# QuDAC_V4.net
KiCad netlist of a schematic drawn in EAGLE
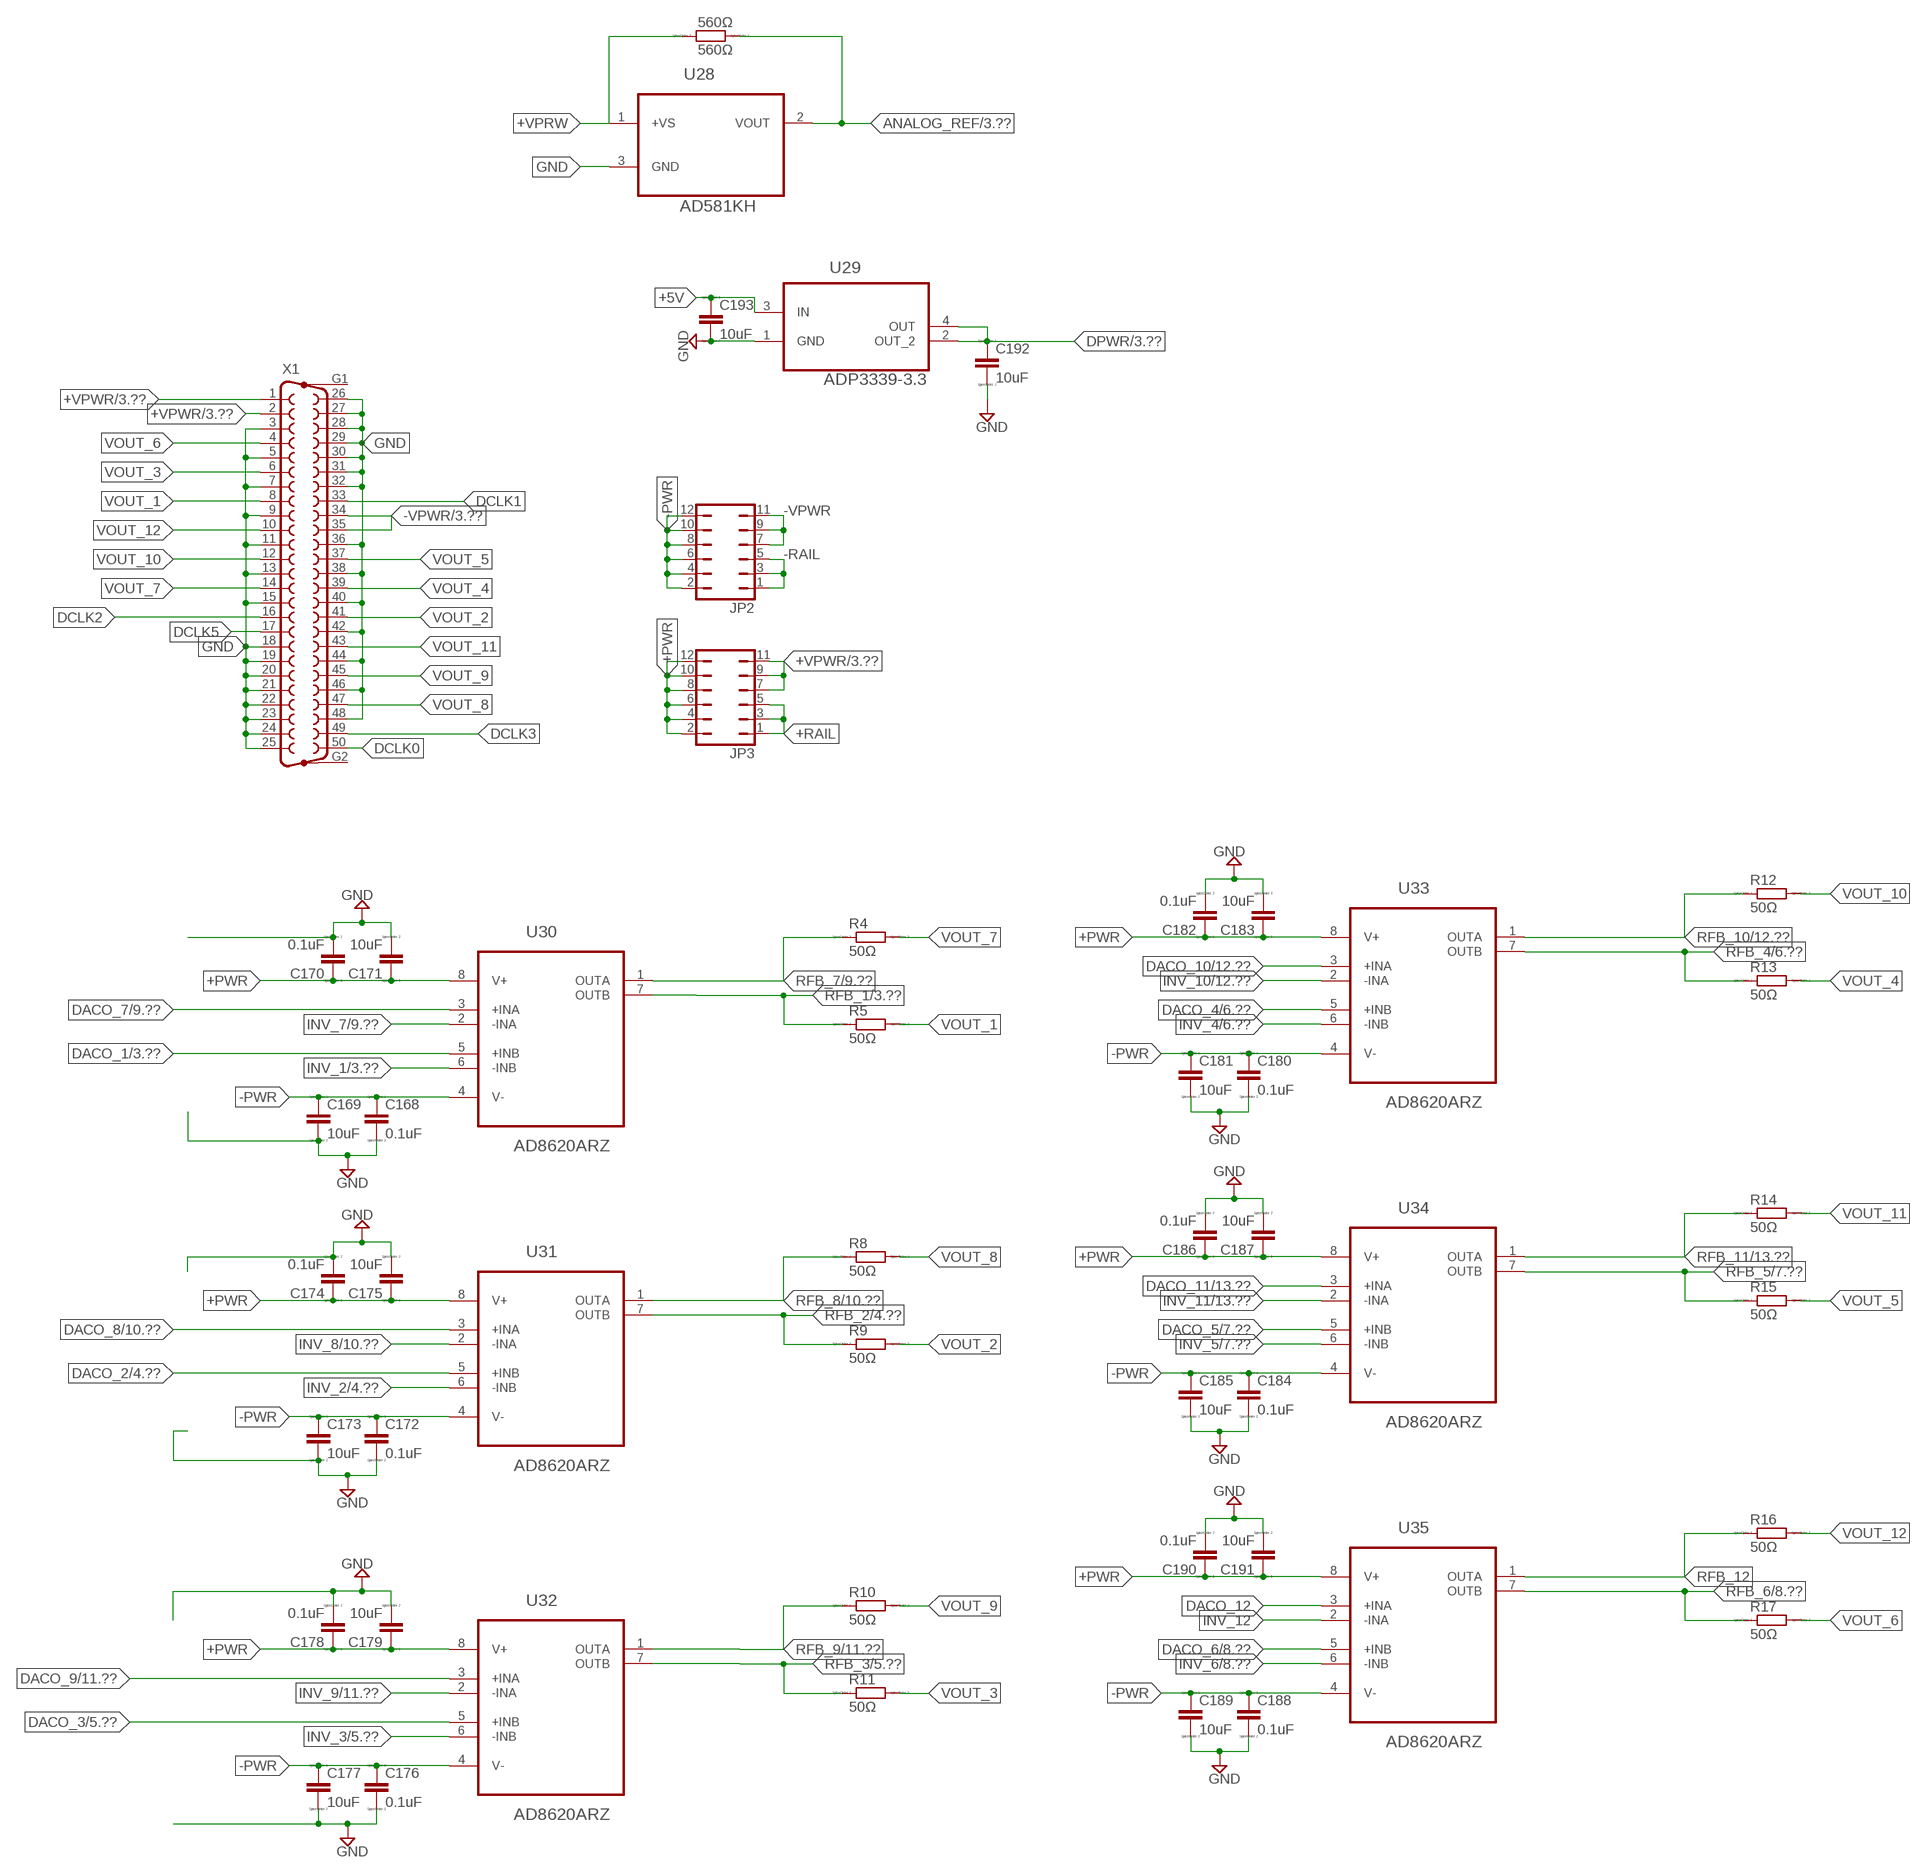
[diagram p0: schematic, sheet 1]
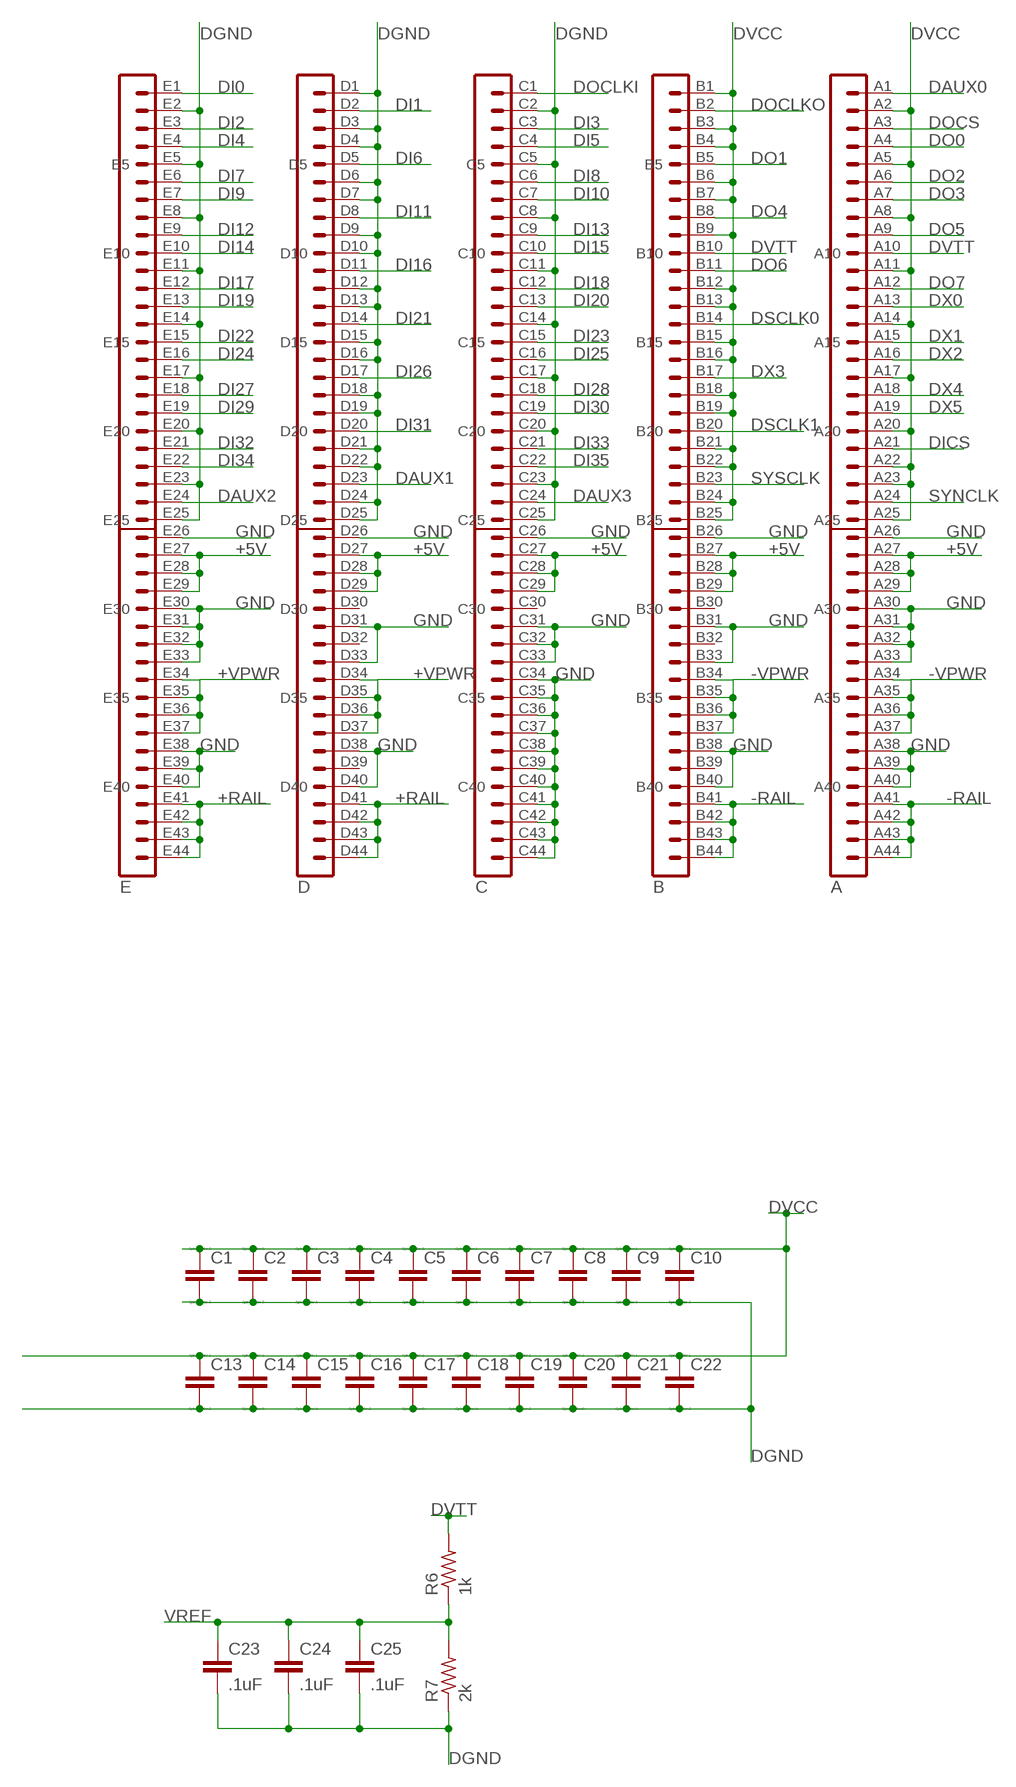
[diagram p1: schematic, sheet 2, part 1 of 2]
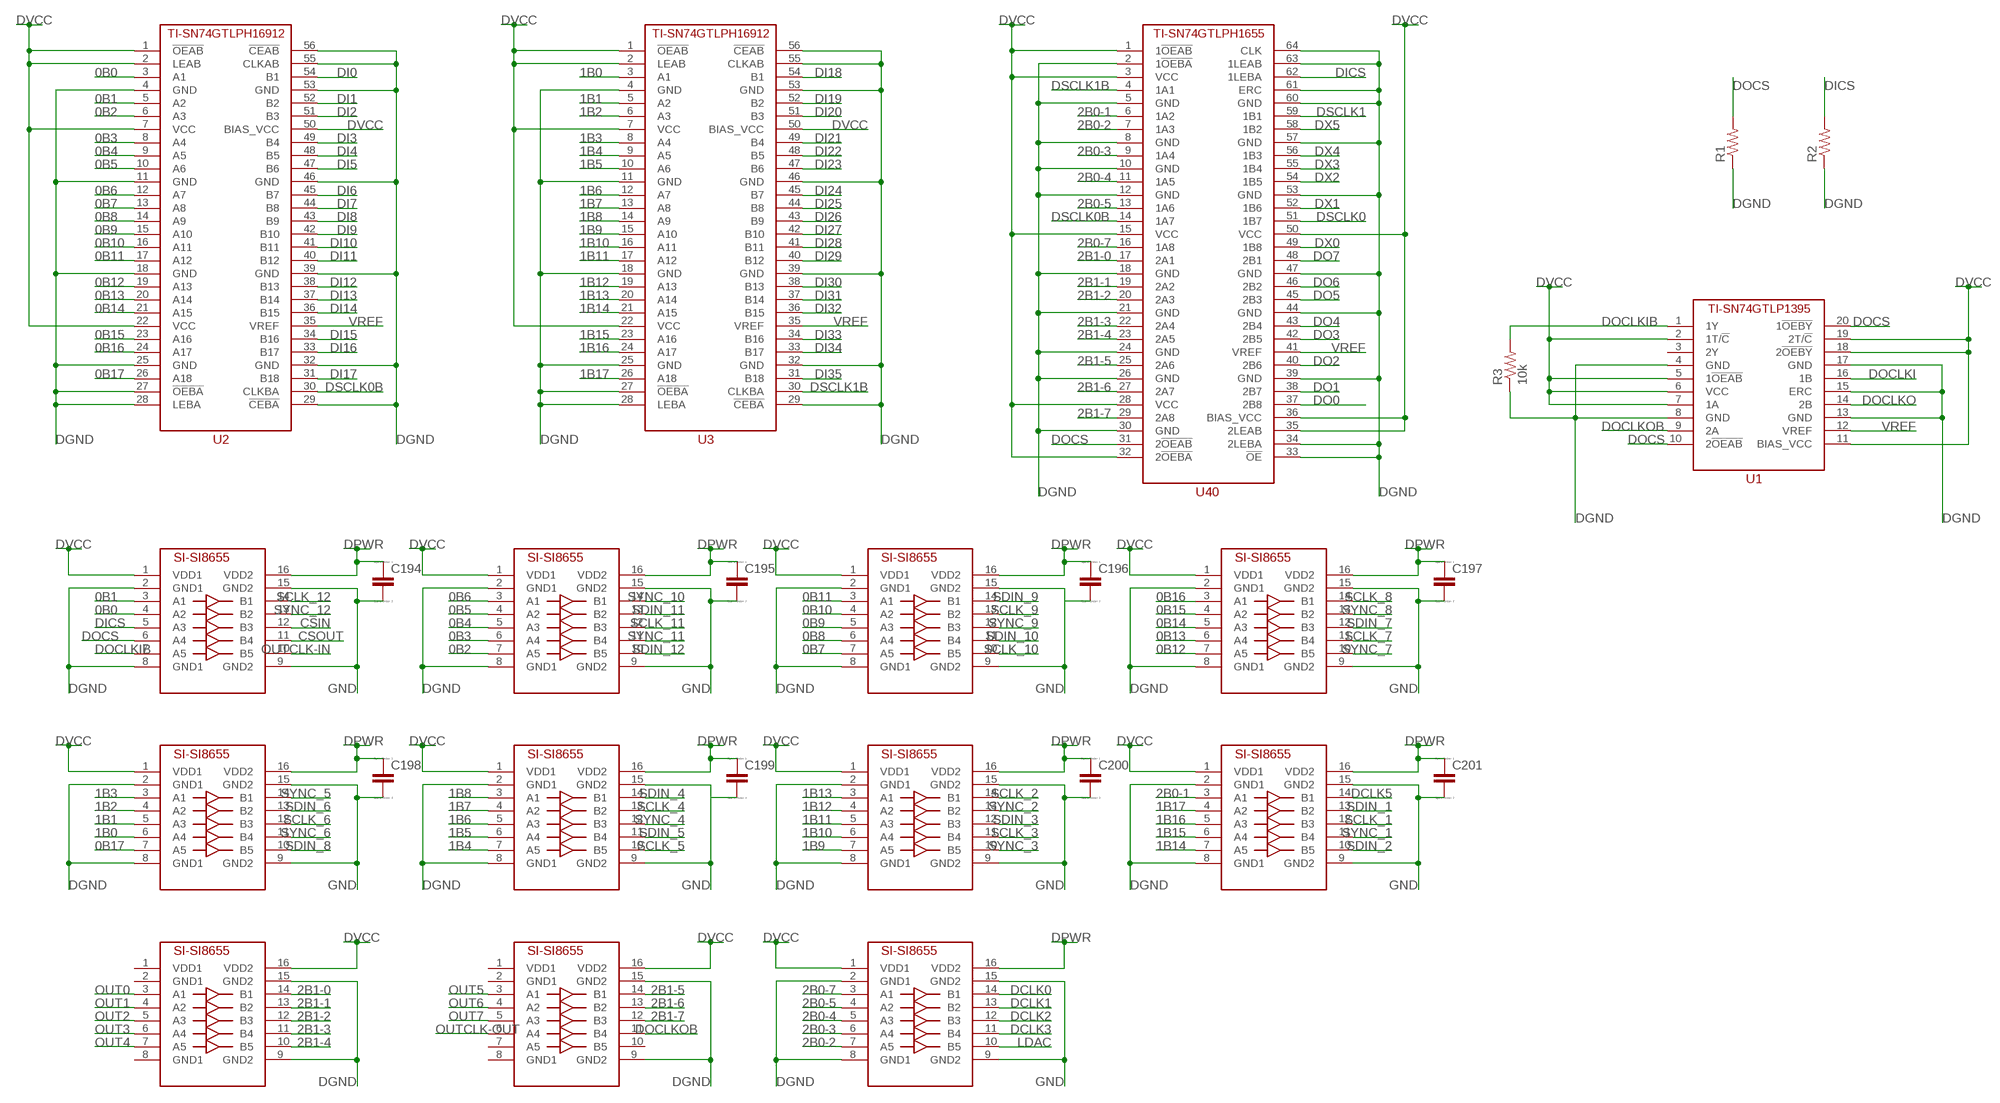
[diagram p2: schematic, sheet 2, part 2 of 2]
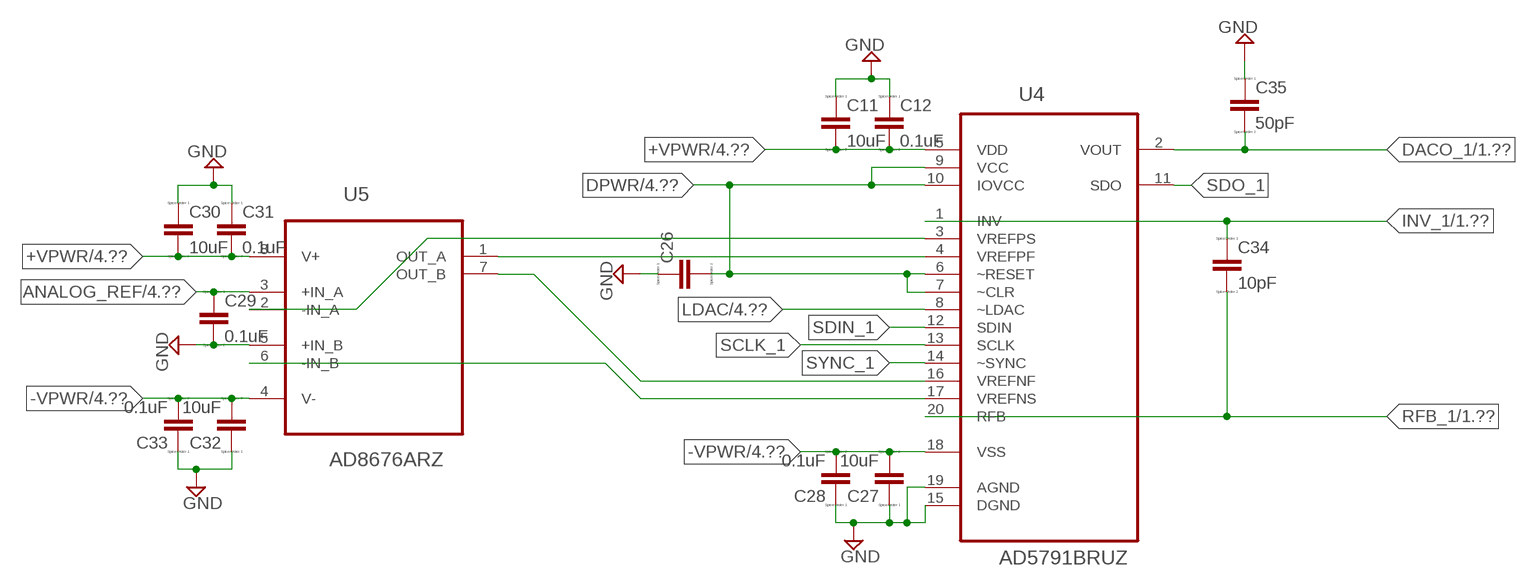
[diagram p3: schematic, sheet 3]
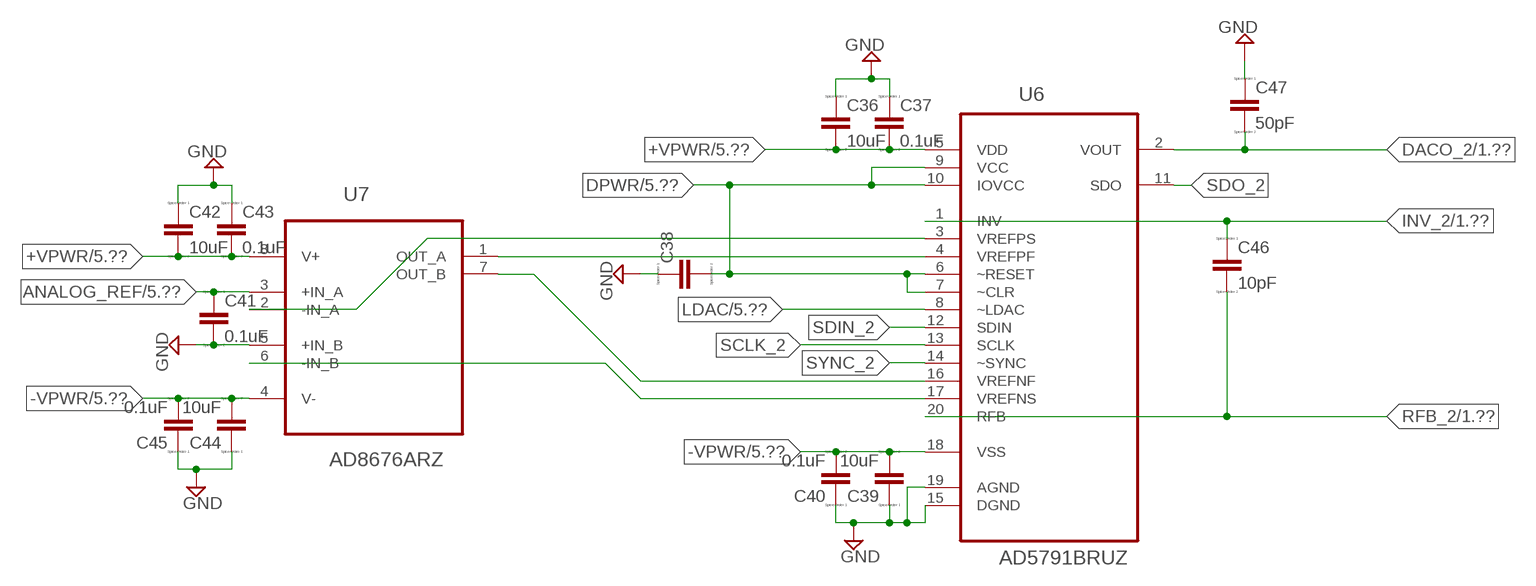
[diagram p4: schematic, sheet 4]
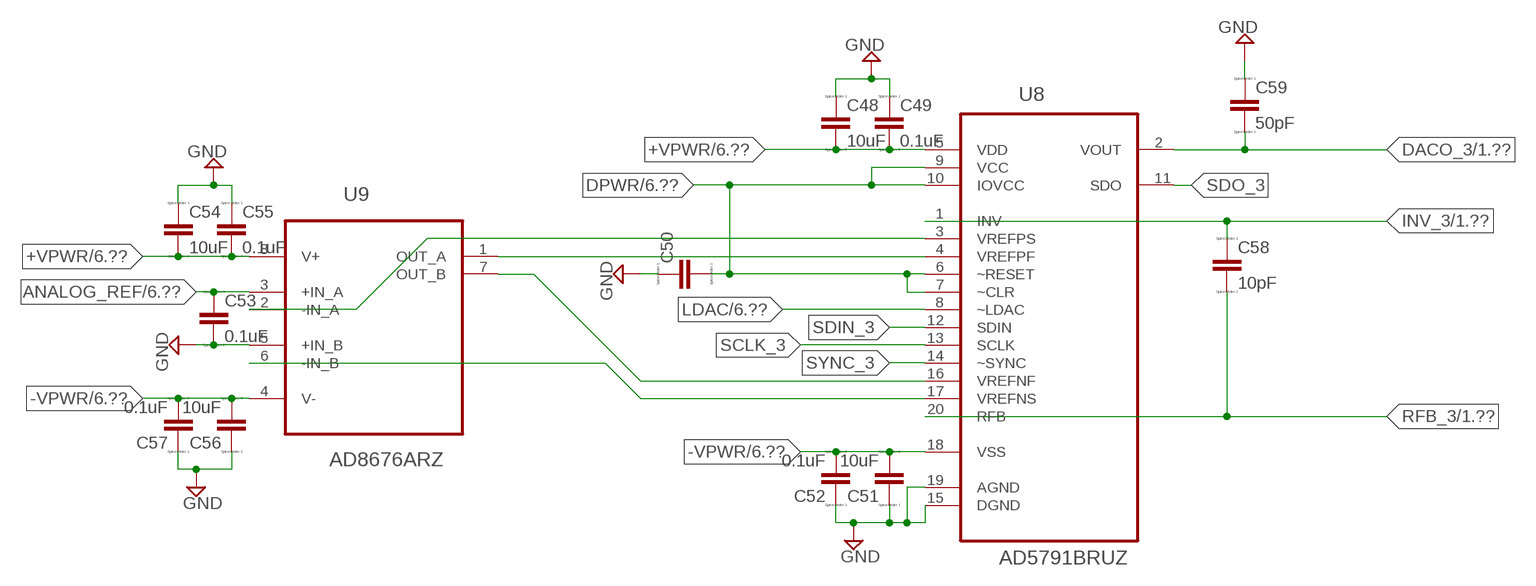
[diagram p5: schematic, sheet 5]
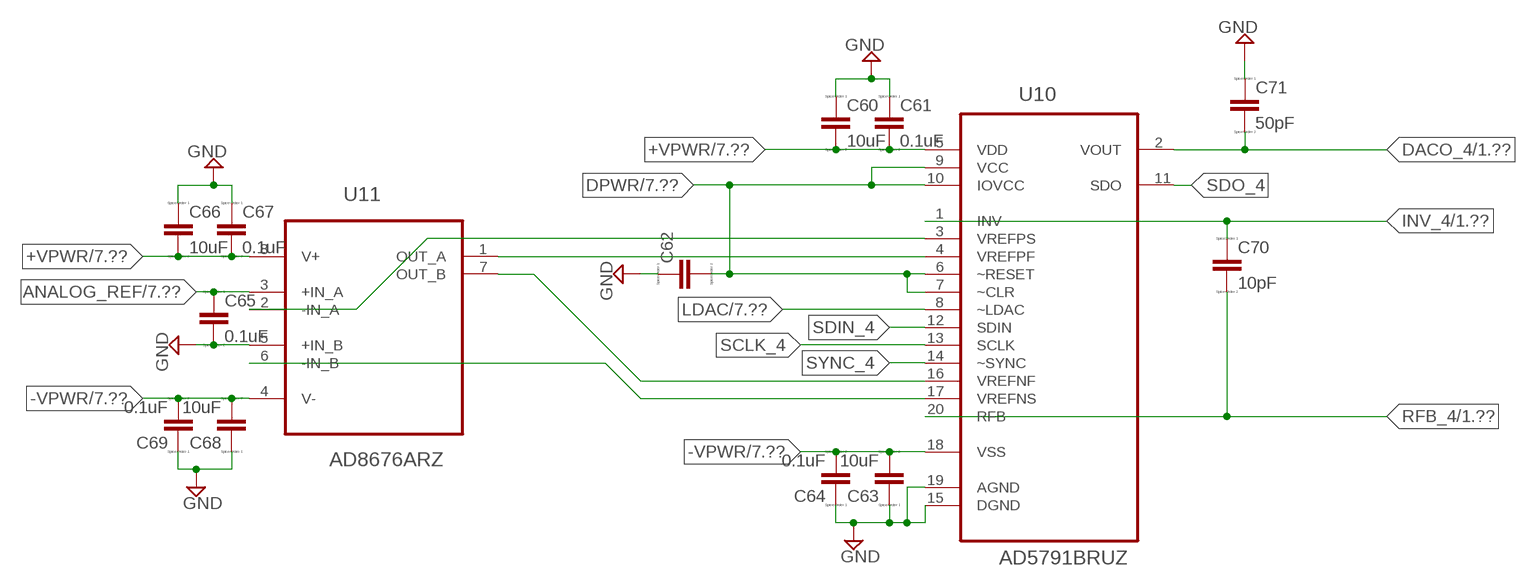
[diagram p6: schematic, sheet 6]
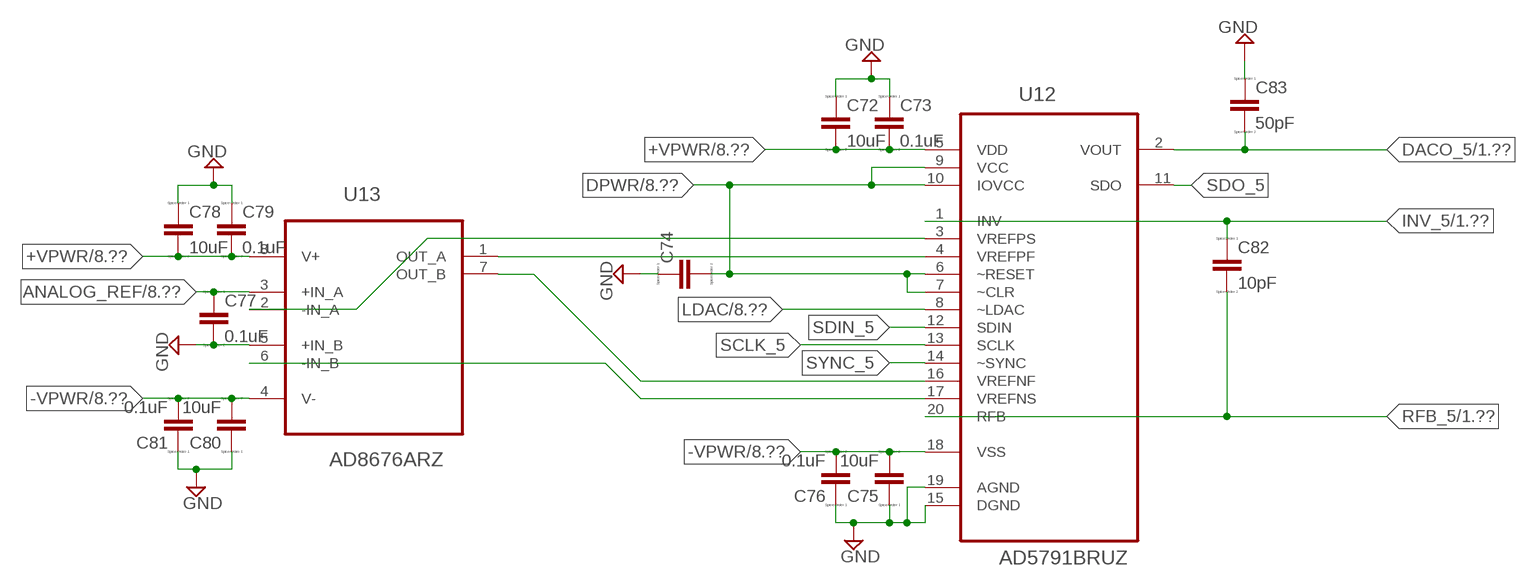
[diagram p7: schematic, sheet 7]
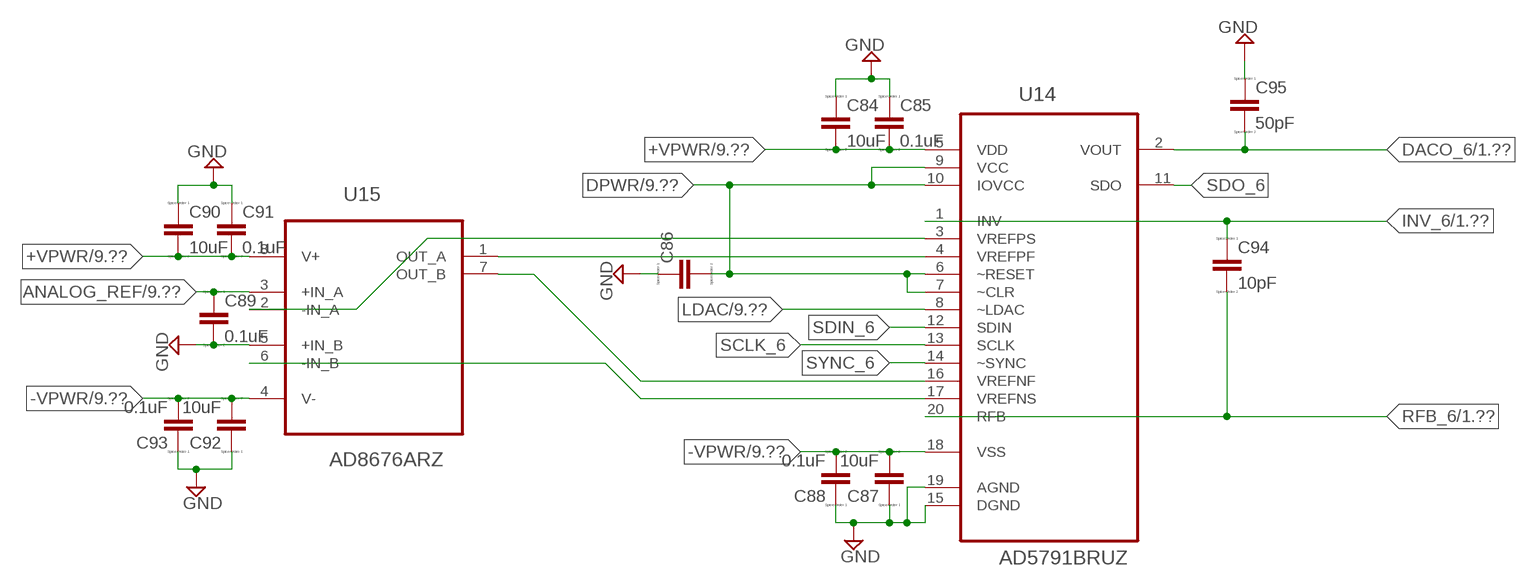
[diagram p8: schematic, sheet 8]
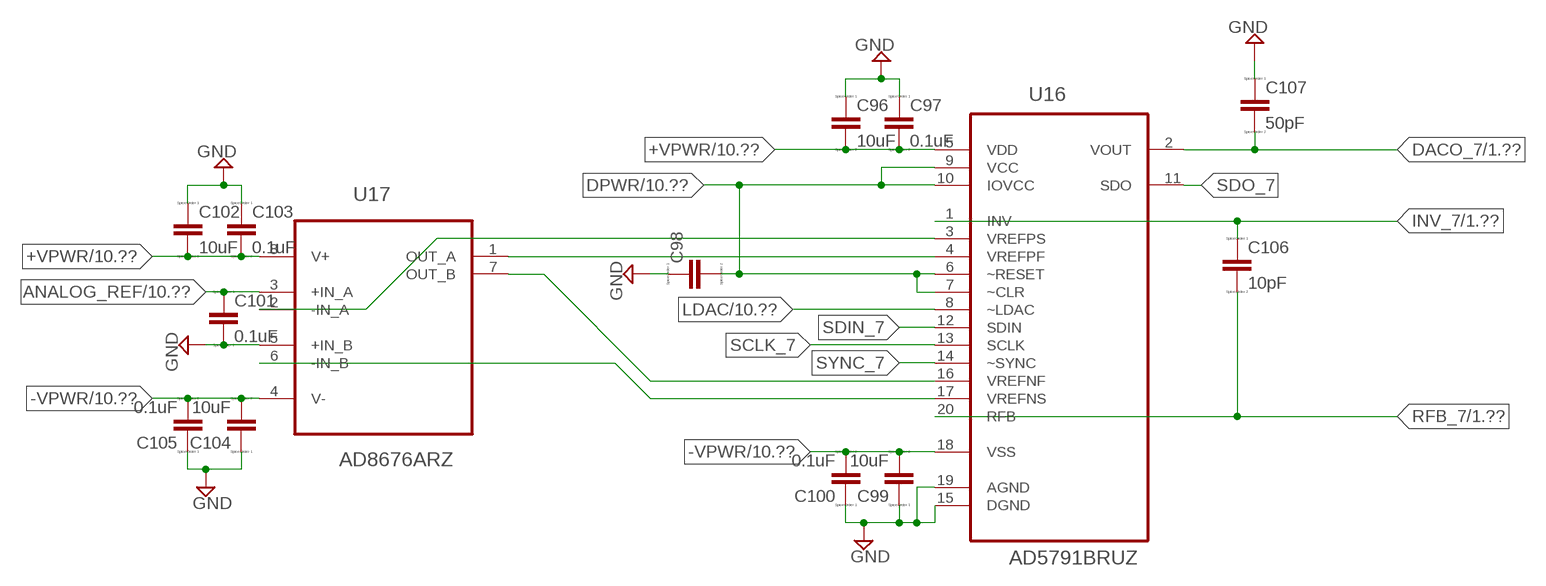
[diagram p9: schematic, sheet 9]
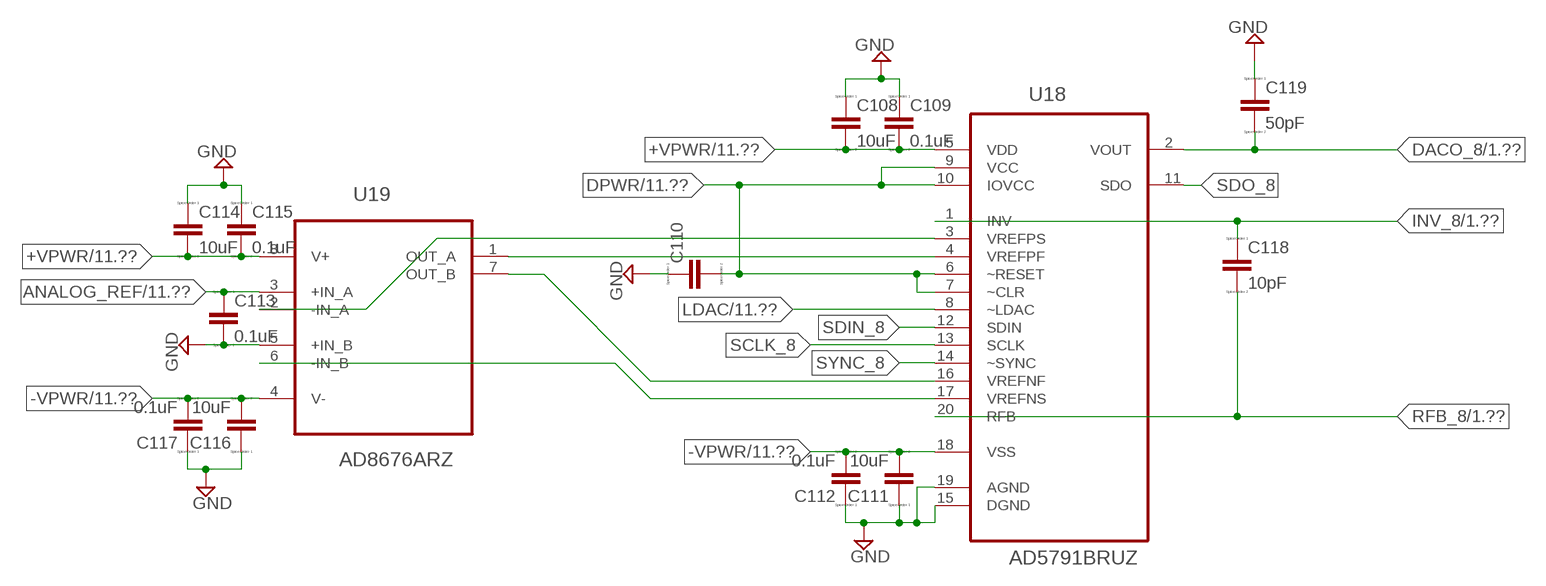
[diagram p10: schematic, sheet 10]
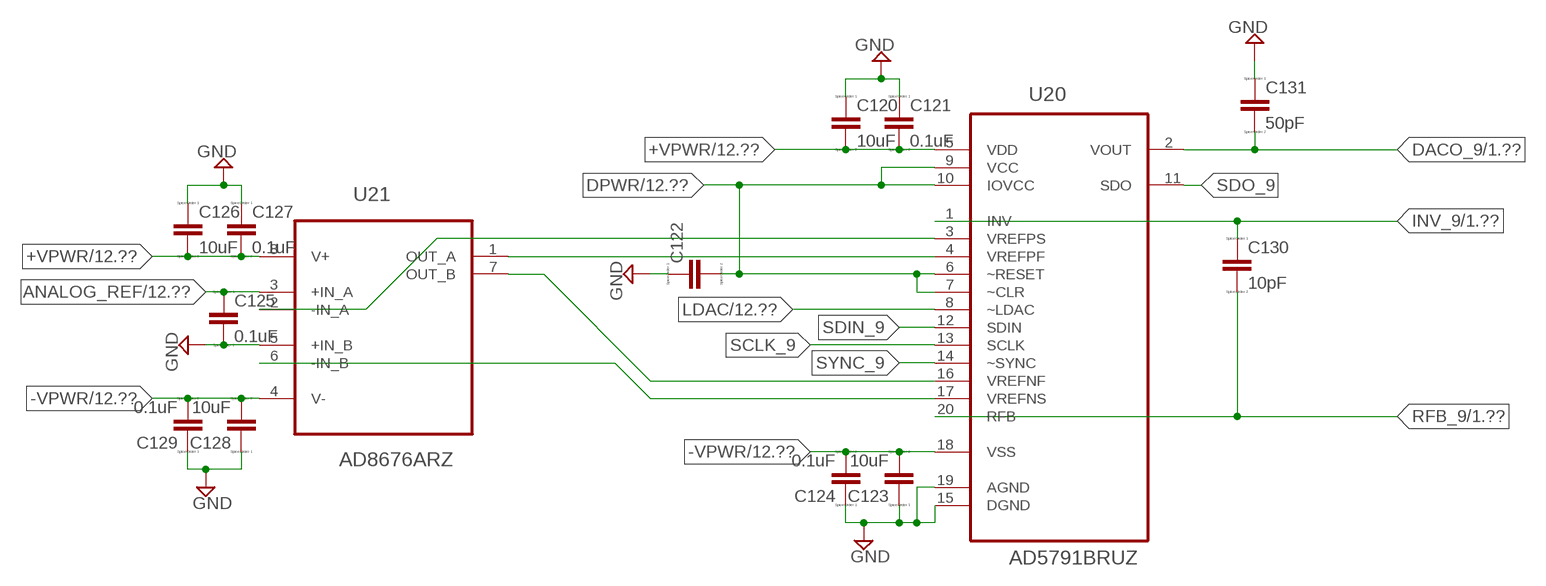
[diagram p11: schematic, sheet 11]
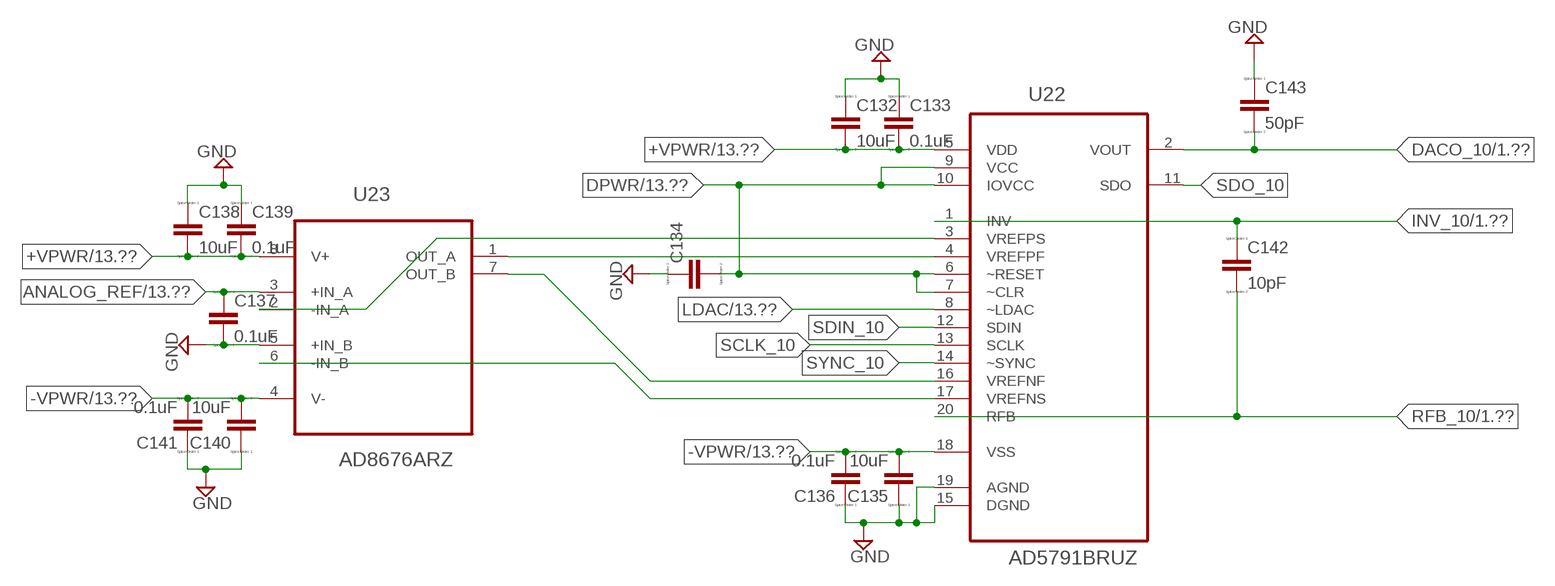
[diagram p12: schematic, sheet 12]
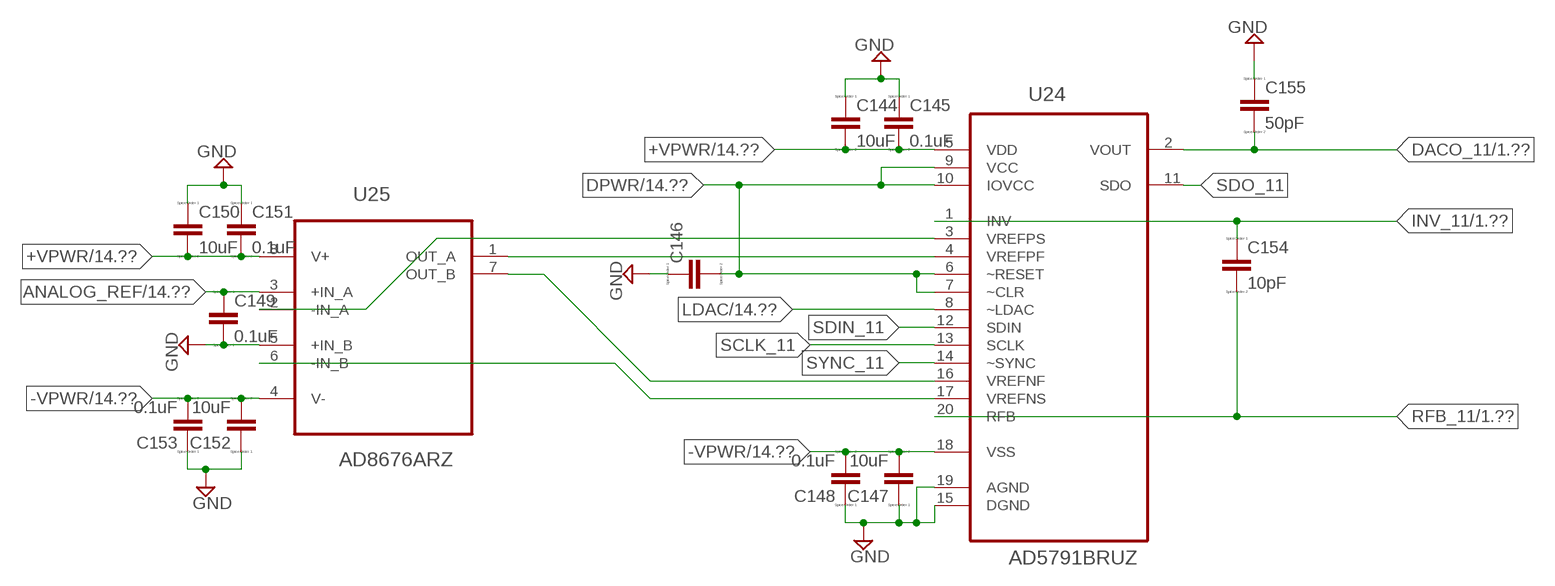
[diagram p13: schematic, sheet 13]
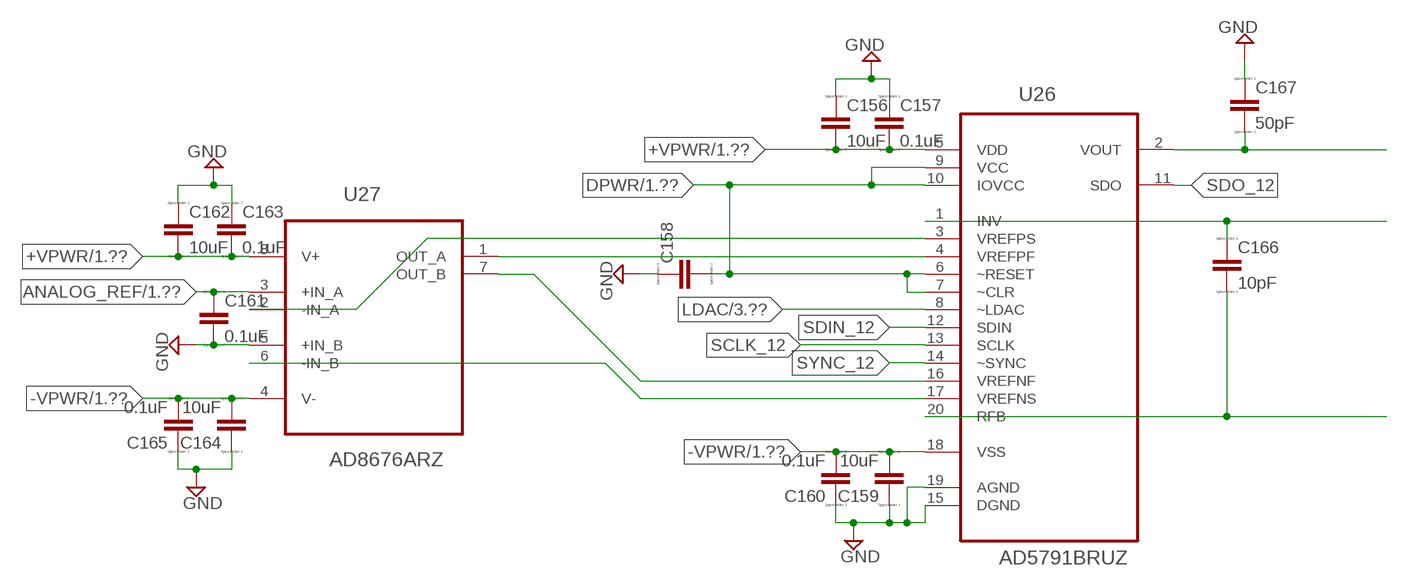
[diagram p14: schematic, sheet 14]

(export (version "E")
  (design (tool "Eeschema 10.0.6"))
  (components
    (comp (ref "C36")
      (value "10uF")
      (footprint "eagle-import:C0805")
      (libsource (lib "eagle-import") (part "C"))
    )
    (comp (ref "C37")
      (value "0.1uF")
      (footprint "eagle-import:C0603")
      (libsource (lib "eagle-import") (part "CC0603"))
    )
    (comp (ref "C38")
      (value "CC0603")
      (footprint "eagle-import:C0603")
      (libsource (lib "eagle-import") (part "CC0603"))
    )
    (comp (ref "C39")
      (value "10uF")
      (footprint "eagle-import:C0805")
      (libsource (lib "eagle-import") (part "C"))
    )
    (comp (ref "C40")
      (value "0.1uF")
      (footprint "eagle-import:C0603")
      (libsource (lib "eagle-import") (part "CC0603"))
    )
    (comp (ref "C41")
      (value "0.1uF")
      (footprint "eagle-import:C0603")
      (libsource (lib "eagle-import") (part "CC0603"))
    )
    (comp (ref "C42")
      (value "10uF")
      (footprint "eagle-import:C0805")
      (libsource (lib "eagle-import") (part "C"))
    )
    (comp (ref "C43")
      (value "0.1uF")
      (footprint "eagle-import:C0603")
      (libsource (lib "eagle-import") (part "CC0603"))
    )
    (comp (ref "C44")
      (value "10uF")
      (footprint "eagle-import:C0805")
      (libsource (lib "eagle-import") (part "C"))
    )
    (comp (ref "C45")
      (value "0.1uF")
      (footprint "eagle-import:C0603")
      (libsource (lib "eagle-import") (part "CC0603"))
    )
    (comp (ref "C46")
      (value "10pF")
      (footprint "eagle-import:C0603")
      (libsource (lib "eagle-import") (part "CC0603"))
    )
    (comp (ref "C47")
      (value "50pF")
      (footprint "eagle-import:C0603")
      (libsource (lib "eagle-import") (part "CC0603"))
    )
    (comp (ref "U6")
      (value "AD5791BRUZ")
      (footprint "eagle-import:SOP65P640X120-20N")
      (libsource (lib "eagle-import") (part "AD5791BRUZ"))
    )
    (comp (ref "U7")
      (value "AD8676ARZ")
      (footprint "eagle-import:SOIC127P600X175-8N")
      (libsource (lib "eagle-import") (part "AD8676ARZ"))
    )
    (comp (ref "C1")
      (value "CC0603")
      (footprint "eagle-import:C0603")
      (libsource (lib "eagle-import") (part "CC0603"))
    )
    (comp (ref "C2")
      (value "CC0603")
      (footprint "eagle-import:C0603")
      (libsource (lib "eagle-import") (part "CC0603"))
    )
    (comp (ref "C3")
      (value "CC0603")
      (footprint "eagle-import:C0603")
      (libsource (lib "eagle-import") (part "CC0603"))
    )
    (comp (ref "C4")
      (value "CC0603")
      (footprint "eagle-import:C0603")
      (libsource (lib "eagle-import") (part "CC0603"))
    )
    (comp (ref "C5")
      (value "CC0603")
      (footprint "eagle-import:C0603")
      (libsource (lib "eagle-import") (part "CC0603"))
    )
    (comp (ref "C6")
      (value "CC0603")
      (footprint "eagle-import:C0603")
      (libsource (lib "eagle-import") (part "CC0603"))
    )
    (comp (ref "C7")
      (value "CC0603")
      (footprint "eagle-import:C0603")
      (libsource (lib "eagle-import") (part "CC0603"))
    )
    (comp (ref "C8")
      (value "CC0603")
      (footprint "eagle-import:C0603")
      (libsource (lib "eagle-import") (part "CC0603"))
    )
    (comp (ref "C9")
      (value "CC0603")
      (footprint "eagle-import:C0603")
      (libsource (lib "eagle-import") (part "CC0603"))
    )
    (comp (ref "C10")
      (value "CC0603")
      (footprint "eagle-import:C0603")
      (libsource (lib "eagle-import") (part "CC0603"))
    )
    (comp (ref "C13")
      (value "CC0603")
      (footprint "eagle-import:C0603")
      (libsource (lib "eagle-import") (part "CC0603"))
    )
    (comp (ref "C14")
      (value "CC0603")
      (footprint "eagle-import:C0603")
      (libsource (lib "eagle-import") (part "CC0603"))
    )
    (comp (ref "C15")
      (value "CC0603")
      (footprint "eagle-import:C0603")
      (libsource (lib "eagle-import") (part "CC0603"))
    )
    (comp (ref "C16")
      (value "CC0603")
      (footprint "eagle-import:C0603")
      (libsource (lib "eagle-import") (part "CC0603"))
    )
    (comp (ref "C17")
      (value "CC0603")
      (footprint "eagle-import:C0603")
      (libsource (lib "eagle-import") (part "CC0603"))
    )
    (comp (ref "C18")
      (value "CC0603")
      (footprint "eagle-import:C0603")
      (libsource (lib "eagle-import") (part "CC0603"))
    )
    (comp (ref "C19")
      (value "CC0603")
      (footprint "eagle-import:C0603")
      (libsource (lib "eagle-import") (part "CC0603"))
    )
    (comp (ref "C20")
      (value "CC0603")
      (footprint "eagle-import:C0603")
      (libsource (lib "eagle-import") (part "CC0603"))
    )
    (comp (ref "C21")
      (value "CC0603")
      (footprint "eagle-import:C0603")
      (libsource (lib "eagle-import") (part "CC0603"))
    )
    (comp (ref "C22")
      (value "CC0603")
      (footprint "eagle-import:C0603")
      (libsource (lib "eagle-import") (part "CC0603"))
    )
    (comp (ref "C23")
      (value ".1uF")
      (footprint "eagle-import:C0603")
      (libsource (lib "eagle-import") (part "C-EUC0603"))
    )
    (comp (ref "C24")
      (value ".1uF")
      (footprint "eagle-import:C0603")
      (libsource (lib "eagle-import") (part "C-EUC0603"))
    )
    (comp (ref "C25")
      (value ".1uF")
      (footprint "eagle-import:C0603")
      (libsource (lib "eagle-import") (part "C-EUC0603"))
    )
    (comp (ref "C194")
      (value "CC0603")
      (footprint "eagle-import:C0603")
      (libsource (lib "eagle-import") (part "CC0603"))
    )
    (comp (ref "C195")
      (value "CC0603")
      (footprint "eagle-import:C0603")
      (libsource (lib "eagle-import") (part "CC0603"))
    )
    (comp (ref "C196")
      (value "CC0603")
      (footprint "eagle-import:C0603")
      (libsource (lib "eagle-import") (part "CC0603"))
    )
    (comp (ref "C197")
      (value "CC0603")
      (footprint "eagle-import:C0603")
      (libsource (lib "eagle-import") (part "CC0603"))
    )
    (comp (ref "C198")
      (value "CC0603")
      (footprint "eagle-import:C0603")
      (libsource (lib "eagle-import") (part "CC0603"))
    )
    (comp (ref "C199")
      (value "CC0603")
      (footprint "eagle-import:C0603")
      (libsource (lib "eagle-import") (part "CC0603"))
    )
    (comp (ref "C200")
      (value "CC0603")
      (footprint "eagle-import:C0603")
      (libsource (lib "eagle-import") (part "CC0603"))
    )
    (comp (ref "C201")
      (value "CC0603")
      (footprint "eagle-import:C0603")
      (libsource (lib "eagle-import") (part "CC0603"))
    )
    (comp (ref "ISO1")
      (value "SI-SI8655")
      (footprint "eagle-import:QSOP-16")
      (libsource (lib "eagle-import") (part "SI-SI8655"))
    )
    (comp (ref "ISO2")
      (value "SI-SI8655")
      (footprint "eagle-import:QSOP-16")
      (libsource (lib "eagle-import") (part "SI-SI8655"))
    )
    (comp (ref "ISO3")
      (value "SI-SI8655")
      (footprint "eagle-import:QSOP-16")
      (libsource (lib "eagle-import") (part "SI-SI8655"))
    )
    (comp (ref "ISO4")
      (value "SI-SI8655")
      (footprint "eagle-import:QSOP-16")
      (libsource (lib "eagle-import") (part "SI-SI8655"))
    )
    (comp (ref "ISO5")
      (value "SI-SI8655")
      (footprint "eagle-import:QSOP-16")
      (libsource (lib "eagle-import") (part "SI-SI8655"))
    )
    (comp (ref "ISO6")
      (value "SI-SI8655")
      (footprint "eagle-import:QSOP-16")
      (libsource (lib "eagle-import") (part "SI-SI8655"))
    )
    (comp (ref "ISO7")
      (value "SI-SI8655")
      (footprint "eagle-import:QSOP-16")
      (libsource (lib "eagle-import") (part "SI-SI8655"))
    )
    (comp (ref "ISO8")
      (value "SI-SI8655")
      (footprint "eagle-import:QSOP-16")
      (libsource (lib "eagle-import") (part "SI-SI8655"))
    )
    (comp (ref "ISO9")
      (value "SI-SI8655")
      (footprint "eagle-import:QSOP-16")
      (libsource (lib "eagle-import") (part "SI-SI8655"))
    )
    (comp (ref "ISO10")
      (value "SI-SI8655")
      (footprint "eagle-import:QSOP-16")
      (libsource (lib "eagle-import") (part "SI-SI8655"))
    )
    (comp (ref "ISO11")
      (value "SI-SI8655")
      (footprint "eagle-import:QSOP-16")
      (libsource (lib "eagle-import") (part "SI-SI8655"))
    )
    (comp (ref "J1")
      (value "EUROCARD-CPCI-220EUROCARD-B19+AB25-NOFRONTDIM")
      (footprint "eagle-import:EUROCARD-CPCI-B19+1B25-NOFRONTDIM")
      (libsource (lib "eagle-import") (part "EUROCARD-CPCI-220EUROCARD-B19+AB25-NOFRONTDIM"))
    )
    (comp (ref "R1")
      (value "R-US_R0603")
      (footprint "eagle-import:R0603")
      (libsource (lib "eagle-import") (part "R-US_R0603"))
    )
    (comp (ref "R2")
      (value "R-US_R0603")
      (footprint "eagle-import:R0603")
      (libsource (lib "eagle-import") (part "R-US_R0603"))
    )
    (comp (ref "R3")
      (value "10k")
      (footprint "eagle-import:R0603")
      (libsource (lib "eagle-import") (part "R-US_R0603"))
    )
    (comp (ref "R6")
      (value "1k")
      (footprint "eagle-import:R0805")
      (libsource (lib "eagle-import") (part "R-US_R0805"))
    )
    (comp (ref "R7")
      (value "2k")
      (footprint "eagle-import:R0805")
      (libsource (lib "eagle-import") (part "R-US_R0805"))
    )
    (comp (ref "U1")
      (value "TI-SN74GTLP1395")
      (footprint "eagle-import:TSSOP-20")
      (libsource (lib "eagle-import") (part "TI-SN74GTLP1395"))
    )
    (comp (ref "U2")
      (value "TI-SN74GTLPH16912")
      (footprint "eagle-import:TSSOP-56")
      (libsource (lib "eagle-import") (part "TI-SN74GTLPH16912"))
    )
    (comp (ref "U3")
      (value "TI-SN74GTLPH16912")
      (footprint "eagle-import:TSSOP-56")
      (libsource (lib "eagle-import") (part "TI-SN74GTLPH16912"))
    )
    (comp (ref "U40")
      (value "TI-SN74GTLPH1655")
      (footprint "eagle-import:TSSOP-64")
      (libsource (lib "eagle-import") (part "TI-SN74GTLPH1655"))
    )
    (comp (ref "C132")
      (value "10uF")
      (footprint "eagle-import:C0805")
      (libsource (lib "eagle-import") (part "C"))
    )
    (comp (ref "C133")
      (value "0.1uF")
      (footprint "eagle-import:C0603")
      (libsource (lib "eagle-import") (part "CC0603"))
    )
    (comp (ref "C134")
      (value "CC0603")
      (footprint "eagle-import:C0603")
      (libsource (lib "eagle-import") (part "CC0603"))
    )
    (comp (ref "C135")
      (value "10uF")
      (footprint "eagle-import:C0805")
      (libsource (lib "eagle-import") (part "C"))
    )
    (comp (ref "C136")
      (value "0.1uF")
      (footprint "eagle-import:C0603")
      (libsource (lib "eagle-import") (part "CC0603"))
    )
    (comp (ref "C137")
      (value "0.1uF")
      (footprint "eagle-import:C0603")
      (libsource (lib "eagle-import") (part "CC0603"))
    )
    (comp (ref "C138")
      (value "10uF")
      (footprint "eagle-import:C0805")
      (libsource (lib "eagle-import") (part "C"))
    )
    (comp (ref "C139")
      (value "0.1uF")
      (footprint "eagle-import:C0603")
      (libsource (lib "eagle-import") (part "CC0603"))
    )
    (comp (ref "C140")
      (value "10uF")
      (footprint "eagle-import:C0805")
      (libsource (lib "eagle-import") (part "C"))
    )
    (comp (ref "C141")
      (value "0.1uF")
      (footprint "eagle-import:C0603")
      (libsource (lib "eagle-import") (part "CC0603"))
    )
    (comp (ref "C142")
      (value "10pF")
      (footprint "eagle-import:C0603")
      (libsource (lib "eagle-import") (part "CC0603"))
    )
    (comp (ref "C143")
      (value "50pF")
      (footprint "eagle-import:C0603")
      (libsource (lib "eagle-import") (part "CC0603"))
    )
    (comp (ref "U22")
      (value "AD5791BRUZ")
      (footprint "eagle-import:SOP65P640X120-20N")
      (libsource (lib "eagle-import") (part "AD5791BRUZ"))
    )
    (comp (ref "U23")
      (value "AD8676ARZ")
      (footprint "eagle-import:SOIC127P600X175-8N")
      (libsource (lib "eagle-import") (part "AD8676ARZ"))
    )
    (comp (ref "C96")
      (value "10uF")
      (footprint "eagle-import:C0805")
      (libsource (lib "eagle-import") (part "C"))
    )
    (comp (ref "C97")
      (value "0.1uF")
      (footprint "eagle-import:C0603")
      (libsource (lib "eagle-import") (part "CC0603"))
    )
    (comp (ref "C98")
      (value "CC0603")
      (footprint "eagle-import:C0603")
      (libsource (lib "eagle-import") (part "CC0603"))
    )
    (comp (ref "C99")
      (value "10uF")
      (footprint "eagle-import:C0805")
      (libsource (lib "eagle-import") (part "C"))
    )
    (comp (ref "C100")
      (value "0.1uF")
      (footprint "eagle-import:C0603")
      (libsource (lib "eagle-import") (part "CC0603"))
    )
    (comp (ref "C101")
      (value "0.1uF")
      (footprint "eagle-import:C0603")
      (libsource (lib "eagle-import") (part "CC0603"))
    )
    (comp (ref "C102")
      (value "10uF")
      (footprint "eagle-import:C0805")
      (libsource (lib "eagle-import") (part "C"))
    )
    (comp (ref "C103")
      (value "0.1uF")
      (footprint "eagle-import:C0603")
      (libsource (lib "eagle-import") (part "CC0603"))
    )
    (comp (ref "C104")
      (value "10uF")
      (footprint "eagle-import:C0805")
      (libsource (lib "eagle-import") (part "C"))
    )
    (comp (ref "C105")
      (value "0.1uF")
      (footprint "eagle-import:C0603")
      (libsource (lib "eagle-import") (part "CC0603"))
    )
    (comp (ref "C106")
      (value "10pF")
      (footprint "eagle-import:C0603")
      (libsource (lib "eagle-import") (part "CC0603"))
    )
    (comp (ref "C107")
      (value "50pF")
      (footprint "eagle-import:C0603")
      (libsource (lib "eagle-import") (part "CC0603"))
    )
    (comp (ref "U16")
      (value "AD5791BRUZ")
      (footprint "eagle-import:SOP65P640X120-20N")
      (libsource (lib "eagle-import") (part "AD5791BRUZ"))
    )
    (comp (ref "U17")
      (value "AD8676ARZ")
      (footprint "eagle-import:SOIC127P600X175-8N")
      (libsource (lib "eagle-import") (part "AD8676ARZ"))
    )
    (comp (ref "C156")
      (value "10uF")
      (footprint "eagle-import:C0805")
      (libsource (lib "eagle-import") (part "C"))
    )
    (comp (ref "C157")
      (value "0.1uF")
      (footprint "eagle-import:C0603")
      (libsource (lib "eagle-import") (part "CC0603"))
    )
    (comp (ref "C158")
      (value "CC0603")
      (footprint "eagle-import:C0603")
      (libsource (lib "eagle-import") (part "CC0603"))
    )
    (comp (ref "C159")
      (value "10uF")
      (footprint "eagle-import:C0805")
      (libsource (lib "eagle-import") (part "C"))
    )
    (comp (ref "C160")
      (value "0.1uF")
      (footprint "eagle-import:C0603")
      (libsource (lib "eagle-import") (part "CC0603"))
    )
    (comp (ref "C161")
      (value "0.1uF")
      (footprint "eagle-import:C0603")
      (libsource (lib "eagle-import") (part "CC0603"))
    )
    (comp (ref "C162")
      (value "10uF")
      (footprint "eagle-import:C0805")
      (libsource (lib "eagle-import") (part "C"))
    )
    (comp (ref "C163")
      (value "0.1uF")
      (footprint "eagle-import:C0603")
      (libsource (lib "eagle-import") (part "CC0603"))
    )
    (comp (ref "C164")
      (value "10uF")
      (footprint "eagle-import:C0805")
      (libsource (lib "eagle-import") (part "C"))
    )
    (comp (ref "C165")
      (value "0.1uF")
      (footprint "eagle-import:C0603")
      (libsource (lib "eagle-import") (part "CC0603"))
    )
    (comp (ref "C166")
      (value "10pF")
      (footprint "eagle-import:C0603")
      (libsource (lib "eagle-import") (part "CC0603"))
    )
    (comp (ref "C167")
      (value "50pF")
      (footprint "eagle-import:C0603")
      (libsource (lib "eagle-import") (part "CC0603"))
    )
    (comp (ref "U26")
      (value "AD5791BRUZ")
      (footprint "eagle-import:SOP65P640X120-20N")
      (libsource (lib "eagle-import") (part "AD5791BRUZ"))
    )
    (comp (ref "U27")
      (value "AD8676ARZ")
      (footprint "eagle-import:SOIC127P600X175-8N")
      (libsource (lib "eagle-import") (part "AD8676ARZ"))
    )
    (comp (ref "C108")
      (value "10uF")
      (footprint "eagle-import:C0805")
      (libsource (lib "eagle-import") (part "C"))
    )
    (comp (ref "C109")
      (value "0.1uF")
      (footprint "eagle-import:C0603")
      (libsource (lib "eagle-import") (part "CC0603"))
    )
    (comp (ref "C110")
      (value "CC0603")
      (footprint "eagle-import:C0603")
      (libsource (lib "eagle-import") (part "CC0603"))
    )
    (comp (ref "C111")
      (value "10uF")
      (footprint "eagle-import:C0805")
      (libsource (lib "eagle-import") (part "C"))
    )
    (comp (ref "C112")
      (value "0.1uF")
      (footprint "eagle-import:C0603")
      (libsource (lib "eagle-import") (part "CC0603"))
    )
    (comp (ref "C113")
      (value "0.1uF")
      (footprint "eagle-import:C0603")
      (libsource (lib "eagle-import") (part "CC0603"))
    )
    (comp (ref "C114")
      (value "10uF")
      (footprint "eagle-import:C0805")
      (libsource (lib "eagle-import") (part "C"))
    )
    (comp (ref "C115")
      (value "0.1uF")
      (footprint "eagle-import:C0603")
      (libsource (lib "eagle-import") (part "CC0603"))
    )
    (comp (ref "C116")
      (value "10uF")
      (footprint "eagle-import:C0805")
      (libsource (lib "eagle-import") (part "C"))
    )
    (comp (ref "C117")
      (value "0.1uF")
      (footprint "eagle-import:C0603")
      (libsource (lib "eagle-import") (part "CC0603"))
    )
    (comp (ref "C118")
      (value "10pF")
      (footprint "eagle-import:C0603")
      (libsource (lib "eagle-import") (part "CC0603"))
    )
    (comp (ref "C119")
      (value "50pF")
      (footprint "eagle-import:C0603")
      (libsource (lib "eagle-import") (part "CC0603"))
    )
    (comp (ref "U18")
      (value "AD5791BRUZ")
      (footprint "eagle-import:SOP65P640X120-20N")
      (libsource (lib "eagle-import") (part "AD5791BRUZ"))
    )
    (comp (ref "U19")
      (value "AD8676ARZ")
      (footprint "eagle-import:SOIC127P600X175-8N")
      (libsource (lib "eagle-import") (part "AD8676ARZ"))
    )
    (comp (ref "C120")
      (value "10uF")
      (footprint "eagle-import:C0805")
      (libsource (lib "eagle-import") (part "C"))
    )
    (comp (ref "C121")
      (value "0.1uF")
      (footprint "eagle-import:C0603")
      (libsource (lib "eagle-import") (part "CC0603"))
    )
    (comp (ref "C122")
      (value "CC0603")
      (footprint "eagle-import:C0603")
      (libsource (lib "eagle-import") (part "CC0603"))
    )
    (comp (ref "C123")
      (value "10uF")
      (footprint "eagle-import:C0805")
      (libsource (lib "eagle-import") (part "C"))
    )
    (comp (ref "C124")
      (value "0.1uF")
      (footprint "eagle-import:C0603")
      (libsource (lib "eagle-import") (part "CC0603"))
    )
    (comp (ref "C125")
      (value "0.1uF")
      (footprint "eagle-import:C0603")
      (libsource (lib "eagle-import") (part "CC0603"))
    )
    (comp (ref "C126")
      (value "10uF")
      (footprint "eagle-import:C0805")
      (libsource (lib "eagle-import") (part "C"))
    )
    (comp (ref "C127")
      (value "0.1uF")
      (footprint "eagle-import:C0603")
      (libsource (lib "eagle-import") (part "CC0603"))
    )
    (comp (ref "C128")
      (value "10uF")
      (footprint "eagle-import:C0805")
      (libsource (lib "eagle-import") (part "C"))
    )
    (comp (ref "C129")
      (value "0.1uF")
      (footprint "eagle-import:C0603")
      (libsource (lib "eagle-import") (part "CC0603"))
    )
    (comp (ref "C130")
      (value "10pF")
      (footprint "eagle-import:C0603")
      (libsource (lib "eagle-import") (part "CC0603"))
    )
    (comp (ref "C131")
      (value "50pF")
      (footprint "eagle-import:C0603")
      (libsource (lib "eagle-import") (part "CC0603"))
    )
    (comp (ref "U20")
      (value "AD5791BRUZ")
      (footprint "eagle-import:SOP65P640X120-20N")
      (libsource (lib "eagle-import") (part "AD5791BRUZ"))
    )
    (comp (ref "U21")
      (value "AD8676ARZ")
      (footprint "eagle-import:SOIC127P600X175-8N")
      (libsource (lib "eagle-import") (part "AD8676ARZ"))
    )
    (comp (ref "C11")
      (value "10uF")
      (footprint "eagle-import:C0805")
      (libsource (lib "eagle-import") (part "C"))
    )
    (comp (ref "C12")
      (value "0.1uF")
      (footprint "eagle-import:C0603")
      (libsource (lib "eagle-import") (part "CC0603"))
    )
    (comp (ref "C26")
      (value "CC0603")
      (footprint "eagle-import:C0603")
      (libsource (lib "eagle-import") (part "CC0603"))
    )
    (comp (ref "C27")
      (value "10uF")
      (footprint "eagle-import:C0805")
      (libsource (lib "eagle-import") (part "C"))
    )
    (comp (ref "C28")
      (value "0.1uF")
      (footprint "eagle-import:C0603")
      (libsource (lib "eagle-import") (part "CC0603"))
    )
    (comp (ref "C29")
      (value "0.1uF")
      (footprint "eagle-import:C0603")
      (libsource (lib "eagle-import") (part "CC0603"))
    )
    (comp (ref "C30")
      (value "10uF")
      (footprint "eagle-import:C0805")
      (libsource (lib "eagle-import") (part "C"))
    )
    (comp (ref "C31")
      (value "0.1uF")
      (footprint "eagle-import:C0603")
      (libsource (lib "eagle-import") (part "CC0603"))
    )
    (comp (ref "C32")
      (value "10uF")
      (footprint "eagle-import:C0805")
      (libsource (lib "eagle-import") (part "C"))
    )
    (comp (ref "C33")
      (value "0.1uF")
      (footprint "eagle-import:C0603")
      (libsource (lib "eagle-import") (part "CC0603"))
    )
    (comp (ref "C34")
      (value "10pF")
      (footprint "eagle-import:C0603")
      (libsource (lib "eagle-import") (part "CC0603"))
    )
    (comp (ref "C35")
      (value "50pF")
      (footprint "eagle-import:C0603")
      (libsource (lib "eagle-import") (part "CC0603"))
    )
    (comp (ref "U4")
      (value "AD5791BRUZ")
      (footprint "eagle-import:SOP65P640X120-20N")
      (libsource (lib "eagle-import") (part "AD5791BRUZ"))
    )
    (comp (ref "U5")
      (value "AD8676ARZ")
      (footprint "eagle-import:SOIC127P600X175-8N")
      (libsource (lib "eagle-import") (part "AD8676ARZ"))
    )
    (comp (ref "C48")
      (value "10uF")
      (footprint "eagle-import:C0805")
      (libsource (lib "eagle-import") (part "C"))
    )
    (comp (ref "C49")
      (value "0.1uF")
      (footprint "eagle-import:C0603")
      (libsource (lib "eagle-import") (part "CC0603"))
    )
    (comp (ref "C50")
      (value "CC0603")
      (footprint "eagle-import:C0603")
      (libsource (lib "eagle-import") (part "CC0603"))
    )
    (comp (ref "C51")
      (value "10uF")
      (footprint "eagle-import:C0805")
      (libsource (lib "eagle-import") (part "C"))
    )
    (comp (ref "C52")
      (value "0.1uF")
      (footprint "eagle-import:C0603")
      (libsource (lib "eagle-import") (part "CC0603"))
    )
    (comp (ref "C53")
      (value "0.1uF")
      (footprint "eagle-import:C0603")
      (libsource (lib "eagle-import") (part "CC0603"))
    )
    (comp (ref "C54")
      (value "10uF")
      (footprint "eagle-import:C0805")
      (libsource (lib "eagle-import") (part "C"))
    )
    (comp (ref "C55")
      (value "0.1uF")
      (footprint "eagle-import:C0603")
      (libsource (lib "eagle-import") (part "CC0603"))
    )
    (comp (ref "C56")
      (value "10uF")
      (footprint "eagle-import:C0805")
      (libsource (lib "eagle-import") (part "C"))
    )
    (comp (ref "C57")
      (value "0.1uF")
      (footprint "eagle-import:C0603")
      (libsource (lib "eagle-import") (part "CC0603"))
    )
    (comp (ref "C58")
      (value "10pF")
      (footprint "eagle-import:C0603")
      (libsource (lib "eagle-import") (part "CC0603"))
    )
    (comp (ref "C59")
      (value "50pF")
      (footprint "eagle-import:C0603")
      (libsource (lib "eagle-import") (part "CC0603"))
    )
    (comp (ref "U8")
      (value "AD5791BRUZ")
      (footprint "eagle-import:SOP65P640X120-20N")
      (libsource (lib "eagle-import") (part "AD5791BRUZ"))
    )
    (comp (ref "U9")
      (value "AD8676ARZ")
      (footprint "eagle-import:SOIC127P600X175-8N")
      (libsource (lib "eagle-import") (part "AD8676ARZ"))
    )
    (comp (ref "C144")
      (value "10uF")
      (footprint "eagle-import:C0805")
      (libsource (lib "eagle-import") (part "C"))
    )
    (comp (ref "C145")
      (value "0.1uF")
      (footprint "eagle-import:C0603")
      (libsource (lib "eagle-import") (part "CC0603"))
    )
    (comp (ref "C146")
      (value "CC0603")
      (footprint "eagle-import:C0603")
      (libsource (lib "eagle-import") (part "CC0603"))
    )
    (comp (ref "C147")
      (value "10uF")
      (footprint "eagle-import:C0805")
      (libsource (lib "eagle-import") (part "C"))
    )
    (comp (ref "C148")
      (value "0.1uF")
      (footprint "eagle-import:C0603")
      (libsource (lib "eagle-import") (part "CC0603"))
    )
    (comp (ref "C149")
      (value "0.1uF")
      (footprint "eagle-import:C0603")
      (libsource (lib "eagle-import") (part "CC0603"))
    )
    (comp (ref "C150")
      (value "10uF")
      (footprint "eagle-import:C0805")
      (libsource (lib "eagle-import") (part "C"))
    )
    (comp (ref "C151")
      (value "0.1uF")
      (footprint "eagle-import:C0603")
      (libsource (lib "eagle-import") (part "CC0603"))
    )
    (comp (ref "C152")
      (value "10uF")
      (footprint "eagle-import:C0805")
      (libsource (lib "eagle-import") (part "C"))
    )
    (comp (ref "C153")
      (value "0.1uF")
      (footprint "eagle-import:C0603")
      (libsource (lib "eagle-import") (part "CC0603"))
    )
    (comp (ref "C154")
      (value "10pF")
      (footprint "eagle-import:C0603")
      (libsource (lib "eagle-import") (part "CC0603"))
    )
    (comp (ref "C155")
      (value "50pF")
      (footprint "eagle-import:C0603")
      (libsource (lib "eagle-import") (part "CC0603"))
    )
    (comp (ref "U24")
      (value "AD5791BRUZ")
      (footprint "eagle-import:SOP65P640X120-20N")
      (libsource (lib "eagle-import") (part "AD5791BRUZ"))
    )
    (comp (ref "U25")
      (value "AD8676ARZ")
      (footprint "eagle-import:SOIC127P600X175-8N")
      (libsource (lib "eagle-import") (part "AD8676ARZ"))
    )
    (comp (ref "C84")
      (value "10uF")
      (footprint "eagle-import:C0805")
      (libsource (lib "eagle-import") (part "C"))
    )
    (comp (ref "C85")
      (value "0.1uF")
      (footprint "eagle-import:C0603")
      (libsource (lib "eagle-import") (part "CC0603"))
    )
    (comp (ref "C86")
      (value "CC0603")
      (footprint "eagle-import:C0603")
      (libsource (lib "eagle-import") (part "CC0603"))
    )
    (comp (ref "C87")
      (value "10uF")
      (footprint "eagle-import:C0805")
      (libsource (lib "eagle-import") (part "C"))
    )
    (comp (ref "C88")
      (value "0.1uF")
      (footprint "eagle-import:C0603")
      (libsource (lib "eagle-import") (part "CC0603"))
    )
    (comp (ref "C89")
      (value "0.1uF")
      (footprint "eagle-import:C0603")
      (libsource (lib "eagle-import") (part "CC0603"))
    )
    (comp (ref "C90")
      (value "10uF")
      (footprint "eagle-import:C0805")
      (libsource (lib "eagle-import") (part "C"))
    )
    (comp (ref "C91")
      (value "0.1uF")
      (footprint "eagle-import:C0603")
      (libsource (lib "eagle-import") (part "CC0603"))
    )
    (comp (ref "C92")
      (value "10uF")
      (footprint "eagle-import:C0805")
      (libsource (lib "eagle-import") (part "C"))
    )
    (comp (ref "C93")
      (value "0.1uF")
      (footprint "eagle-import:C0603")
      (libsource (lib "eagle-import") (part "CC0603"))
    )
    (comp (ref "C94")
      (value "10pF")
      (footprint "eagle-import:C0603")
      (libsource (lib "eagle-import") (part "CC0603"))
    )
    (comp (ref "C95")
      (value "50pF")
      (footprint "eagle-import:C0603")
      (libsource (lib "eagle-import") (part "CC0603"))
    )
    (comp (ref "U14")
      (value "AD5791BRUZ")
      (footprint "eagle-import:SOP65P640X120-20N")
      (libsource (lib "eagle-import") (part "AD5791BRUZ"))
    )
    (comp (ref "U15")
      (value "AD8676ARZ")
      (footprint "eagle-import:SOIC127P600X175-8N")
      (libsource (lib "eagle-import") (part "AD8676ARZ"))
    )
    (comp (ref "C60")
      (value "10uF")
      (footprint "eagle-import:C0805")
      (libsource (lib "eagle-import") (part "C"))
    )
    (comp (ref "C61")
      (value "0.1uF")
      (footprint "eagle-import:C0603")
      (libsource (lib "eagle-import") (part "CC0603"))
    )
    (comp (ref "C62")
      (value "CC0603")
      (footprint "eagle-import:C0603")
      (libsource (lib "eagle-import") (part "CC0603"))
    )
    (comp (ref "C63")
      (value "10uF")
      (footprint "eagle-import:C0805")
      (libsource (lib "eagle-import") (part "C"))
    )
    (comp (ref "C64")
      (value "0.1uF")
      (footprint "eagle-import:C0603")
      (libsource (lib "eagle-import") (part "CC0603"))
    )
    (comp (ref "C65")
      (value "0.1uF")
      (footprint "eagle-import:C0603")
      (libsource (lib "eagle-import") (part "CC0603"))
    )
    (comp (ref "C66")
      (value "10uF")
      (footprint "eagle-import:C0805")
      (libsource (lib "eagle-import") (part "C"))
    )
    (comp (ref "C67")
      (value "0.1uF")
      (footprint "eagle-import:C0603")
      (libsource (lib "eagle-import") (part "CC0603"))
    )
    (comp (ref "C68")
      (value "10uF")
      (footprint "eagle-import:C0805")
      (libsource (lib "eagle-import") (part "C"))
    )
    (comp (ref "C69")
      (value "0.1uF")
      (footprint "eagle-import:C0603")
      (libsource (lib "eagle-import") (part "CC0603"))
    )
    (comp (ref "C70")
      (value "10pF")
      (footprint "eagle-import:C0603")
      (libsource (lib "eagle-import") (part "CC0603"))
    )
    (comp (ref "C71")
      (value "50pF")
      (footprint "eagle-import:C0603")
      (libsource (lib "eagle-import") (part "CC0603"))
    )
    (comp (ref "U10")
      (value "AD5791BRUZ")
      (footprint "eagle-import:SOP65P640X120-20N")
      (libsource (lib "eagle-import") (part "AD5791BRUZ"))
    )
    (comp (ref "U11")
      (value "AD8676ARZ")
      (footprint "eagle-import:SOIC127P600X175-8N")
      (libsource (lib "eagle-import") (part "AD8676ARZ"))
    )
    (comp (ref "560Ω")
      (value "560Ω")
      (footprint "eagle-import:R0603")
      (libsource (lib "eagle-import") (part "RR0603"))
    )
    (comp (ref "C168")
      (value "0.1uF")
      (footprint "eagle-import:C0603")
      (libsource (lib "eagle-import") (part "CC0603"))
    )
    (comp (ref "C169")
      (value "10uF")
      (footprint "eagle-import:C0805")
      (libsource (lib "eagle-import") (part "C"))
    )
    (comp (ref "C170")
      (value "0.1uF")
      (footprint "eagle-import:C0603")
      (libsource (lib "eagle-import") (part "CC0603"))
    )
    (comp (ref "C171")
      (value "10uF")
      (footprint "eagle-import:C0805")
      (libsource (lib "eagle-import") (part "C"))
    )
    (comp (ref "C172")
      (value "0.1uF")
      (footprint "eagle-import:C0603")
      (libsource (lib "eagle-import") (part "CC0603"))
    )
    (comp (ref "C173")
      (value "10uF")
      (footprint "eagle-import:C0805")
      (libsource (lib "eagle-import") (part "C"))
    )
    (comp (ref "C174")
      (value "0.1uF")
      (footprint "eagle-import:C0603")
      (libsource (lib "eagle-import") (part "CC0603"))
    )
    (comp (ref "C175")
      (value "10uF")
      (footprint "eagle-import:C0805")
      (libsource (lib "eagle-import") (part "C"))
    )
    (comp (ref "C176")
      (value "0.1uF")
      (footprint "eagle-import:C0603")
      (libsource (lib "eagle-import") (part "CC0603"))
    )
    (comp (ref "C177")
      (value "10uF")
      (footprint "eagle-import:C0805")
      (libsource (lib "eagle-import") (part "C"))
    )
    (comp (ref "C178")
      (value "0.1uF")
      (footprint "eagle-import:C0603")
      (libsource (lib "eagle-import") (part "CC0603"))
    )
    (comp (ref "C179")
      (value "10uF")
      (footprint "eagle-import:C0805")
      (libsource (lib "eagle-import") (part "C"))
    )
    (comp (ref "C180")
      (value "0.1uF")
      (footprint "eagle-import:C0603")
      (libsource (lib "eagle-import") (part "CC0603"))
    )
    (comp (ref "C181")
      (value "10uF")
      (footprint "eagle-import:C0805")
      (libsource (lib "eagle-import") (part "C"))
    )
    (comp (ref "C182")
      (value "0.1uF")
      (footprint "eagle-import:C0603")
      (libsource (lib "eagle-import") (part "CC0603"))
    )
    (comp (ref "C183")
      (value "10uF")
      (footprint "eagle-import:C0805")
      (libsource (lib "eagle-import") (part "C"))
    )
    (comp (ref "C184")
      (value "0.1uF")
      (footprint "eagle-import:C0603")
      (libsource (lib "eagle-import") (part "CC0603"))
    )
    (comp (ref "C185")
      (value "10uF")
      (footprint "eagle-import:C0805")
      (libsource (lib "eagle-import") (part "C"))
    )
    (comp (ref "C186")
      (value "0.1uF")
      (footprint "eagle-import:C0603")
      (libsource (lib "eagle-import") (part "CC0603"))
    )
    (comp (ref "C187")
      (value "10uF")
      (footprint "eagle-import:C0805")
      (libsource (lib "eagle-import") (part "C"))
    )
    (comp (ref "C188")
      (value "0.1uF")
      (footprint "eagle-import:C0603")
      (libsource (lib "eagle-import") (part "CC0603"))
    )
    (comp (ref "C189")
      (value "10uF")
      (footprint "eagle-import:C0805")
      (libsource (lib "eagle-import") (part "C"))
    )
    (comp (ref "C190")
      (value "0.1uF")
      (footprint "eagle-import:C0603")
      (libsource (lib "eagle-import") (part "CC0603"))
    )
    (comp (ref "C191")
      (value "10uF")
      (footprint "eagle-import:C0805")
      (libsource (lib "eagle-import") (part "C"))
    )
    (comp (ref "C192")
      (value "10uF")
      (footprint "eagle-import:C0805")
      (libsource (lib "eagle-import") (part "C"))
    )
    (comp (ref "C193")
      (value "10uF")
      (footprint "eagle-import:C0805")
      (libsource (lib "eagle-import") (part "C"))
    )
    (comp (ref "JP2")
      (value "JP6Q")
      (footprint "eagle-import:JP6Q")
      (libsource (lib "eagle-import") (part "JP6Q"))
    )
    (comp (ref "JP3")
      (value "JP6Q")
      (footprint "eagle-import:JP6Q")
      (libsource (lib "eagle-import") (part "JP6Q"))
    )
    (comp (ref "R4")
      (value "50Ω")
      (footprint "eagle-import:R0603")
      (libsource (lib "eagle-import") (part "RR0603"))
    )
    (comp (ref "R5")
      (value "50Ω")
      (footprint "eagle-import:R0603")
      (libsource (lib "eagle-import") (part "RR0603"))
    )
    (comp (ref "R8")
      (value "50Ω")
      (footprint "eagle-import:R0603")
      (libsource (lib "eagle-import") (part "RR0603"))
    )
    (comp (ref "R9")
      (value "50Ω")
      (footprint "eagle-import:R0603")
      (libsource (lib "eagle-import") (part "RR0603"))
    )
    (comp (ref "R10")
      (value "50Ω")
      (footprint "eagle-import:R0603")
      (libsource (lib "eagle-import") (part "RR0603"))
    )
    (comp (ref "R11")
      (value "50Ω")
      (footprint "eagle-import:R0603")
      (libsource (lib "eagle-import") (part "RR0603"))
    )
    (comp (ref "R12")
      (value "50Ω")
      (footprint "eagle-import:R0603")
      (libsource (lib "eagle-import") (part "RR0603"))
    )
    (comp (ref "R13")
      (value "50Ω")
      (footprint "eagle-import:R0603")
      (libsource (lib "eagle-import") (part "RR0603"))
    )
    (comp (ref "R14")
      (value "50Ω")
      (footprint "eagle-import:R0603")
      (libsource (lib "eagle-import") (part "RR0603"))
    )
    (comp (ref "R15")
      (value "50Ω")
      (footprint "eagle-import:R0603")
      (libsource (lib "eagle-import") (part "RR0603"))
    )
    (comp (ref "R16")
      (value "50Ω")
      (footprint "eagle-import:R0603")
      (libsource (lib "eagle-import") (part "RR0603"))
    )
    (comp (ref "R17")
      (value "50Ω")
      (footprint "eagle-import:R0603")
      (libsource (lib "eagle-import") (part "RR0603"))
    )
    (comp (ref "U28")
      (value "AD581KH")
      (footprint "eagle-import:TO254P939X470-3P")
      (libsource (lib "eagle-import") (part "AD581KH"))
    )
    (comp (ref "U29")
      (value "ADP3339-3.3")
      (footprint "eagle-import:SOT230P700X180-4N")
      (fields (field (name "MPN") "ADP3339AKCZ-3.3-R7"))
      (libsource (lib "eagle-import") (part "ADP3339AKCZ-3.3-R7"))
    )
    (comp (ref "U30")
      (value "AD8620ARZ")
      (footprint "eagle-import:SOIC127P600X175-8N")
      (libsource (lib "eagle-import") (part "AD8620ARZ"))
    )
    (comp (ref "U31")
      (value "AD8620ARZ")
      (footprint "eagle-import:SOIC127P600X175-8N")
      (libsource (lib "eagle-import") (part "AD8620ARZ"))
    )
    (comp (ref "U32")
      (value "AD8620ARZ")
      (footprint "eagle-import:SOIC127P600X175-8N")
      (libsource (lib "eagle-import") (part "AD8620ARZ"))
    )
    (comp (ref "U33")
      (value "AD8620ARZ")
      (footprint "eagle-import:SOIC127P600X175-8N")
      (libsource (lib "eagle-import") (part "AD8620ARZ"))
    )
    (comp (ref "U34")
      (value "AD8620ARZ")
      (footprint "eagle-import:SOIC127P600X175-8N")
      (libsource (lib "eagle-import") (part "AD8620ARZ"))
    )
    (comp (ref "U35")
      (value "AD8620ARZ")
      (footprint "eagle-import:SOIC127P600X175-8N")
      (libsource (lib "eagle-import") (part "AD8620ARZ"))
    )
    (comp (ref "X1")
      (value "F50HP")
      (footprint "eagle-import:F50HP")
      (libsource (lib "eagle-import") (part "F50HP"))
    )
    (comp (ref "C72")
      (value "10uF")
      (footprint "eagle-import:C0805")
      (libsource (lib "eagle-import") (part "C"))
    )
    (comp (ref "C73")
      (value "0.1uF")
      (footprint "eagle-import:C0603")
      (libsource (lib "eagle-import") (part "CC0603"))
    )
    (comp (ref "C74")
      (value "CC0603")
      (footprint "eagle-import:C0603")
      (libsource (lib "eagle-import") (part "CC0603"))
    )
    (comp (ref "C75")
      (value "10uF")
      (footprint "eagle-import:C0805")
      (libsource (lib "eagle-import") (part "C"))
    )
    (comp (ref "C76")
      (value "0.1uF")
      (footprint "eagle-import:C0603")
      (libsource (lib "eagle-import") (part "CC0603"))
    )
    (comp (ref "C77")
      (value "0.1uF")
      (footprint "eagle-import:C0603")
      (libsource (lib "eagle-import") (part "CC0603"))
    )
    (comp (ref "C78")
      (value "10uF")
      (footprint "eagle-import:C0805")
      (libsource (lib "eagle-import") (part "C"))
    )
    (comp (ref "C79")
      (value "0.1uF")
      (footprint "eagle-import:C0603")
      (libsource (lib "eagle-import") (part "CC0603"))
    )
    (comp (ref "C80")
      (value "10uF")
      (footprint "eagle-import:C0805")
      (libsource (lib "eagle-import") (part "C"))
    )
    (comp (ref "C81")
      (value "0.1uF")
      (footprint "eagle-import:C0603")
      (libsource (lib "eagle-import") (part "CC0603"))
    )
    (comp (ref "C82")
      (value "10pF")
      (footprint "eagle-import:C0603")
      (libsource (lib "eagle-import") (part "CC0603"))
    )
    (comp (ref "C83")
      (value "50pF")
      (footprint "eagle-import:C0603")
      (libsource (lib "eagle-import") (part "CC0603"))
    )
    (comp (ref "U12")
      (value "AD5791BRUZ")
      (footprint "eagle-import:SOP65P640X120-20N")
      (libsource (lib "eagle-import") (part "AD5791BRUZ"))
    )
    (comp (ref "U13")
      (value "AD8676ARZ")
      (footprint "eagle-import:SOIC127P600X175-8N")
      (libsource (lib "eagle-import") (part "AD8676ARZ"))
    )
  )
  (nets
    (net (code "1") (name "+5V") (class "Default")
      (node (ref "C193") (pin "1") (pinfunction "1_1") (pintype "passive"))
      (node (ref "J1") (pin "A27") (pinfunction "A27_A27") (pintype "passive"))
      (node (ref "J1") (pin "A28") (pinfunction "A28_A28") (pintype "passive"))
      (node (ref "J1") (pin "A29") (pinfunction "A29_A29") (pintype "passive"))
      (node (ref "J1") (pin "B27") (pinfunction "B27_B27") (pintype "passive"))
      (node (ref "J1") (pin "B28") (pinfunction "B28_B28") (pintype "passive"))
      (node (ref "J1") (pin "B29") (pinfunction "B29_B29") (pintype "passive"))
      (node (ref "J1") (pin "C27") (pinfunction "C27_C27") (pintype "passive"))
      (node (ref "J1") (pin "C28") (pinfunction "C28_C28") (pintype "passive"))
      (node (ref "J1") (pin "C29") (pinfunction "C29_C29") (pintype "passive"))
      (node (ref "J1") (pin "D27") (pinfunction "D27_D27") (pintype "passive"))
      (node (ref "J1") (pin "D28") (pinfunction "D28_D28") (pintype "passive"))
      (node (ref "J1") (pin "D29") (pinfunction "D29_D29") (pintype "passive"))
      (node (ref "J1") (pin "E27") (pinfunction "E27_E27") (pintype "passive"))
      (node (ref "J1") (pin "E28") (pinfunction "E28_E28") (pintype "passive"))
      (node (ref "J1") (pin "E29") (pinfunction "E29_E29") (pintype "passive"))
      (node (ref "U29") (pin "3") (pinfunction "IN_3") (pintype "input"))
    )
    (net (code "2") (name "+PWR") (class "Default")
      (node (ref "C170") (pin "1") (pinfunction "1_1") (pintype "passive"))
      (node (ref "C171") (pin "1") (pinfunction "1_1") (pintype "passive"))
      (node (ref "C174") (pin "1") (pinfunction "1_1") (pintype "passive"))
      (node (ref "C175") (pin "1") (pinfunction "1_1") (pintype "passive"))
      (node (ref "C178") (pin "1") (pinfunction "1_1") (pintype "passive"))
      (node (ref "C179") (pin "1") (pinfunction "1_1") (pintype "passive"))
      (node (ref "C182") (pin "1") (pinfunction "1_1") (pintype "passive"))
      (node (ref "C183") (pin "1") (pinfunction "1_1") (pintype "passive"))
      (node (ref "C186") (pin "1") (pinfunction "1_1") (pintype "passive"))
      (node (ref "C187") (pin "1") (pinfunction "1_1") (pintype "passive"))
      (node (ref "C190") (pin "1") (pinfunction "1_1") (pintype "passive"))
      (node (ref "C191") (pin "1") (pinfunction "1_1") (pintype "passive"))
      (node (ref "JP3") (pin "10") (pinfunction "10_10") (pintype "passive"))
      (node (ref "JP3") (pin "12") (pinfunction "12_12") (pintype "passive"))
      (node (ref "JP3") (pin "2") (pinfunction "2_2") (pintype "passive"))
      (node (ref "JP3") (pin "4") (pinfunction "4_4") (pintype "passive"))
      (node (ref "JP3") (pin "6") (pinfunction "6_6") (pintype "passive"))
      (node (ref "JP3") (pin "8") (pinfunction "8_8") (pintype "passive"))
      (node (ref "U30") (pin "8") (pinfunction "V+_8") (pintype "power_in"))
      (node (ref "U31") (pin "8") (pinfunction "V+_8") (pintype "power_in"))
      (node (ref "U32") (pin "8") (pinfunction "V+_8") (pintype "power_in"))
      (node (ref "U33") (pin "8") (pinfunction "V+_8") (pintype "power_in"))
      (node (ref "U34") (pin "8") (pinfunction "V+_8") (pintype "power_in"))
      (node (ref "U35") (pin "8") (pinfunction "V+_8") (pintype "power_in"))
    )
    (net (code "3") (name "+RAIL") (class "Default")
      (node (ref "J1") (pin "D41") (pinfunction "D41_D41") (pintype "passive"))
      (node (ref "J1") (pin "D42") (pinfunction "D42_D42") (pintype "passive"))
      (node (ref "J1") (pin "D43") (pinfunction "D43_D43") (pintype "passive"))
      (node (ref "J1") (pin "D44") (pinfunction "D44_D44") (pintype "passive"))
      (node (ref "J1") (pin "E41") (pinfunction "E41_E41") (pintype "passive"))
      (node (ref "J1") (pin "E42") (pinfunction "E42_E42") (pintype "passive"))
      (node (ref "J1") (pin "E43") (pinfunction "E43_E43") (pintype "passive"))
      (node (ref "J1") (pin "E44") (pinfunction "E44_E44") (pintype "passive"))
      (node (ref "JP3") (pin "1") (pinfunction "1_1") (pintype "passive"))
      (node (ref "JP3") (pin "3") (pinfunction "3_3") (pintype "passive"))
      (node (ref "JP3") (pin "5") (pinfunction "5_5") (pintype "passive"))
    )
    (net (code "4") (name "+VPRW") (class "Default")
      (node (ref "560Ω") (pin "2") (pinfunction "2_2") (pintype "passive"))
      (node (ref "U28") (pin "1") (pinfunction "+VS_1") (pintype "power_in"))
    )
    (net (code "5") (name "+VPWR") (class "Default")
      (node (ref "C102") (pin "2") (pinfunction "2_2") (pintype "passive"))
      (node (ref "C103") (pin "2") (pinfunction "2_2") (pintype "passive"))
      (node (ref "C108") (pin "2") (pinfunction "2_2") (pintype "passive"))
      (node (ref "C109") (pin "2") (pinfunction "2_2") (pintype "passive"))
      (node (ref "C11") (pin "2") (pinfunction "2_2") (pintype "passive"))
      (node (ref "C114") (pin "2") (pinfunction "2_2") (pintype "passive"))
      (node (ref "C115") (pin "2") (pinfunction "2_2") (pintype "passive"))
      (node (ref "C12") (pin "2") (pinfunction "2_2") (pintype "passive"))
      (node (ref "C120") (pin "2") (pinfunction "2_2") (pintype "passive"))
      (node (ref "C121") (pin "2") (pinfunction "2_2") (pintype "passive"))
      (node (ref "C126") (pin "2") (pinfunction "2_2") (pintype "passive"))
      (node (ref "C127") (pin "2") (pinfunction "2_2") (pintype "passive"))
      (node (ref "C132") (pin "2") (pinfunction "2_2") (pintype "passive"))
      (node (ref "C133") (pin "2") (pinfunction "2_2") (pintype "passive"))
      (node (ref "C138") (pin "2") (pinfunction "2_2") (pintype "passive"))
      (node (ref "C139") (pin "2") (pinfunction "2_2") (pintype "passive"))
      (node (ref "C144") (pin "2") (pinfunction "2_2") (pintype "passive"))
      (node (ref "C145") (pin "2") (pinfunction "2_2") (pintype "passive"))
      (node (ref "C150") (pin "2") (pinfunction "2_2") (pintype "passive"))
      (node (ref "C151") (pin "2") (pinfunction "2_2") (pintype "passive"))
      (node (ref "C156") (pin "2") (pinfunction "2_2") (pintype "passive"))
      (node (ref "C157") (pin "2") (pinfunction "2_2") (pintype "passive"))
      (node (ref "C162") (pin "2") (pinfunction "2_2") (pintype "passive"))
      (node (ref "C163") (pin "2") (pinfunction "2_2") (pintype "passive"))
      (node (ref "C30") (pin "2") (pinfunction "2_2") (pintype "passive"))
      (node (ref "C31") (pin "2") (pinfunction "2_2") (pintype "passive"))
      (node (ref "C36") (pin "2") (pinfunction "2_2") (pintype "passive"))
      (node (ref "C37") (pin "2") (pinfunction "2_2") (pintype "passive"))
      (node (ref "C42") (pin "2") (pinfunction "2_2") (pintype "passive"))
      (node (ref "C43") (pin "2") (pinfunction "2_2") (pintype "passive"))
      (node (ref "C48") (pin "2") (pinfunction "2_2") (pintype "passive"))
      (node (ref "C49") (pin "2") (pinfunction "2_2") (pintype "passive"))
      (node (ref "C54") (pin "2") (pinfunction "2_2") (pintype "passive"))
      (node (ref "C55") (pin "2") (pinfunction "2_2") (pintype "passive"))
      (node (ref "C60") (pin "2") (pinfunction "2_2") (pintype "passive"))
      (node (ref "C61") (pin "2") (pinfunction "2_2") (pintype "passive"))
      (node (ref "C66") (pin "2") (pinfunction "2_2") (pintype "passive"))
      (node (ref "C67") (pin "2") (pinfunction "2_2") (pintype "passive"))
      (node (ref "C72") (pin "2") (pinfunction "2_2") (pintype "passive"))
      (node (ref "C73") (pin "2") (pinfunction "2_2") (pintype "passive"))
      (node (ref "C78") (pin "2") (pinfunction "2_2") (pintype "passive"))
      (node (ref "C79") (pin "2") (pinfunction "2_2") (pintype "passive"))
      (node (ref "C84") (pin "2") (pinfunction "2_2") (pintype "passive"))
      (node (ref "C85") (pin "2") (pinfunction "2_2") (pintype "passive"))
      (node (ref "C90") (pin "2") (pinfunction "2_2") (pintype "passive"))
      (node (ref "C91") (pin "2") (pinfunction "2_2") (pintype "passive"))
      (node (ref "C96") (pin "2") (pinfunction "2_2") (pintype "passive"))
      (node (ref "C97") (pin "2") (pinfunction "2_2") (pintype "passive"))
      (node (ref "J1") (pin "D34") (pinfunction "D34_D34") (pintype "passive"))
      (node (ref "J1") (pin "D35") (pinfunction "D35_D35") (pintype "passive"))
      (node (ref "J1") (pin "D36") (pinfunction "D36_D36") (pintype "passive"))
      (node (ref "J1") (pin "D37") (pinfunction "D37_D37") (pintype "passive"))
      (node (ref "J1") (pin "E34") (pinfunction "E34_E34") (pintype "passive"))
      (node (ref "J1") (pin "E35") (pinfunction "E35_E35") (pintype "passive"))
      (node (ref "J1") (pin "E36") (pinfunction "E36_E36") (pintype "passive"))
      (node (ref "J1") (pin "E37") (pinfunction "E37_E37") (pintype "passive"))
      (node (ref "JP3") (pin "11") (pinfunction "11_11") (pintype "passive"))
      (node (ref "JP3") (pin "7") (pinfunction "7_7") (pintype "passive"))
      (node (ref "JP3") (pin "9") (pinfunction "9_9") (pintype "passive"))
      (node (ref "U10") (pin "5") (pinfunction "VDD_5") (pintype "power_in"))
      (node (ref "U11") (pin "8") (pinfunction "V+_8") (pintype "power_in"))
      (node (ref "U12") (pin "5") (pinfunction "VDD_5") (pintype "power_in"))
      (node (ref "U13") (pin "8") (pinfunction "V+_8") (pintype "power_in"))
      (node (ref "U14") (pin "5") (pinfunction "VDD_5") (pintype "power_in"))
      (node (ref "U15") (pin "8") (pinfunction "V+_8") (pintype "power_in"))
      (node (ref "U16") (pin "5") (pinfunction "VDD_5") (pintype "power_in"))
      (node (ref "U17") (pin "8") (pinfunction "V+_8") (pintype "power_in"))
      (node (ref "U18") (pin "5") (pinfunction "VDD_5") (pintype "power_in"))
      (node (ref "U19") (pin "8") (pinfunction "V+_8") (pintype "power_in"))
      (node (ref "U20") (pin "5") (pinfunction "VDD_5") (pintype "power_in"))
      (node (ref "U21") (pin "8") (pinfunction "V+_8") (pintype "power_in"))
      (node (ref "U22") (pin "5") (pinfunction "VDD_5") (pintype "power_in"))
      (node (ref "U23") (pin "8") (pinfunction "V+_8") (pintype "power_in"))
      (node (ref "U24") (pin "5") (pinfunction "VDD_5") (pintype "power_in"))
      (node (ref "U25") (pin "8") (pinfunction "V+_8") (pintype "power_in"))
      (node (ref "U26") (pin "5") (pinfunction "VDD_5") (pintype "power_in"))
      (node (ref "U27") (pin "8") (pinfunction "V+_8") (pintype "power_in"))
      (node (ref "U4") (pin "5") (pinfunction "VDD_5") (pintype "power_in"))
      (node (ref "U5") (pin "8") (pinfunction "V+_8") (pintype "power_in"))
      (node (ref "U6") (pin "5") (pinfunction "VDD_5") (pintype "power_in"))
      (node (ref "U7") (pin "8") (pinfunction "V+_8") (pintype "power_in"))
      (node (ref "U8") (pin "5") (pinfunction "VDD_5") (pintype "power_in"))
      (node (ref "U9") (pin "8") (pinfunction "V+_8") (pintype "power_in"))
      (node (ref "X1") (pin "1") (pinfunction "1_1") (pintype "passive"))
      (node (ref "X1") (pin "2") (pinfunction "2_2") (pintype "passive"))
    )
    (net (code "6") (name "-PWR") (class "Default")
      (node (ref "C168") (pin "1") (pinfunction "1_1") (pintype "passive"))
      (node (ref "C169") (pin "1") (pinfunction "1_1") (pintype "passive"))
      (node (ref "C172") (pin "1") (pinfunction "1_1") (pintype "passive"))
      (node (ref "C173") (pin "1") (pinfunction "1_1") (pintype "passive"))
      (node (ref "C176") (pin "1") (pinfunction "1_1") (pintype "passive"))
      (node (ref "C177") (pin "1") (pinfunction "1_1") (pintype "passive"))
      (node (ref "C180") (pin "1") (pinfunction "1_1") (pintype "passive"))
      (node (ref "C181") (pin "1") (pinfunction "1_1") (pintype "passive"))
      (node (ref "C184") (pin "1") (pinfunction "1_1") (pintype "passive"))
      (node (ref "C185") (pin "1") (pinfunction "1_1") (pintype "passive"))
      (node (ref "C188") (pin "1") (pinfunction "1_1") (pintype "passive"))
      (node (ref "C189") (pin "1") (pinfunction "1_1") (pintype "passive"))
      (node (ref "JP2") (pin "10") (pinfunction "10_10") (pintype "passive"))
      (node (ref "JP2") (pin "12") (pinfunction "12_12") (pintype "passive"))
      (node (ref "JP2") (pin "2") (pinfunction "2_2") (pintype "passive"))
      (node (ref "JP2") (pin "4") (pinfunction "4_4") (pintype "passive"))
      (node (ref "JP2") (pin "6") (pinfunction "6_6") (pintype "passive"))
      (node (ref "JP2") (pin "8") (pinfunction "8_8") (pintype "passive"))
      (node (ref "U30") (pin "4") (pinfunction "V-_4") (pintype "power_in"))
      (node (ref "U31") (pin "4") (pinfunction "V-_4") (pintype "power_in"))
      (node (ref "U32") (pin "4") (pinfunction "V-_4") (pintype "power_in"))
      (node (ref "U33") (pin "4") (pinfunction "V-_4") (pintype "power_in"))
      (node (ref "U34") (pin "4") (pinfunction "V-_4") (pintype "power_in"))
      (node (ref "U35") (pin "4") (pinfunction "V-_4") (pintype "power_in"))
    )
    (net (code "7") (name "-RAIL") (class "Default")
      (node (ref "J1") (pin "A41") (pinfunction "A41_A41") (pintype "passive"))
      (node (ref "J1") (pin "A42") (pinfunction "A42_A42") (pintype "passive"))
      (node (ref "J1") (pin "A43") (pinfunction "A43_A43") (pintype "passive"))
      (node (ref "J1") (pin "A44") (pinfunction "A44_A44") (pintype "passive"))
      (node (ref "J1") (pin "B41") (pinfunction "B41_B41") (pintype "passive"))
      (node (ref "J1") (pin "B42") (pinfunction "B42_B42") (pintype "passive"))
      (node (ref "J1") (pin "B43") (pinfunction "B43_B43") (pintype "passive"))
      (node (ref "J1") (pin "B44") (pinfunction "B44_B44") (pintype "passive"))
      (node (ref "JP2") (pin "1") (pinfunction "1_1") (pintype "passive"))
      (node (ref "JP2") (pin "3") (pinfunction "3_3") (pintype "passive"))
      (node (ref "JP2") (pin "5") (pinfunction "5_5") (pintype "passive"))
    )
    (net (code "8") (name "-VPWR") (class "Default")
      (node (ref "C100") (pin "2") (pinfunction "2_2") (pintype "passive"))
      (node (ref "C104") (pin "2") (pinfunction "2_2") (pintype "passive"))
      (node (ref "C105") (pin "2") (pinfunction "2_2") (pintype "passive"))
      (node (ref "C111") (pin "2") (pinfunction "2_2") (pintype "passive"))
      (node (ref "C112") (pin "2") (pinfunction "2_2") (pintype "passive"))
      (node (ref "C116") (pin "2") (pinfunction "2_2") (pintype "passive"))
      (node (ref "C117") (pin "2") (pinfunction "2_2") (pintype "passive"))
      (node (ref "C123") (pin "2") (pinfunction "2_2") (pintype "passive"))
      (node (ref "C124") (pin "2") (pinfunction "2_2") (pintype "passive"))
      (node (ref "C128") (pin "2") (pinfunction "2_2") (pintype "passive"))
      (node (ref "C129") (pin "2") (pinfunction "2_2") (pintype "passive"))
      (node (ref "C135") (pin "2") (pinfunction "2_2") (pintype "passive"))
      (node (ref "C136") (pin "2") (pinfunction "2_2") (pintype "passive"))
      (node (ref "C140") (pin "2") (pinfunction "2_2") (pintype "passive"))
      (node (ref "C141") (pin "2") (pinfunction "2_2") (pintype "passive"))
      (node (ref "C147") (pin "2") (pinfunction "2_2") (pintype "passive"))
      (node (ref "C148") (pin "2") (pinfunction "2_2") (pintype "passive"))
      (node (ref "C152") (pin "2") (pinfunction "2_2") (pintype "passive"))
      (node (ref "C153") (pin "2") (pinfunction "2_2") (pintype "passive"))
      (node (ref "C159") (pin "2") (pinfunction "2_2") (pintype "passive"))
      (node (ref "C160") (pin "2") (pinfunction "2_2") (pintype "passive"))
      (node (ref "C164") (pin "2") (pinfunction "2_2") (pintype "passive"))
      (node (ref "C165") (pin "2") (pinfunction "2_2") (pintype "passive"))
      (node (ref "C27") (pin "2") (pinfunction "2_2") (pintype "passive"))
      (node (ref "C28") (pin "2") (pinfunction "2_2") (pintype "passive"))
      (node (ref "C32") (pin "2") (pinfunction "2_2") (pintype "passive"))
      (node (ref "C33") (pin "2") (pinfunction "2_2") (pintype "passive"))
      (node (ref "C39") (pin "2") (pinfunction "2_2") (pintype "passive"))
      (node (ref "C40") (pin "2") (pinfunction "2_2") (pintype "passive"))
      (node (ref "C44") (pin "2") (pinfunction "2_2") (pintype "passive"))
      (node (ref "C45") (pin "2") (pinfunction "2_2") (pintype "passive"))
      (node (ref "C51") (pin "2") (pinfunction "2_2") (pintype "passive"))
      (node (ref "C52") (pin "2") (pinfunction "2_2") (pintype "passive"))
      (node (ref "C56") (pin "2") (pinfunction "2_2") (pintype "passive"))
      (node (ref "C57") (pin "2") (pinfunction "2_2") (pintype "passive"))
      (node (ref "C63") (pin "2") (pinfunction "2_2") (pintype "passive"))
      (node (ref "C64") (pin "2") (pinfunction "2_2") (pintype "passive"))
      (node (ref "C68") (pin "2") (pinfunction "2_2") (pintype "passive"))
      (node (ref "C69") (pin "2") (pinfunction "2_2") (pintype "passive"))
      (node (ref "C75") (pin "2") (pinfunction "2_2") (pintype "passive"))
      (node (ref "C76") (pin "2") (pinfunction "2_2") (pintype "passive"))
      (node (ref "C80") (pin "2") (pinfunction "2_2") (pintype "passive"))
      (node (ref "C81") (pin "2") (pinfunction "2_2") (pintype "passive"))
      (node (ref "C87") (pin "2") (pinfunction "2_2") (pintype "passive"))
      (node (ref "C88") (pin "2") (pinfunction "2_2") (pintype "passive"))
      (node (ref "C92") (pin "2") (pinfunction "2_2") (pintype "passive"))
      (node (ref "C93") (pin "2") (pinfunction "2_2") (pintype "passive"))
      (node (ref "C99") (pin "2") (pinfunction "2_2") (pintype "passive"))
      (node (ref "J1") (pin "A34") (pinfunction "A34_A34") (pintype "passive"))
      (node (ref "J1") (pin "A35") (pinfunction "A35_A35") (pintype "passive"))
      (node (ref "J1") (pin "A36") (pinfunction "A36_A36") (pintype "passive"))
      (node (ref "J1") (pin "A37") (pinfunction "A37_A37") (pintype "passive"))
      (node (ref "J1") (pin "B34") (pinfunction "B34_B34") (pintype "passive"))
      (node (ref "J1") (pin "B35") (pinfunction "B35_B35") (pintype "passive"))
      (node (ref "J1") (pin "B36") (pinfunction "B36_B36") (pintype "passive"))
      (node (ref "J1") (pin "B37") (pinfunction "B37_B37") (pintype "passive"))
      (node (ref "JP2") (pin "11") (pinfunction "11_11") (pintype "passive"))
      (node (ref "JP2") (pin "7") (pinfunction "7_7") (pintype "passive"))
      (node (ref "JP2") (pin "9") (pinfunction "9_9") (pintype "passive"))
      (node (ref "U10") (pin "18") (pinfunction "VSS_18") (pintype "power_in"))
      (node (ref "U11") (pin "4") (pinfunction "V-_4") (pintype "power_in"))
      (node (ref "U12") (pin "18") (pinfunction "VSS_18") (pintype "power_in"))
      (node (ref "U13") (pin "4") (pinfunction "V-_4") (pintype "power_in"))
      (node (ref "U14") (pin "18") (pinfunction "VSS_18") (pintype "power_in"))
      (node (ref "U15") (pin "4") (pinfunction "V-_4") (pintype "power_in"))
      (node (ref "U16") (pin "18") (pinfunction "VSS_18") (pintype "power_in"))
      (node (ref "U17") (pin "4") (pinfunction "V-_4") (pintype "power_in"))
      (node (ref "U18") (pin "18") (pinfunction "VSS_18") (pintype "power_in"))
      (node (ref "U19") (pin "4") (pinfunction "V-_4") (pintype "power_in"))
      (node (ref "U20") (pin "18") (pinfunction "VSS_18") (pintype "power_in"))
      (node (ref "U21") (pin "4") (pinfunction "V-_4") (pintype "power_in"))
      (node (ref "U22") (pin "18") (pinfunction "VSS_18") (pintype "power_in"))
      (node (ref "U23") (pin "4") (pinfunction "V-_4") (pintype "power_in"))
      (node (ref "U24") (pin "18") (pinfunction "VSS_18") (pintype "power_in"))
      (node (ref "U25") (pin "4") (pinfunction "V-_4") (pintype "power_in"))
      (node (ref "U26") (pin "18") (pinfunction "VSS_18") (pintype "power_in"))
      (node (ref "U27") (pin "4") (pinfunction "V-_4") (pintype "power_in"))
      (node (ref "U4") (pin "18") (pinfunction "VSS_18") (pintype "power_in"))
      (node (ref "U5") (pin "4") (pinfunction "V-_4") (pintype "power_in"))
      (node (ref "U6") (pin "18") (pinfunction "VSS_18") (pintype "power_in"))
      (node (ref "U7") (pin "4") (pinfunction "V-_4") (pintype "power_in"))
      (node (ref "U8") (pin "18") (pinfunction "VSS_18") (pintype "power_in"))
      (node (ref "U9") (pin "4") (pinfunction "V-_4") (pintype "power_in"))
      (node (ref "X1") (pin "34") (pinfunction "34_34") (pintype "passive"))
      (node (ref "X1") (pin "35") (pinfunction "35_35") (pintype "passive"))
    )
    (net (code "9") (name "0B0") (class "Default")
      (node (ref "ISO1") (pin "4") (pinfunction "A2_4") (pintype "bidirectional"))
      (node (ref "U2") (pin "3") (pinfunction "A1_3") (pintype "bidirectional"))
    )
    (net (code "10") (name "0B1") (class "Default")
      (node (ref "ISO1") (pin "3") (pinfunction "A1_3") (pintype "bidirectional"))
      (node (ref "U2") (pin "5") (pinfunction "A2_5") (pintype "bidirectional"))
    )
    (net (code "11") (name "0B2") (class "Default")
      (node (ref "ISO2") (pin "7") (pinfunction "A5_7") (pintype "bidirectional"))
      (node (ref "U2") (pin "6") (pinfunction "A3_6") (pintype "bidirectional"))
    )
    (net (code "12") (name "0B3") (class "Default")
      (node (ref "ISO2") (pin "6") (pinfunction "A4_6") (pintype "bidirectional"))
      (node (ref "U2") (pin "8") (pinfunction "A4_8") (pintype "bidirectional"))
    )
    (net (code "13") (name "0B4") (class "Default")
      (node (ref "ISO2") (pin "5") (pinfunction "A3_5") (pintype "bidirectional"))
      (node (ref "U2") (pin "9") (pinfunction "A5_9") (pintype "bidirectional"))
    )
    (net (code "14") (name "0B5") (class "Default")
      (node (ref "ISO2") (pin "4") (pinfunction "A2_4") (pintype "bidirectional"))
      (node (ref "U2") (pin "10") (pinfunction "A6_10") (pintype "bidirectional"))
    )
    (net (code "15") (name "0B6") (class "Default")
      (node (ref "ISO2") (pin "3") (pinfunction "A1_3") (pintype "bidirectional"))
      (node (ref "U2") (pin "12") (pinfunction "A7_12") (pintype "bidirectional"))
    )
    (net (code "16") (name "0B7") (class "Default")
      (node (ref "ISO3") (pin "7") (pinfunction "A5_7") (pintype "bidirectional"))
      (node (ref "U2") (pin "13") (pinfunction "A8_13") (pintype "bidirectional"))
    )
    (net (code "17") (name "0B8") (class "Default")
      (node (ref "ISO3") (pin "6") (pinfunction "A4_6") (pintype "bidirectional"))
      (node (ref "U2") (pin "14") (pinfunction "A9_14") (pintype "bidirectional"))
    )
    (net (code "18") (name "0B9") (class "Default")
      (node (ref "ISO3") (pin "5") (pinfunction "A3_5") (pintype "bidirectional"))
      (node (ref "U2") (pin "15") (pinfunction "A10_15") (pintype "bidirectional"))
    )
    (net (code "19") (name "0B10") (class "Default")
      (node (ref "ISO3") (pin "4") (pinfunction "A2_4") (pintype "bidirectional"))
      (node (ref "U2") (pin "16") (pinfunction "A11_16") (pintype "bidirectional"))
    )
    (net (code "20") (name "0B11") (class "Default")
      (node (ref "ISO3") (pin "3") (pinfunction "A1_3") (pintype "bidirectional"))
      (node (ref "U2") (pin "17") (pinfunction "A12_17") (pintype "bidirectional"))
    )
    (net (code "21") (name "0B12") (class "Default")
      (node (ref "ISO4") (pin "7") (pinfunction "A5_7") (pintype "bidirectional"))
      (node (ref "U2") (pin "19") (pinfunction "A13_19") (pintype "bidirectional"))
    )
    (net (code "22") (name "0B13") (class "Default")
      (node (ref "ISO4") (pin "6") (pinfunction "A4_6") (pintype "bidirectional"))
      (node (ref "U2") (pin "20") (pinfunction "A14_20") (pintype "bidirectional"))
    )
    (net (code "23") (name "0B14") (class "Default")
      (node (ref "ISO4") (pin "5") (pinfunction "A3_5") (pintype "bidirectional"))
      (node (ref "U2") (pin "21") (pinfunction "A15_21") (pintype "bidirectional"))
    )
    (net (code "24") (name "0B15") (class "Default")
      (node (ref "ISO4") (pin "4") (pinfunction "A2_4") (pintype "bidirectional"))
      (node (ref "U2") (pin "23") (pinfunction "A16_23") (pintype "bidirectional"))
    )
    (net (code "25") (name "0B16") (class "Default")
      (node (ref "ISO4") (pin "3") (pinfunction "A1_3") (pintype "bidirectional"))
      (node (ref "U2") (pin "24") (pinfunction "A17_24") (pintype "bidirectional"))
    )
    (net (code "26") (name "0B17") (class "Default")
      (node (ref "ISO5") (pin "7") (pinfunction "A5_7") (pintype "bidirectional"))
      (node (ref "U2") (pin "26") (pinfunction "A18_26") (pintype "bidirectional"))
    )
    (net (code "27") (name "1B0") (class "Default")
      (node (ref "ISO5") (pin "6") (pinfunction "A4_6") (pintype "bidirectional"))
      (node (ref "U3") (pin "3") (pinfunction "A1_3") (pintype "bidirectional"))
    )
    (net (code "28") (name "1B1") (class "Default")
      (node (ref "ISO5") (pin "5") (pinfunction "A3_5") (pintype "bidirectional"))
      (node (ref "U3") (pin "5") (pinfunction "A2_5") (pintype "bidirectional"))
    )
    (net (code "29") (name "1B2") (class "Default")
      (node (ref "ISO5") (pin "4") (pinfunction "A2_4") (pintype "bidirectional"))
      (node (ref "U3") (pin "6") (pinfunction "A3_6") (pintype "bidirectional"))
    )
    (net (code "30") (name "1B3") (class "Default")
      (node (ref "ISO5") (pin "3") (pinfunction "A1_3") (pintype "bidirectional"))
      (node (ref "U3") (pin "8") (pinfunction "A4_8") (pintype "bidirectional"))
    )
    (net (code "31") (name "1B4") (class "Default")
      (node (ref "ISO6") (pin "7") (pinfunction "A5_7") (pintype "bidirectional"))
      (node (ref "U3") (pin "9") (pinfunction "A5_9") (pintype "bidirectional"))
    )
    (net (code "32") (name "1B5") (class "Default")
      (node (ref "ISO6") (pin "6") (pinfunction "A4_6") (pintype "bidirectional"))
      (node (ref "U3") (pin "10") (pinfunction "A6_10") (pintype "bidirectional"))
    )
    (net (code "33") (name "1B6") (class "Default")
      (node (ref "ISO6") (pin "5") (pinfunction "A3_5") (pintype "bidirectional"))
      (node (ref "U3") (pin "12") (pinfunction "A7_12") (pintype "bidirectional"))
    )
    (net (code "34") (name "1B7") (class "Default")
      (node (ref "ISO6") (pin "4") (pinfunction "A2_4") (pintype "bidirectional"))
      (node (ref "U3") (pin "13") (pinfunction "A8_13") (pintype "bidirectional"))
    )
    (net (code "35") (name "1B8") (class "Default")
      (node (ref "ISO6") (pin "3") (pinfunction "A1_3") (pintype "bidirectional"))
      (node (ref "U3") (pin "14") (pinfunction "A9_14") (pintype "bidirectional"))
    )
    (net (code "36") (name "1B9") (class "Default")
      (node (ref "ISO7") (pin "7") (pinfunction "A5_7") (pintype "bidirectional"))
      (node (ref "U3") (pin "15") (pinfunction "A10_15") (pintype "bidirectional"))
    )
    (net (code "37") (name "1B10") (class "Default")
      (node (ref "ISO7") (pin "6") (pinfunction "A4_6") (pintype "bidirectional"))
      (node (ref "U3") (pin "16") (pinfunction "A11_16") (pintype "bidirectional"))
    )
    (net (code "38") (name "1B11") (class "Default")
      (node (ref "ISO7") (pin "5") (pinfunction "A3_5") (pintype "bidirectional"))
      (node (ref "U3") (pin "17") (pinfunction "A12_17") (pintype "bidirectional"))
    )
    (net (code "39") (name "1B12") (class "Default")
      (node (ref "ISO7") (pin "4") (pinfunction "A2_4") (pintype "bidirectional"))
      (node (ref "U3") (pin "19") (pinfunction "A13_19") (pintype "bidirectional"))
    )
    (net (code "40") (name "1B13") (class "Default")
      (node (ref "ISO7") (pin "3") (pinfunction "A1_3") (pintype "bidirectional"))
      (node (ref "U3") (pin "20") (pinfunction "A14_20") (pintype "bidirectional"))
    )
    (net (code "41") (name "1B14") (class "Default")
      (node (ref "ISO8") (pin "7") (pinfunction "A5_7") (pintype "bidirectional"))
      (node (ref "U3") (pin "21") (pinfunction "A15_21") (pintype "bidirectional"))
    )
    (net (code "42") (name "1B15") (class "Default")
      (node (ref "ISO8") (pin "6") (pinfunction "A4_6") (pintype "bidirectional"))
      (node (ref "U3") (pin "23") (pinfunction "A16_23") (pintype "bidirectional"))
    )
    (net (code "43") (name "1B16") (class "Default")
      (node (ref "ISO8") (pin "5") (pinfunction "A3_5") (pintype "bidirectional"))
      (node (ref "U3") (pin "24") (pinfunction "A17_24") (pintype "bidirectional"))
    )
    (net (code "44") (name "1B17") (class "Default")
      (node (ref "ISO8") (pin "4") (pinfunction "A2_4") (pintype "bidirectional"))
      (node (ref "U3") (pin "26") (pinfunction "A18_26") (pintype "bidirectional"))
    )
    (net (code "45") (name "2B0-1") (class "Default")
      (node (ref "ISO8") (pin "3") (pinfunction "A1_3") (pintype "bidirectional"))
      (node (ref "U40") (pin "6") (pinfunction "1A2_6") (pintype "bidirectional"))
    )
    (net (code "46") (name "2B0-2") (class "Default")
      (node (ref "ISO11") (pin "7") (pinfunction "A5_7") (pintype "bidirectional"))
      (node (ref "U40") (pin "7") (pinfunction "1A3_7") (pintype "bidirectional"))
    )
    (net (code "47") (name "2B0-3") (class "Default")
      (node (ref "ISO11") (pin "6") (pinfunction "A4_6") (pintype "bidirectional"))
      (node (ref "U40") (pin "9") (pinfunction "1A4_9") (pintype "bidirectional"))
    )
    (net (code "48") (name "2B0-4") (class "Default")
      (node (ref "ISO11") (pin "5") (pinfunction "A3_5") (pintype "bidirectional"))
      (node (ref "U40") (pin "11") (pinfunction "1A5_11") (pintype "bidirectional"))
    )
    (net (code "49") (name "2B0-5") (class "Default")
      (node (ref "ISO11") (pin "4") (pinfunction "A2_4") (pintype "bidirectional"))
      (node (ref "U40") (pin "13") (pinfunction "1A6_13") (pintype "bidirectional"))
    )
    (net (code "50") (name "2B0-7") (class "Default")
      (node (ref "ISO11") (pin "3") (pinfunction "A1_3") (pintype "bidirectional"))
      (node (ref "U40") (pin "16") (pinfunction "1A8_16") (pintype "bidirectional"))
    )
    (net (code "51") (name "2B1-0") (class "Default")
      (node (ref "ISO9") (pin "14") (pinfunction "B1_14") (pintype "bidirectional"))
      (node (ref "U40") (pin "17") (pinfunction "2A1_17") (pintype "bidirectional"))
    )
    (net (code "52") (name "2B1-1") (class "Default")
      (node (ref "ISO9") (pin "13") (pinfunction "B2_13") (pintype "bidirectional"))
      (node (ref "U40") (pin "19") (pinfunction "2A2_19") (pintype "bidirectional"))
    )
    (net (code "53") (name "2B1-2") (class "Default")
      (node (ref "ISO9") (pin "12") (pinfunction "B3_12") (pintype "bidirectional"))
      (node (ref "U40") (pin "20") (pinfunction "2A3_20") (pintype "bidirectional"))
    )
    (net (code "54") (name "2B1-3") (class "Default")
      (node (ref "ISO9") (pin "11") (pinfunction "B4_11") (pintype "bidirectional"))
      (node (ref "U40") (pin "22") (pinfunction "2A4_22") (pintype "bidirectional"))
    )
    (net (code "55") (name "2B1-4") (class "Default")
      (node (ref "ISO9") (pin "10") (pinfunction "B5_10") (pintype "bidirectional"))
      (node (ref "U40") (pin "23") (pinfunction "2A5_23") (pintype "bidirectional"))
    )
    (net (code "56") (name "2B1-5") (class "Default")
      (node (ref "ISO10") (pin "14") (pinfunction "B1_14") (pintype "bidirectional"))
      (node (ref "U40") (pin "25") (pinfunction "2A6_25") (pintype "bidirectional"))
    )
    (net (code "57") (name "2B1-6") (class "Default")
      (node (ref "ISO10") (pin "13") (pinfunction "B2_13") (pintype "bidirectional"))
      (node (ref "U40") (pin "27") (pinfunction "2A7_27") (pintype "bidirectional"))
    )
    (net (code "58") (name "2B1-7") (class "Default")
      (node (ref "ISO10") (pin "12") (pinfunction "B3_12") (pintype "bidirectional"))
      (node (ref "U40") (pin "29") (pinfunction "2A8_29") (pintype "bidirectional"))
    )
    (net (code "59") (name "ANALOG_REF") (class "Default")
      (node (ref "560Ω") (pin "1") (pinfunction "1_1") (pintype "passive"))
      (node (ref "C101") (pin "1") (pinfunction "1_1") (pintype "passive"))
      (node (ref "C113") (pin "1") (pinfunction "1_1") (pintype "passive"))
      (node (ref "C125") (pin "1") (pinfunction "1_1") (pintype "passive"))
      (node (ref "C137") (pin "1") (pinfunction "1_1") (pintype "passive"))
      (node (ref "C149") (pin "1") (pinfunction "1_1") (pintype "passive"))
      (node (ref "C161") (pin "1") (pinfunction "1_1") (pintype "passive"))
      (node (ref "C29") (pin "1") (pinfunction "1_1") (pintype "passive"))
      (node (ref "C41") (pin "1") (pinfunction "1_1") (pintype "passive"))
      (node (ref "C53") (pin "1") (pinfunction "1_1") (pintype "passive"))
      (node (ref "C65") (pin "1") (pinfunction "1_1") (pintype "passive"))
      (node (ref "C77") (pin "1") (pinfunction "1_1") (pintype "passive"))
      (node (ref "C89") (pin "1") (pinfunction "1_1") (pintype "passive"))
      (node (ref "U11") (pin "3") (pinfunction "+IN_A_3") (pintype "input"))
      (node (ref "U13") (pin "3") (pinfunction "+IN_A_3") (pintype "input"))
      (node (ref "U15") (pin "3") (pinfunction "+IN_A_3") (pintype "input"))
      (node (ref "U17") (pin "3") (pinfunction "+IN_A_3") (pintype "input"))
      (node (ref "U19") (pin "3") (pinfunction "+IN_A_3") (pintype "input"))
      (node (ref "U21") (pin "3") (pinfunction "+IN_A_3") (pintype "input"))
      (node (ref "U23") (pin "3") (pinfunction "+IN_A_3") (pintype "input"))
      (node (ref "U25") (pin "3") (pinfunction "+IN_A_3") (pintype "input"))
      (node (ref "U27") (pin "3") (pinfunction "+IN_A_3") (pintype "input"))
      (node (ref "U28") (pin "2") (pinfunction "VOUT_2") (pintype "output"))
      (node (ref "U5") (pin "3") (pinfunction "+IN_A_3") (pintype "input"))
      (node (ref "U7") (pin "3") (pinfunction "+IN_A_3") (pintype "input"))
      (node (ref "U9") (pin "3") (pinfunction "+IN_A_3") (pintype "input"))
    )
    (net (code "60") (name "CSIN") (class "Default")
      (node (ref "ISO1") (pin "12") (pinfunction "B3_12") (pintype "bidirectional"))
    )
    (net (code "61") (name "CSOUT") (class "Default")
      (node (ref "ISO1") (pin "11") (pinfunction "B4_11") (pintype "bidirectional"))
    )
    (net (code "62") (name "DACO_1") (class "Default")
      (node (ref "C35") (pin "2") (pinfunction "2_2") (pintype "passive"))
      (node (ref "U30") (pin "5") (pinfunction "+INB_5") (pintype "input"))
      (node (ref "U4") (pin "2") (pinfunction "VOUT_2") (pintype "output"))
    )
    (net (code "63") (name "DACO_2") (class "Default")
      (node (ref "C47") (pin "2") (pinfunction "2_2") (pintype "passive"))
      (node (ref "U31") (pin "5") (pinfunction "+INB_5") (pintype "input"))
      (node (ref "U6") (pin "2") (pinfunction "VOUT_2") (pintype "output"))
    )
    (net (code "64") (name "DACO_3") (class "Default")
      (node (ref "C59") (pin "2") (pinfunction "2_2") (pintype "passive"))
      (node (ref "U32") (pin "5") (pinfunction "+INB_5") (pintype "input"))
      (node (ref "U8") (pin "2") (pinfunction "VOUT_2") (pintype "output"))
    )
    (net (code "65") (name "DACO_4") (class "Default")
      (node (ref "C71") (pin "2") (pinfunction "2_2") (pintype "passive"))
      (node (ref "U10") (pin "2") (pinfunction "VOUT_2") (pintype "output"))
      (node (ref "U33") (pin "5") (pinfunction "+INB_5") (pintype "input"))
    )
    (net (code "66") (name "DACO_5") (class "Default")
      (node (ref "C83") (pin "2") (pinfunction "2_2") (pintype "passive"))
      (node (ref "U12") (pin "2") (pinfunction "VOUT_2") (pintype "output"))
      (node (ref "U34") (pin "5") (pinfunction "+INB_5") (pintype "input"))
    )
    (net (code "67") (name "DACO_6") (class "Default")
      (node (ref "C95") (pin "2") (pinfunction "2_2") (pintype "passive"))
      (node (ref "U14") (pin "2") (pinfunction "VOUT_2") (pintype "output"))
      (node (ref "U35") (pin "5") (pinfunction "+INB_5") (pintype "input"))
    )
    (net (code "68") (name "DACO_7") (class "Default")
      (node (ref "C107") (pin "2") (pinfunction "2_2") (pintype "passive"))
      (node (ref "U16") (pin "2") (pinfunction "VOUT_2") (pintype "output"))
      (node (ref "U30") (pin "3") (pinfunction "+INA_3") (pintype "input"))
    )
    (net (code "69") (name "DACO_8") (class "Default")
      (node (ref "C119") (pin "2") (pinfunction "2_2") (pintype "passive"))
      (node (ref "U18") (pin "2") (pinfunction "VOUT_2") (pintype "output"))
      (node (ref "U31") (pin "3") (pinfunction "+INA_3") (pintype "input"))
    )
    (net (code "70") (name "DACO_9") (class "Default")
      (node (ref "C131") (pin "2") (pinfunction "2_2") (pintype "passive"))
      (node (ref "U20") (pin "2") (pinfunction "VOUT_2") (pintype "output"))
      (node (ref "U32") (pin "3") (pinfunction "+INA_3") (pintype "input"))
    )
    (net (code "71") (name "DACO_10") (class "Default")
      (node (ref "C143") (pin "2") (pinfunction "2_2") (pintype "passive"))
      (node (ref "U22") (pin "2") (pinfunction "VOUT_2") (pintype "output"))
      (node (ref "U33") (pin "3") (pinfunction "+INA_3") (pintype "input"))
    )
    (net (code "72") (name "DACO_11") (class "Default")
      (node (ref "C155") (pin "2") (pinfunction "2_2") (pintype "passive"))
      (node (ref "U24") (pin "2") (pinfunction "VOUT_2") (pintype "output"))
      (node (ref "U34") (pin "3") (pinfunction "+INA_3") (pintype "input"))
    )
    (net (code "73") (name "DACO_12") (class "Default")
      (node (ref "C167") (pin "2") (pinfunction "2_2") (pintype "passive"))
      (node (ref "U26") (pin "2") (pinfunction "VOUT_2") (pintype "output"))
      (node (ref "U35") (pin "3") (pinfunction "+INA_3") (pintype "input"))
    )
    (net (code "74") (name "DAUX0") (class "Default")
      (node (ref "J1") (pin "A1") (pinfunction "A1_A1") (pintype "passive"))
    )
    (net (code "75") (name "DAUX1") (class "Default")
      (node (ref "J1") (pin "D23") (pinfunction "D23_D23") (pintype "passive"))
    )
    (net (code "76") (name "DAUX2") (class "Default")
      (node (ref "J1") (pin "E24") (pinfunction "E24_E24") (pintype "passive"))
    )
    (net (code "77") (name "DAUX3") (class "Default")
      (node (ref "J1") (pin "C24") (pinfunction "C24_C24") (pintype "passive"))
    )
    (net (code "78") (name "DCLK0") (class "Default")
      (node (ref "ISO11") (pin "14") (pinfunction "B1_14") (pintype "bidirectional"))
      (node (ref "X1") (pin "50") (pinfunction "50_50") (pintype "passive"))
    )
    (net (code "79") (name "DCLK1") (class "Default")
      (node (ref "ISO11") (pin "13") (pinfunction "B2_13") (pintype "bidirectional"))
      (node (ref "X1") (pin "33") (pinfunction "33_33") (pintype "passive"))
    )
    (net (code "80") (name "DCLK2") (class "Default")
      (node (ref "ISO11") (pin "12") (pinfunction "B3_12") (pintype "bidirectional"))
      (node (ref "X1") (pin "16") (pinfunction "16_16") (pintype "passive"))
    )
    (net (code "81") (name "DCLK3") (class "Default")
      (node (ref "ISO11") (pin "11") (pinfunction "B4_11") (pintype "bidirectional"))
      (node (ref "X1") (pin "49") (pinfunction "49_49") (pintype "passive"))
    )
    (net (code "82") (name "DCLK5") (class "Default")
      (node (ref "ISO8") (pin "14") (pinfunction "B1_14") (pintype "bidirectional"))
      (node (ref "X1") (pin "17") (pinfunction "17_17") (pintype "passive"))
    )
    (net (code "83") (name "DGND") (class "Default")
      (node (ref "C1") (pin "2") (pinfunction "2_2") (pintype "passive"))
      (node (ref "C10") (pin "2") (pinfunction "2_2") (pintype "passive"))
      (node (ref "C13") (pin "2") (pinfunction "2_2") (pintype "passive"))
      (node (ref "C14") (pin "2") (pinfunction "2_2") (pintype "passive"))
      (node (ref "C15") (pin "2") (pinfunction "2_2") (pintype "passive"))
      (node (ref "C16") (pin "2") (pinfunction "2_2") (pintype "passive"))
      (node (ref "C17") (pin "2") (pinfunction "2_2") (pintype "passive"))
      (node (ref "C18") (pin "2") (pinfunction "2_2") (pintype "passive"))
      (node (ref "C19") (pin "2") (pinfunction "2_2") (pintype "passive"))
      (node (ref "C2") (pin "2") (pinfunction "2_2") (pintype "passive"))
      (node (ref "C20") (pin "2") (pinfunction "2_2") (pintype "passive"))
      (node (ref "C21") (pin "2") (pinfunction "2_2") (pintype "passive"))
      (node (ref "C22") (pin "2") (pinfunction "2_2") (pintype "passive"))
      (node (ref "C23") (pin "2") (pinfunction "2_2") (pintype "passive"))
      (node (ref "C24") (pin "2") (pinfunction "2_2") (pintype "passive"))
      (node (ref "C25") (pin "2") (pinfunction "2_2") (pintype "passive"))
      (node (ref "C3") (pin "2") (pinfunction "2_2") (pintype "passive"))
      (node (ref "C4") (pin "2") (pinfunction "2_2") (pintype "passive"))
      (node (ref "C5") (pin "2") (pinfunction "2_2") (pintype "passive"))
      (node (ref "C6") (pin "2") (pinfunction "2_2") (pintype "passive"))
      (node (ref "C7") (pin "2") (pinfunction "2_2") (pintype "passive"))
      (node (ref "C8") (pin "2") (pinfunction "2_2") (pintype "passive"))
      (node (ref "C9") (pin "2") (pinfunction "2_2") (pintype "passive"))
      (node (ref "ISO1") (pin "2") (pinfunction "GND1_2") (pintype "bidirectional"))
      (node (ref "ISO1") (pin "8") (pinfunction "GND1_8") (pintype "bidirectional"))
      (node (ref "ISO10") (pin "15") (pinfunction "GND2_15") (pintype "bidirectional"))
      (node (ref "ISO10") (pin "9") (pinfunction "GND2_9") (pintype "bidirectional"))
      (node (ref "ISO11") (pin "2") (pinfunction "GND1_2") (pintype "bidirectional"))
      (node (ref "ISO11") (pin "8") (pinfunction "GND1_8") (pintype "bidirectional"))
      (node (ref "ISO2") (pin "2") (pinfunction "GND1_2") (pintype "bidirectional"))
      (node (ref "ISO2") (pin "8") (pinfunction "GND1_8") (pintype "bidirectional"))
      (node (ref "ISO3") (pin "2") (pinfunction "GND1_2") (pintype "bidirectional"))
      (node (ref "ISO3") (pin "8") (pinfunction "GND1_8") (pintype "bidirectional"))
      (node (ref "ISO4") (pin "2") (pinfunction "GND1_2") (pintype "bidirectional"))
      (node (ref "ISO4") (pin "8") (pinfunction "GND1_8") (pintype "bidirectional"))
      (node (ref "ISO5") (pin "2") (pinfunction "GND1_2") (pintype "bidirectional"))
      (node (ref "ISO5") (pin "8") (pinfunction "GND1_8") (pintype "bidirectional"))
      (node (ref "ISO6") (pin "2") (pinfunction "GND1_2") (pintype "bidirectional"))
      (node (ref "ISO6") (pin "8") (pinfunction "GND1_8") (pintype "bidirectional"))
      (node (ref "ISO7") (pin "2") (pinfunction "GND1_2") (pintype "bidirectional"))
      (node (ref "ISO7") (pin "8") (pinfunction "GND1_8") (pintype "bidirectional"))
      (node (ref "ISO8") (pin "2") (pinfunction "GND1_2") (pintype "bidirectional"))
      (node (ref "ISO8") (pin "8") (pinfunction "GND1_8") (pintype "bidirectional"))
      (node (ref "ISO9") (pin "15") (pinfunction "GND2_15") (pintype "bidirectional"))
      (node (ref "ISO9") (pin "9") (pinfunction "GND2_9") (pintype "bidirectional"))
      (node (ref "J1") (pin "C11") (pinfunction "C11_C11") (pintype "passive"))
      (node (ref "J1") (pin "C14") (pinfunction "C14_C14") (pintype "passive"))
      (node (ref "J1") (pin "C17") (pinfunction "C17_C17") (pintype "passive"))
      (node (ref "J1") (pin "C2") (pinfunction "C2_C2") (pintype "passive"))
      (node (ref "J1") (pin "C20") (pinfunction "C20_C20") (pintype "passive"))
      (node (ref "J1") (pin "C23") (pinfunction "C23_C23") (pintype "passive"))
      (node (ref "J1") (pin "C25") (pinfunction "C25_C25") (pintype "passive"))
      (node (ref "J1") (pin "C5") (pinfunction "C5_C5") (pintype "passive"))
      (node (ref "J1") (pin "C8") (pinfunction "C8_C8") (pintype "passive"))
      (node (ref "J1") (pin "D1") (pinfunction "D1_D1") (pintype "passive"))
      (node (ref "J1") (pin "D10") (pinfunction "D10_D10") (pintype "passive"))
      (node (ref "J1") (pin "D12") (pinfunction "D12_D12") (pintype "passive"))
      (node (ref "J1") (pin "D13") (pinfunction "D13_D13") (pintype "passive"))
      (node (ref "J1") (pin "D15") (pinfunction "D15_D15") (pintype "passive"))
      (node (ref "J1") (pin "D16") (pinfunction "D16_D16") (pintype "passive"))
      (node (ref "J1") (pin "D18") (pinfunction "D18_D18") (pintype "passive"))
      (node (ref "J1") (pin "D19") (pinfunction "D19_D19") (pintype "passive"))
      (node (ref "J1") (pin "D21") (pinfunction "D21_D21") (pintype "passive"))
      (node (ref "J1") (pin "D22") (pinfunction "D22_D22") (pintype "passive"))
      (node (ref "J1") (pin "D24") (pinfunction "D24_D24") (pintype "passive"))
      (node (ref "J1") (pin "D25") (pinfunction "D25_D25") (pintype "passive"))
      (node (ref "J1") (pin "D3") (pinfunction "D3_D3") (pintype "passive"))
      (node (ref "J1") (pin "D4") (pinfunction "D4_D4") (pintype "passive"))
      (node (ref "J1") (pin "D6") (pinfunction "D6_D6") (pintype "passive"))
      (node (ref "J1") (pin "D7") (pinfunction "D7_D7") (pintype "passive"))
      (node (ref "J1") (pin "D9") (pinfunction "D9_D9") (pintype "passive"))
      (node (ref "J1") (pin "E11") (pinfunction "E11_E11") (pintype "passive"))
      (node (ref "J1") (pin "E14") (pinfunction "E14_E14") (pintype "passive"))
      (node (ref "J1") (pin "E17") (pinfunction "E17_E17") (pintype "passive"))
      (node (ref "J1") (pin "E2") (pinfunction "E2_E2") (pintype "passive"))
      (node (ref "J1") (pin "E20") (pinfunction "E20_E20") (pintype "passive"))
      (node (ref "J1") (pin "E23") (pinfunction "E23_E23") (pintype "passive"))
      (node (ref "J1") (pin "E25") (pinfunction "E25_E25") (pintype "passive"))
      (node (ref "J1") (pin "E5") (pinfunction "E5_E5") (pintype "passive"))
      (node (ref "J1") (pin "E8") (pinfunction "E8_E8") (pintype "passive"))
      (node (ref "R1") (pin "1") (pinfunction "1_1") (pintype "passive"))
      (node (ref "R2") (pin "1") (pinfunction "1_1") (pintype "passive"))
      (node (ref "R3") (pin "1") (pinfunction "1_1") (pintype "passive"))
      (node (ref "R7") (pin "1") (pinfunction "1_1") (pintype "passive"))
      (node (ref "U1") (pin "13") (pinfunction "GND_13") (pintype "bidirectional"))
      (node (ref "U1") (pin "15") (pinfunction "ERC_15") (pintype "bidirectional"))
      (node (ref "U1") (pin "17") (pinfunction "GND_17") (pintype "bidirectional"))
      (node (ref "U1") (pin "4") (pinfunction "GND_4") (pintype "bidirectional"))
      (node (ref "U1") (pin "8") (pinfunction "GND_8") (pintype "bidirectional"))
      (node (ref "U2") (pin "11") (pinfunction "GND_11") (pintype "bidirectional"))
      (node (ref "U2") (pin "18") (pinfunction "GND_18") (pintype "bidirectional"))
      (node (ref "U2") (pin "25") (pinfunction "GND_25") (pintype "bidirectional"))
      (node (ref "U2") (pin "27") (pinfunction "~{OEBA}_27") (pintype "bidirectional"))
      (node (ref "U2") (pin "28") (pinfunction "LEBA_28") (pintype "bidirectional"))
      (node (ref "U2") (pin "29") (pinfunction "~{CEBA}_29") (pintype "bidirectional"))
      (node (ref "U2") (pin "32") (pinfunction "GND_32") (pintype "bidirectional"))
      (node (ref "U2") (pin "39") (pinfunction "GND_39") (pintype "bidirectional"))
      (node (ref "U2") (pin "4") (pinfunction "GND_4") (pintype "bidirectional"))
      (node (ref "U2") (pin "46") (pinfunction "GND_46") (pintype "bidirectional"))
      (node (ref "U2") (pin "53") (pinfunction "GND_53") (pintype "bidirectional"))
      (node (ref "U2") (pin "55") (pinfunction "CLKAB_55") (pintype "bidirectional"))
      (node (ref "U2") (pin "56") (pinfunction "~{CEAB}_56") (pintype "bidirectional"))
      (node (ref "U3") (pin "11") (pinfunction "GND_11") (pintype "bidirectional"))
      (node (ref "U3") (pin "18") (pinfunction "GND_18") (pintype "bidirectional"))
      (node (ref "U3") (pin "25") (pinfunction "GND_25") (pintype "bidirectional"))
      (node (ref "U3") (pin "27") (pinfunction "~{OEBA}_27") (pintype "bidirectional"))
      (node (ref "U3") (pin "28") (pinfunction "LEBA_28") (pintype "bidirectional"))
      (node (ref "U3") (pin "29") (pinfunction "~{CEBA}_29") (pintype "bidirectional"))
      (node (ref "U3") (pin "32") (pinfunction "GND_32") (pintype "bidirectional"))
      (node (ref "U3") (pin "39") (pinfunction "GND_39") (pintype "bidirectional"))
      (node (ref "U3") (pin "4") (pinfunction "GND_4") (pintype "bidirectional"))
      (node (ref "U3") (pin "46") (pinfunction "GND_46") (pintype "bidirectional"))
      (node (ref "U3") (pin "53") (pinfunction "GND_53") (pintype "bidirectional"))
      (node (ref "U3") (pin "55") (pinfunction "CLKAB_55") (pintype "bidirectional"))
      (node (ref "U3") (pin "56") (pinfunction "~{CEAB}_56") (pintype "bidirectional"))
      (node (ref "U40") (pin "10") (pinfunction "GND_10") (pintype "bidirectional"))
      (node (ref "U40") (pin "12") (pinfunction "GND_12") (pintype "bidirectional"))
      (node (ref "U40") (pin "18") (pinfunction "GND_18") (pintype "bidirectional"))
      (node (ref "U40") (pin "2") (pinfunction "1~{OEBA}_2") (pintype "bidirectional"))
      (node (ref "U40") (pin "21") (pinfunction "GND_21") (pintype "bidirectional"))
      (node (ref "U40") (pin "24") (pinfunction "GND_24") (pintype "bidirectional"))
      (node (ref "U40") (pin "26") (pinfunction "GND_26") (pintype "bidirectional"))
      (node (ref "U40") (pin "30") (pinfunction "GND_30") (pintype "bidirectional"))
      (node (ref "U40") (pin "33") (pinfunction "~{OE}_33") (pintype "bidirectional"))
      (node (ref "U40") (pin "34") (pinfunction "2LEBA_34") (pintype "bidirectional"))
      (node (ref "U40") (pin "39") (pinfunction "GND_39") (pintype "bidirectional"))
      (node (ref "U40") (pin "44") (pinfunction "GND_44") (pintype "bidirectional"))
      (node (ref "U40") (pin "47") (pinfunction "GND_47") (pintype "bidirectional"))
      (node (ref "U40") (pin "5") (pinfunction "GND_5") (pintype "bidirectional"))
      (node (ref "U40") (pin "53") (pinfunction "GND_53") (pintype "bidirectional"))
      (node (ref "U40") (pin "57") (pinfunction "GND_57") (pintype "bidirectional"))
      (node (ref "U40") (pin "60") (pinfunction "GND_60") (pintype "bidirectional"))
      (node (ref "U40") (pin "61") (pinfunction "ERC_61") (pintype "bidirectional"))
      (node (ref "U40") (pin "63") (pinfunction "1LEAB_63") (pintype "bidirectional"))
      (node (ref "U40") (pin "64") (pinfunction "CLK_64") (pintype "bidirectional"))
      (node (ref "U40") (pin "8") (pinfunction "GND_8") (pintype "bidirectional"))
    )
    (net (code "84") (name "DI0") (class "Default")
      (node (ref "J1") (pin "E1") (pinfunction "E1_E1") (pintype "passive"))
      (node (ref "U2") (pin "54") (pinfunction "B1_54") (pintype "bidirectional"))
    )
    (net (code "85") (name "DI1") (class "Default")
      (node (ref "J1") (pin "D2") (pinfunction "D2_D2") (pintype "passive"))
      (node (ref "U2") (pin "52") (pinfunction "B2_52") (pintype "bidirectional"))
    )
    (net (code "86") (name "DI2") (class "Default")
      (node (ref "J1") (pin "E3") (pinfunction "E3_E3") (pintype "passive"))
      (node (ref "U2") (pin "51") (pinfunction "B3_51") (pintype "bidirectional"))
    )
    (net (code "87") (name "DI3") (class "Default")
      (node (ref "J1") (pin "C3") (pinfunction "C3_C3") (pintype "passive"))
      (node (ref "U2") (pin "49") (pinfunction "B4_49") (pintype "bidirectional"))
    )
    (net (code "88") (name "DI4") (class "Default")
      (node (ref "J1") (pin "E4") (pinfunction "E4_E4") (pintype "passive"))
      (node (ref "U2") (pin "48") (pinfunction "B5_48") (pintype "bidirectional"))
    )
    (net (code "89") (name "DI5") (class "Default")
      (node (ref "J1") (pin "C4") (pinfunction "C4_C4") (pintype "passive"))
      (node (ref "U2") (pin "47") (pinfunction "B6_47") (pintype "bidirectional"))
    )
    (net (code "90") (name "DI6") (class "Default")
      (node (ref "J1") (pin "D5") (pinfunction "D5_D5") (pintype "passive"))
      (node (ref "U2") (pin "45") (pinfunction "B7_45") (pintype "bidirectional"))
    )
    (net (code "91") (name "DI7") (class "Default")
      (node (ref "J1") (pin "E6") (pinfunction "E6_E6") (pintype "passive"))
      (node (ref "U2") (pin "44") (pinfunction "B8_44") (pintype "bidirectional"))
    )
    (net (code "92") (name "DI8") (class "Default")
      (node (ref "J1") (pin "C6") (pinfunction "C6_C6") (pintype "passive"))
      (node (ref "U2") (pin "43") (pinfunction "B9_43") (pintype "bidirectional"))
    )
    (net (code "93") (name "DI9") (class "Default")
      (node (ref "J1") (pin "E7") (pinfunction "E7_E7") (pintype "passive"))
      (node (ref "U2") (pin "42") (pinfunction "B10_42") (pintype "bidirectional"))
    )
    (net (code "94") (name "DI10") (class "Default")
      (node (ref "J1") (pin "C7") (pinfunction "C7_C7") (pintype "passive"))
      (node (ref "U2") (pin "41") (pinfunction "B11_41") (pintype "bidirectional"))
    )
    (net (code "95") (name "DI11") (class "Default")
      (node (ref "J1") (pin "D8") (pinfunction "D8_D8") (pintype "passive"))
      (node (ref "U2") (pin "40") (pinfunction "B12_40") (pintype "bidirectional"))
    )
    (net (code "96") (name "DI12") (class "Default")
      (node (ref "J1") (pin "E9") (pinfunction "E9_E9") (pintype "passive"))
      (node (ref "U2") (pin "38") (pinfunction "B13_38") (pintype "bidirectional"))
    )
    (net (code "97") (name "DI13") (class "Default")
      (node (ref "J1") (pin "C9") (pinfunction "C9_C9") (pintype "passive"))
      (node (ref "U2") (pin "37") (pinfunction "B14_37") (pintype "bidirectional"))
    )
    (net (code "98") (name "DI14") (class "Default")
      (node (ref "J1") (pin "E10") (pinfunction "E10_E10") (pintype "passive"))
      (node (ref "U2") (pin "36") (pinfunction "B15_36") (pintype "bidirectional"))
    )
    (net (code "99") (name "DI15") (class "Default")
      (node (ref "J1") (pin "C10") (pinfunction "C10_C10") (pintype "passive"))
      (node (ref "U2") (pin "34") (pinfunction "B16_34") (pintype "bidirectional"))
    )
    (net (code "100") (name "DI16") (class "Default")
      (node (ref "J1") (pin "D11") (pinfunction "D11_D11") (pintype "passive"))
      (node (ref "U2") (pin "33") (pinfunction "B17_33") (pintype "bidirectional"))
    )
    (net (code "101") (name "DI17") (class "Default")
      (node (ref "J1") (pin "E12") (pinfunction "E12_E12") (pintype "passive"))
      (node (ref "U2") (pin "31") (pinfunction "B18_31") (pintype "bidirectional"))
    )
    (net (code "102") (name "DI18") (class "Default")
      (node (ref "J1") (pin "C12") (pinfunction "C12_C12") (pintype "passive"))
      (node (ref "U3") (pin "54") (pinfunction "B1_54") (pintype "bidirectional"))
    )
    (net (code "103") (name "DI19") (class "Default")
      (node (ref "J1") (pin "E13") (pinfunction "E13_E13") (pintype "passive"))
      (node (ref "U3") (pin "52") (pinfunction "B2_52") (pintype "bidirectional"))
    )
    (net (code "104") (name "DI20") (class "Default")
      (node (ref "J1") (pin "C13") (pinfunction "C13_C13") (pintype "passive"))
      (node (ref "U3") (pin "51") (pinfunction "B3_51") (pintype "bidirectional"))
    )
    (net (code "105") (name "DI21") (class "Default")
      (node (ref "J1") (pin "D14") (pinfunction "D14_D14") (pintype "passive"))
      (node (ref "U3") (pin "49") (pinfunction "B4_49") (pintype "bidirectional"))
    )
    (net (code "106") (name "DI22") (class "Default")
      (node (ref "J1") (pin "E15") (pinfunction "E15_E15") (pintype "passive"))
      (node (ref "U3") (pin "48") (pinfunction "B5_48") (pintype "bidirectional"))
    )
    (net (code "107") (name "DI23") (class "Default")
      (node (ref "J1") (pin "C15") (pinfunction "C15_C15") (pintype "passive"))
      (node (ref "U3") (pin "47") (pinfunction "B6_47") (pintype "bidirectional"))
    )
    (net (code "108") (name "DI24") (class "Default")
      (node (ref "J1") (pin "E16") (pinfunction "E16_E16") (pintype "passive"))
      (node (ref "U3") (pin "45") (pinfunction "B7_45") (pintype "bidirectional"))
    )
    (net (code "109") (name "DI25") (class "Default")
      (node (ref "J1") (pin "C16") (pinfunction "C16_C16") (pintype "passive"))
      (node (ref "U3") (pin "44") (pinfunction "B8_44") (pintype "bidirectional"))
    )
    (net (code "110") (name "DI26") (class "Default")
      (node (ref "J1") (pin "D17") (pinfunction "D17_D17") (pintype "passive"))
      (node (ref "U3") (pin "43") (pinfunction "B9_43") (pintype "bidirectional"))
    )
    (net (code "111") (name "DI27") (class "Default")
      (node (ref "J1") (pin "E18") (pinfunction "E18_E18") (pintype "passive"))
      (node (ref "U3") (pin "42") (pinfunction "B10_42") (pintype "bidirectional"))
    )
    (net (code "112") (name "DI28") (class "Default")
      (node (ref "J1") (pin "C18") (pinfunction "C18_C18") (pintype "passive"))
      (node (ref "U3") (pin "41") (pinfunction "B11_41") (pintype "bidirectional"))
    )
    (net (code "113") (name "DI29") (class "Default")
      (node (ref "J1") (pin "E19") (pinfunction "E19_E19") (pintype "passive"))
      (node (ref "U3") (pin "40") (pinfunction "B12_40") (pintype "bidirectional"))
    )
    (net (code "114") (name "DI30") (class "Default")
      (node (ref "J1") (pin "C19") (pinfunction "C19_C19") (pintype "passive"))
      (node (ref "U3") (pin "38") (pinfunction "B13_38") (pintype "bidirectional"))
    )
    (net (code "115") (name "DI31") (class "Default")
      (node (ref "J1") (pin "D20") (pinfunction "D20_D20") (pintype "passive"))
      (node (ref "U3") (pin "37") (pinfunction "B14_37") (pintype "bidirectional"))
    )
    (net (code "116") (name "DI32") (class "Default")
      (node (ref "J1") (pin "E21") (pinfunction "E21_E21") (pintype "passive"))
      (node (ref "U3") (pin "36") (pinfunction "B15_36") (pintype "bidirectional"))
    )
    (net (code "117") (name "DI33") (class "Default")
      (node (ref "J1") (pin "C21") (pinfunction "C21_C21") (pintype "passive"))
      (node (ref "U3") (pin "34") (pinfunction "B16_34") (pintype "bidirectional"))
    )
    (net (code "118") (name "DI34") (class "Default")
      (node (ref "J1") (pin "E22") (pinfunction "E22_E22") (pintype "passive"))
      (node (ref "U3") (pin "33") (pinfunction "B17_33") (pintype "bidirectional"))
    )
    (net (code "119") (name "DI35") (class "Default")
      (node (ref "J1") (pin "C22") (pinfunction "C22_C22") (pintype "passive"))
      (node (ref "U3") (pin "31") (pinfunction "B18_31") (pintype "bidirectional"))
    )
    (net (code "120") (name "DICS") (class "Default")
      (node (ref "ISO1") (pin "5") (pinfunction "A3_5") (pintype "bidirectional"))
      (node (ref "J1") (pin "A21") (pinfunction "A21_A21") (pintype "passive"))
      (node (ref "R2") (pin "2") (pinfunction "2_2") (pintype "passive"))
      (node (ref "U40") (pin "62") (pinfunction "1LEBA_62") (pintype "bidirectional"))
    )
    (net (code "121") (name "DO0") (class "Default")
      (node (ref "J1") (pin "A4") (pinfunction "A4_A4") (pintype "passive"))
      (node (ref "U40") (pin "37") (pinfunction "2B8_37") (pintype "bidirectional"))
    )
    (net (code "122") (name "DO1") (class "Default")
      (node (ref "J1") (pin "B5") (pinfunction "B5_B5") (pintype "passive"))
      (node (ref "U40") (pin "38") (pinfunction "2B7_38") (pintype "bidirectional"))
    )
    (net (code "123") (name "DO2") (class "Default")
      (node (ref "J1") (pin "A6") (pinfunction "A6_A6") (pintype "passive"))
      (node (ref "U40") (pin "40") (pinfunction "2B6_40") (pintype "bidirectional"))
    )
    (net (code "124") (name "DO3") (class "Default")
      (node (ref "J1") (pin "A7") (pinfunction "A7_A7") (pintype "passive"))
      (node (ref "U40") (pin "42") (pinfunction "2B5_42") (pintype "bidirectional"))
    )
    (net (code "125") (name "DO4") (class "Default")
      (node (ref "J1") (pin "B8") (pinfunction "B8_B8") (pintype "passive"))
      (node (ref "U40") (pin "43") (pinfunction "2B4_43") (pintype "bidirectional"))
    )
    (net (code "126") (name "DO5") (class "Default")
      (node (ref "J1") (pin "A9") (pinfunction "A9_A9") (pintype "passive"))
      (node (ref "U40") (pin "45") (pinfunction "2B3_45") (pintype "bidirectional"))
    )
    (net (code "127") (name "DO6") (class "Default")
      (node (ref "J1") (pin "B11") (pinfunction "B11_B11") (pintype "passive"))
      (node (ref "U40") (pin "46") (pinfunction "2B2_46") (pintype "bidirectional"))
    )
    (net (code "128") (name "DO7") (class "Default")
      (node (ref "J1") (pin "A12") (pinfunction "A12_A12") (pintype "passive"))
      (node (ref "U40") (pin "48") (pinfunction "2B1_48") (pintype "bidirectional"))
    )
    (net (code "129") (name "DOCLKI") (class "Default")
      (node (ref "J1") (pin "C1") (pinfunction "C1_C1") (pintype "passive"))
      (node (ref "U1") (pin "16") (pinfunction "1B_16") (pintype "bidirectional"))
    )
    (net (code "130") (name "DOCLKIB") (class "Default")
      (node (ref "ISO1") (pin "7") (pinfunction "A5_7") (pintype "bidirectional"))
      (node (ref "R3") (pin "2") (pinfunction "2_2") (pintype "passive"))
      (node (ref "U1") (pin "1") (pinfunction "1Y_1") (pintype "bidirectional"))
    )
    (net (code "131") (name "DOCLKO") (class "Default")
      (node (ref "J1") (pin "B2") (pinfunction "B2_B2") (pintype "passive"))
      (node (ref "U1") (pin "14") (pinfunction "2B_14") (pintype "bidirectional"))
    )
    (net (code "132") (name "DOCLKOB") (class "Default")
      (node (ref "ISO10") (pin "11") (pinfunction "B4_11") (pintype "bidirectional"))
      (node (ref "U1") (pin "9") (pinfunction "2A_9") (pintype "bidirectional"))
    )
    (net (code "133") (name "DOCS") (class "Default")
      (node (ref "ISO1") (pin "6") (pinfunction "A4_6") (pintype "bidirectional"))
      (node (ref "J1") (pin "A3") (pinfunction "A3_A3") (pintype "passive"))
      (node (ref "R1") (pin "2") (pinfunction "2_2") (pintype "passive"))
      (node (ref "U1") (pin "10") (pinfunction "2~{OEAB}_10") (pintype "bidirectional"))
      (node (ref "U1") (pin "20") (pinfunction "1~{OEBY}_20") (pintype "bidirectional"))
      (node (ref "U40") (pin "31") (pinfunction "2~{OEAB}_31") (pintype "bidirectional"))
    )
    (net (code "134") (name "DPWR") (class "Default")
      (node (ref "C110") (pin "2") (pinfunction "2_2") (pintype "passive"))
      (node (ref "C122") (pin "2") (pinfunction "2_2") (pintype "passive"))
      (node (ref "C134") (pin "2") (pinfunction "2_2") (pintype "passive"))
      (node (ref "C146") (pin "2") (pinfunction "2_2") (pintype "passive"))
      (node (ref "C158") (pin "2") (pinfunction "2_2") (pintype "passive"))
      (node (ref "C192") (pin "1") (pinfunction "1_1") (pintype "passive"))
      (node (ref "C194") (pin "1") (pinfunction "1_1") (pintype "passive"))
      (node (ref "C195") (pin "1") (pinfunction "1_1") (pintype "passive"))
      (node (ref "C196") (pin "1") (pinfunction "1_1") (pintype "passive"))
      (node (ref "C197") (pin "1") (pinfunction "1_1") (pintype "passive"))
      (node (ref "C198") (pin "1") (pinfunction "1_1") (pintype "passive"))
      (node (ref "C199") (pin "1") (pinfunction "1_1") (pintype "passive"))
      (node (ref "C200") (pin "1") (pinfunction "1_1") (pintype "passive"))
      (node (ref "C201") (pin "1") (pinfunction "1_1") (pintype "passive"))
      (node (ref "C26") (pin "2") (pinfunction "2_2") (pintype "passive"))
      (node (ref "C38") (pin "2") (pinfunction "2_2") (pintype "passive"))
      (node (ref "C50") (pin "2") (pinfunction "2_2") (pintype "passive"))
      (node (ref "C62") (pin "2") (pinfunction "2_2") (pintype "passive"))
      (node (ref "C74") (pin "2") (pinfunction "2_2") (pintype "passive"))
      (node (ref "C86") (pin "2") (pinfunction "2_2") (pintype "passive"))
      (node (ref "C98") (pin "2") (pinfunction "2_2") (pintype "passive"))
      (node (ref "ISO1") (pin "16") (pinfunction "VDD2_16") (pintype "bidirectional"))
      (node (ref "ISO11") (pin "16") (pinfunction "VDD2_16") (pintype "bidirectional"))
      (node (ref "ISO2") (pin "16") (pinfunction "VDD2_16") (pintype "bidirectional"))
      (node (ref "ISO3") (pin "16") (pinfunction "VDD2_16") (pintype "bidirectional"))
      (node (ref "ISO4") (pin "16") (pinfunction "VDD2_16") (pintype "bidirectional"))
      (node (ref "ISO5") (pin "16") (pinfunction "VDD2_16") (pintype "bidirectional"))
      (node (ref "ISO6") (pin "16") (pinfunction "VDD2_16") (pintype "bidirectional"))
      (node (ref "ISO7") (pin "16") (pinfunction "VDD2_16") (pintype "bidirectional"))
      (node (ref "ISO8") (pin "16") (pinfunction "VDD2_16") (pintype "bidirectional"))
      (node (ref "U10") (pin "10") (pinfunction "IOVCC_10") (pintype "power_in"))
      (node (ref "U10") (pin "6") (pinfunction "~{RESET}_6") (pintype "input"))
      (node (ref "U10") (pin "7") (pinfunction "~{CLR}_7") (pintype "input"))
      (node (ref "U10") (pin "9") (pinfunction "VCC_9") (pintype "power_in"))
      (node (ref "U12") (pin "10") (pinfunction "IOVCC_10") (pintype "power_in"))
      (node (ref "U12") (pin "6") (pinfunction "~{RESET}_6") (pintype "input"))
      (node (ref "U12") (pin "7") (pinfunction "~{CLR}_7") (pintype "input"))
      (node (ref "U12") (pin "9") (pinfunction "VCC_9") (pintype "power_in"))
      (node (ref "U14") (pin "10") (pinfunction "IOVCC_10") (pintype "power_in"))
      (node (ref "U14") (pin "6") (pinfunction "~{RESET}_6") (pintype "input"))
      (node (ref "U14") (pin "7") (pinfunction "~{CLR}_7") (pintype "input"))
      (node (ref "U14") (pin "9") (pinfunction "VCC_9") (pintype "power_in"))
      (node (ref "U16") (pin "10") (pinfunction "IOVCC_10") (pintype "power_in"))
      (node (ref "U16") (pin "6") (pinfunction "~{RESET}_6") (pintype "input"))
      (node (ref "U16") (pin "7") (pinfunction "~{CLR}_7") (pintype "input"))
      (node (ref "U16") (pin "9") (pinfunction "VCC_9") (pintype "power_in"))
      (node (ref "U18") (pin "10") (pinfunction "IOVCC_10") (pintype "power_in"))
      (node (ref "U18") (pin "6") (pinfunction "~{RESET}_6") (pintype "input"))
      (node (ref "U18") (pin "7") (pinfunction "~{CLR}_7") (pintype "input"))
      (node (ref "U18") (pin "9") (pinfunction "VCC_9") (pintype "power_in"))
      (node (ref "U20") (pin "10") (pinfunction "IOVCC_10") (pintype "power_in"))
      (node (ref "U20") (pin "6") (pinfunction "~{RESET}_6") (pintype "input"))
      (node (ref "U20") (pin "7") (pinfunction "~{CLR}_7") (pintype "input"))
      (node (ref "U20") (pin "9") (pinfunction "VCC_9") (pintype "power_in"))
      (node (ref "U22") (pin "10") (pinfunction "IOVCC_10") (pintype "power_in"))
      (node (ref "U22") (pin "6") (pinfunction "~{RESET}_6") (pintype "input"))
      (node (ref "U22") (pin "7") (pinfunction "~{CLR}_7") (pintype "input"))
      (node (ref "U22") (pin "9") (pinfunction "VCC_9") (pintype "power_in"))
      (node (ref "U24") (pin "10") (pinfunction "IOVCC_10") (pintype "power_in"))
      (node (ref "U24") (pin "6") (pinfunction "~{RESET}_6") (pintype "input"))
      (node (ref "U24") (pin "7") (pinfunction "~{CLR}_7") (pintype "input"))
      (node (ref "U24") (pin "9") (pinfunction "VCC_9") (pintype "power_in"))
      (node (ref "U26") (pin "10") (pinfunction "IOVCC_10") (pintype "power_in"))
      (node (ref "U26") (pin "6") (pinfunction "~{RESET}_6") (pintype "input"))
      (node (ref "U26") (pin "7") (pinfunction "~{CLR}_7") (pintype "input"))
      (node (ref "U26") (pin "9") (pinfunction "VCC_9") (pintype "power_in"))
      (node (ref "U29") (pin "2") (pinfunction "OUT_2_2") (pintype "output"))
      (node (ref "U29") (pin "4") (pinfunction "OUT_4") (pintype "output"))
      (node (ref "U4") (pin "10") (pinfunction "IOVCC_10") (pintype "power_in"))
      (node (ref "U4") (pin "6") (pinfunction "~{RESET}_6") (pintype "input"))
      (node (ref "U4") (pin "7") (pinfunction "~{CLR}_7") (pintype "input"))
      (node (ref "U4") (pin "9") (pinfunction "VCC_9") (pintype "power_in"))
      (node (ref "U6") (pin "10") (pinfunction "IOVCC_10") (pintype "power_in"))
      (node (ref "U6") (pin "6") (pinfunction "~{RESET}_6") (pintype "input"))
      (node (ref "U6") (pin "7") (pinfunction "~{CLR}_7") (pintype "input"))
      (node (ref "U6") (pin "9") (pinfunction "VCC_9") (pintype "power_in"))
      (node (ref "U8") (pin "10") (pinfunction "IOVCC_10") (pintype "power_in"))
      (node (ref "U8") (pin "6") (pinfunction "~{RESET}_6") (pintype "input"))
      (node (ref "U8") (pin "7") (pinfunction "~{CLR}_7") (pintype "input"))
      (node (ref "U8") (pin "9") (pinfunction "VCC_9") (pintype "power_in"))
    )
    (net (code "135") (name "DSCLK0") (class "Default")
      (node (ref "J1") (pin "B14") (pinfunction "B14_B14") (pintype "passive"))
      (node (ref "U40") (pin "51") (pinfunction "1B7_51") (pintype "bidirectional"))
    )
    (net (code "136") (name "DSCLK0B") (class "Default")
      (node (ref "U2") (pin "30") (pinfunction "CLKBA_30") (pintype "bidirectional"))
      (node (ref "U40") (pin "14") (pinfunction "1A7_14") (pintype "bidirectional"))
    )
    (net (code "137") (name "DSCLK1") (class "Default")
      (node (ref "J1") (pin "B20") (pinfunction "B20_B20") (pintype "passive"))
      (node (ref "U40") (pin "59") (pinfunction "1B1_59") (pintype "bidirectional"))
    )
    (net (code "138") (name "DSCLK1B") (class "Default")
      (node (ref "U3") (pin "30") (pinfunction "CLKBA_30") (pintype "bidirectional"))
      (node (ref "U40") (pin "4") (pinfunction "1A1_4") (pintype "bidirectional"))
    )
    (net (code "139") (name "DVCC") (class "Default")
      (node (ref "C1") (pin "1") (pinfunction "1_1") (pintype "passive"))
      (node (ref "C10") (pin "1") (pinfunction "1_1") (pintype "passive"))
      (node (ref "C13") (pin "1") (pinfunction "1_1") (pintype "passive"))
      (node (ref "C14") (pin "1") (pinfunction "1_1") (pintype "passive"))
      (node (ref "C15") (pin "1") (pinfunction "1_1") (pintype "passive"))
      (node (ref "C16") (pin "1") (pinfunction "1_1") (pintype "passive"))
      (node (ref "C17") (pin "1") (pinfunction "1_1") (pintype "passive"))
      (node (ref "C18") (pin "1") (pinfunction "1_1") (pintype "passive"))
      (node (ref "C19") (pin "1") (pinfunction "1_1") (pintype "passive"))
      (node (ref "C2") (pin "1") (pinfunction "1_1") (pintype "passive"))
      (node (ref "C20") (pin "1") (pinfunction "1_1") (pintype "passive"))
      (node (ref "C21") (pin "1") (pinfunction "1_1") (pintype "passive"))
      (node (ref "C22") (pin "1") (pinfunction "1_1") (pintype "passive"))
      (node (ref "C3") (pin "1") (pinfunction "1_1") (pintype "passive"))
      (node (ref "C4") (pin "1") (pinfunction "1_1") (pintype "passive"))
      (node (ref "C5") (pin "1") (pinfunction "1_1") (pintype "passive"))
      (node (ref "C6") (pin "1") (pinfunction "1_1") (pintype "passive"))
      (node (ref "C7") (pin "1") (pinfunction "1_1") (pintype "passive"))
      (node (ref "C8") (pin "1") (pinfunction "1_1") (pintype "passive"))
      (node (ref "C9") (pin "1") (pinfunction "1_1") (pintype "passive"))
      (node (ref "ISO1") (pin "1") (pinfunction "VDD1_1") (pintype "bidirectional"))
      (node (ref "ISO10") (pin "16") (pinfunction "VDD2_16") (pintype "bidirectional"))
      (node (ref "ISO11") (pin "1") (pinfunction "VDD1_1") (pintype "bidirectional"))
      (node (ref "ISO2") (pin "1") (pinfunction "VDD1_1") (pintype "bidirectional"))
      (node (ref "ISO3") (pin "1") (pinfunction "VDD1_1") (pintype "bidirectional"))
      (node (ref "ISO4") (pin "1") (pinfunction "VDD1_1") (pintype "bidirectional"))
      (node (ref "ISO5") (pin "1") (pinfunction "VDD1_1") (pintype "bidirectional"))
      (node (ref "ISO6") (pin "1") (pinfunction "VDD1_1") (pintype "bidirectional"))
      (node (ref "ISO7") (pin "1") (pinfunction "VDD1_1") (pintype "bidirectional"))
      (node (ref "ISO8") (pin "1") (pinfunction "VDD1_1") (pintype "bidirectional"))
      (node (ref "ISO9") (pin "16") (pinfunction "VDD2_16") (pintype "bidirectional"))
      (node (ref "J1") (pin "A11") (pinfunction "A11_A11") (pintype "passive"))
      (node (ref "J1") (pin "A14") (pinfunction "A14_A14") (pintype "passive"))
      (node (ref "J1") (pin "A17") (pinfunction "A17_A17") (pintype "passive"))
      (node (ref "J1") (pin "A2") (pinfunction "A2_A2") (pintype "passive"))
      (node (ref "J1") (pin "A20") (pinfunction "A20_A20") (pintype "passive"))
      (node (ref "J1") (pin "A22") (pinfunction "A22_A22") (pintype "passive"))
      (node (ref "J1") (pin "A23") (pinfunction "A23_A23") (pintype "passive"))
      (node (ref "J1") (pin "A25") (pinfunction "A25_A25") (pintype "passive"))
      (node (ref "J1") (pin "A5") (pinfunction "A5_A5") (pintype "passive"))
      (node (ref "J1") (pin "A8") (pinfunction "A8_A8") (pintype "passive"))
      (node (ref "J1") (pin "B1") (pinfunction "B1_B1") (pintype "passive"))
      (node (ref "J1") (pin "B12") (pinfunction "B12_B12") (pintype "passive"))
      (node (ref "J1") (pin "B13") (pinfunction "B13_B13") (pintype "passive"))
      (node (ref "J1") (pin "B15") (pinfunction "B15_B15") (pintype "passive"))
      (node (ref "J1") (pin "B16") (pinfunction "B16_B16") (pintype "passive"))
      (node (ref "J1") (pin "B18") (pinfunction "B18_B18") (pintype "passive"))
      (node (ref "J1") (pin "B19") (pinfunction "B19_B19") (pintype "passive"))
      (node (ref "J1") (pin "B21") (pinfunction "B21_B21") (pintype "passive"))
      (node (ref "J1") (pin "B22") (pinfunction "B22_B22") (pintype "passive"))
      (node (ref "J1") (pin "B24") (pinfunction "B24_B24") (pintype "passive"))
      (node (ref "J1") (pin "B25") (pinfunction "B25_B25") (pintype "passive"))
      (node (ref "J1") (pin "B3") (pinfunction "B3_B3") (pintype "passive"))
      (node (ref "J1") (pin "B4") (pinfunction "B4_B4") (pintype "passive"))
      (node (ref "J1") (pin "B6") (pinfunction "B6_B6") (pintype "passive"))
      (node (ref "J1") (pin "B7") (pinfunction "B7_B7") (pintype "passive"))
      (node (ref "J1") (pin "B9") (pinfunction "B9_B9") (pintype "passive"))
      (node (ref "U1") (pin "11") (pinfunction "BIAS_VCC_11") (pintype "bidirectional"))
      (node (ref "U1") (pin "18") (pinfunction "2~{OEBY}_18") (pintype "bidirectional"))
      (node (ref "U1") (pin "19") (pinfunction "2T/~{C}_19") (pintype "bidirectional"))
      (node (ref "U1") (pin "2") (pinfunction "1T/~{C}_2") (pintype "bidirectional"))
      (node (ref "U1") (pin "5") (pinfunction "1~{OEAB}_5") (pintype "bidirectional"))
      (node (ref "U1") (pin "6") (pinfunction "VCC_6") (pintype "bidirectional"))
      (node (ref "U1") (pin "7") (pinfunction "1A_7") (pintype "bidirectional"))
      (node (ref "U2") (pin "1") (pinfunction "~{OEAB}_1") (pintype "bidirectional"))
      (node (ref "U2") (pin "2") (pinfunction "LEAB_2") (pintype "bidirectional"))
      (node (ref "U2") (pin "22") (pinfunction "VCC_22") (pintype "bidirectional"))
      (node (ref "U2") (pin "50") (pinfunction "BIAS_VCC_50") (pintype "bidirectional"))
      (node (ref "U2") (pin "7") (pinfunction "VCC_7") (pintype "bidirectional"))
      (node (ref "U3") (pin "1") (pinfunction "~{OEAB}_1") (pintype "bidirectional"))
      (node (ref "U3") (pin "2") (pinfunction "LEAB_2") (pintype "bidirectional"))
      (node (ref "U3") (pin "22") (pinfunction "VCC_22") (pintype "bidirectional"))
      (node (ref "U3") (pin "50") (pinfunction "BIAS_VCC_50") (pintype "bidirectional"))
      (node (ref "U3") (pin "7") (pinfunction "VCC_7") (pintype "bidirectional"))
      (node (ref "U40") (pin "1") (pinfunction "1~{OEAB}_1") (pintype "bidirectional"))
      (node (ref "U40") (pin "15") (pinfunction "VCC_15") (pintype "bidirectional"))
      (node (ref "U40") (pin "28") (pinfunction "VCC_28") (pintype "bidirectional"))
      (node (ref "U40") (pin "3") (pinfunction "VCC_3") (pintype "bidirectional"))
      (node (ref "U40") (pin "32") (pinfunction "2~{OEBA}_32") (pintype "bidirectional"))
      (node (ref "U40") (pin "35") (pinfunction "2LEAB_35") (pintype "bidirectional"))
      (node (ref "U40") (pin "36") (pinfunction "BIAS_VCC_36") (pintype "bidirectional"))
      (node (ref "U40") (pin "50") (pinfunction "VCC_50") (pintype "bidirectional"))
    )
    (net (code "140") (name "DVTT") (class "Default")
      (node (ref "J1") (pin "A10") (pinfunction "A10_A10") (pintype "passive"))
      (node (ref "J1") (pin "B10") (pinfunction "B10_B10") (pintype "passive"))
      (node (ref "R6") (pin "2") (pinfunction "2_2") (pintype "passive"))
    )
    (net (code "141") (name "DX0") (class "Default")
      (node (ref "J1") (pin "A13") (pinfunction "A13_A13") (pintype "passive"))
      (node (ref "U40") (pin "49") (pinfunction "1B8_49") (pintype "bidirectional"))
    )
    (net (code "142") (name "DX1") (class "Default")
      (node (ref "J1") (pin "A15") (pinfunction "A15_A15") (pintype "passive"))
      (node (ref "U40") (pin "52") (pinfunction "1B6_52") (pintype "bidirectional"))
    )
    (net (code "143") (name "DX2") (class "Default")
      (node (ref "J1") (pin "A16") (pinfunction "A16_A16") (pintype "passive"))
      (node (ref "U40") (pin "54") (pinfunction "1B5_54") (pintype "bidirectional"))
    )
    (net (code "144") (name "DX3") (class "Default")
      (node (ref "J1") (pin "B17") (pinfunction "B17_B17") (pintype "passive"))
      (node (ref "U40") (pin "55") (pinfunction "1B4_55") (pintype "bidirectional"))
    )
    (net (code "145") (name "DX4") (class "Default")
      (node (ref "J1") (pin "A18") (pinfunction "A18_A18") (pintype "passive"))
      (node (ref "U40") (pin "56") (pinfunction "1B3_56") (pintype "bidirectional"))
    )
    (net (code "146") (name "DX5") (class "Default")
      (node (ref "J1") (pin "A19") (pinfunction "A19_A19") (pintype "passive"))
      (node (ref "U40") (pin "58") (pinfunction "1B2_58") (pintype "bidirectional"))
    )
    (net (code "147") (name "GND") (class "Default")
      (node (ref "C100") (pin "1") (pinfunction "1_1") (pintype "passive"))
      (node (ref "C101") (pin "2") (pinfunction "2_2") (pintype "passive"))
      (node (ref "C102") (pin "1") (pinfunction "1_1") (pintype "passive"))
      (node (ref "C103") (pin "1") (pinfunction "1_1") (pintype "passive"))
      (node (ref "C104") (pin "1") (pinfunction "1_1") (pintype "passive"))
      (node (ref "C105") (pin "1") (pinfunction "1_1") (pintype "passive"))
      (node (ref "C107") (pin "1") (pinfunction "1_1") (pintype "passive"))
      (node (ref "C108") (pin "1") (pinfunction "1_1") (pintype "passive"))
      (node (ref "C109") (pin "1") (pinfunction "1_1") (pintype "passive"))
      (node (ref "C11") (pin "1") (pinfunction "1_1") (pintype "passive"))
      (node (ref "C110") (pin "1") (pinfunction "1_1") (pintype "passive"))
      (node (ref "C111") (pin "1") (pinfunction "1_1") (pintype "passive"))
      (node (ref "C112") (pin "1") (pinfunction "1_1") (pintype "passive"))
      (node (ref "C113") (pin "2") (pinfunction "2_2") (pintype "passive"))
      (node (ref "C114") (pin "1") (pinfunction "1_1") (pintype "passive"))
      (node (ref "C115") (pin "1") (pinfunction "1_1") (pintype "passive"))
      (node (ref "C116") (pin "1") (pinfunction "1_1") (pintype "passive"))
      (node (ref "C117") (pin "1") (pinfunction "1_1") (pintype "passive"))
      (node (ref "C119") (pin "1") (pinfunction "1_1") (pintype "passive"))
      (node (ref "C12") (pin "1") (pinfunction "1_1") (pintype "passive"))
      (node (ref "C120") (pin "1") (pinfunction "1_1") (pintype "passive"))
      (node (ref "C121") (pin "1") (pinfunction "1_1") (pintype "passive"))
      (node (ref "C122") (pin "1") (pinfunction "1_1") (pintype "passive"))
      (node (ref "C123") (pin "1") (pinfunction "1_1") (pintype "passive"))
      (node (ref "C124") (pin "1") (pinfunction "1_1") (pintype "passive"))
      (node (ref "C125") (pin "2") (pinfunction "2_2") (pintype "passive"))
      (node (ref "C126") (pin "1") (pinfunction "1_1") (pintype "passive"))
      (node (ref "C127") (pin "1") (pinfunction "1_1") (pintype "passive"))
      (node (ref "C128") (pin "1") (pinfunction "1_1") (pintype "passive"))
      (node (ref "C129") (pin "1") (pinfunction "1_1") (pintype "passive"))
      (node (ref "C131") (pin "1") (pinfunction "1_1") (pintype "passive"))
      (node (ref "C132") (pin "1") (pinfunction "1_1") (pintype "passive"))
      (node (ref "C133") (pin "1") (pinfunction "1_1") (pintype "passive"))
      (node (ref "C134") (pin "1") (pinfunction "1_1") (pintype "passive"))
      (node (ref "C135") (pin "1") (pinfunction "1_1") (pintype "passive"))
      (node (ref "C136") (pin "1") (pinfunction "1_1") (pintype "passive"))
      (node (ref "C137") (pin "2") (pinfunction "2_2") (pintype "passive"))
      (node (ref "C138") (pin "1") (pinfunction "1_1") (pintype "passive"))
      (node (ref "C139") (pin "1") (pinfunction "1_1") (pintype "passive"))
      (node (ref "C140") (pin "1") (pinfunction "1_1") (pintype "passive"))
      (node (ref "C141") (pin "1") (pinfunction "1_1") (pintype "passive"))
      (node (ref "C143") (pin "1") (pinfunction "1_1") (pintype "passive"))
      (node (ref "C144") (pin "1") (pinfunction "1_1") (pintype "passive"))
      (node (ref "C145") (pin "1") (pinfunction "1_1") (pintype "passive"))
      (node (ref "C146") (pin "1") (pinfunction "1_1") (pintype "passive"))
      (node (ref "C147") (pin "1") (pinfunction "1_1") (pintype "passive"))
      (node (ref "C148") (pin "1") (pinfunction "1_1") (pintype "passive"))
      (node (ref "C149") (pin "2") (pinfunction "2_2") (pintype "passive"))
      (node (ref "C150") (pin "1") (pinfunction "1_1") (pintype "passive"))
      (node (ref "C151") (pin "1") (pinfunction "1_1") (pintype "passive"))
      (node (ref "C152") (pin "1") (pinfunction "1_1") (pintype "passive"))
      (node (ref "C153") (pin "1") (pinfunction "1_1") (pintype "passive"))
      (node (ref "C155") (pin "1") (pinfunction "1_1") (pintype "passive"))
      (node (ref "C156") (pin "1") (pinfunction "1_1") (pintype "passive"))
      (node (ref "C157") (pin "1") (pinfunction "1_1") (pintype "passive"))
      (node (ref "C158") (pin "1") (pinfunction "1_1") (pintype "passive"))
      (node (ref "C159") (pin "1") (pinfunction "1_1") (pintype "passive"))
      (node (ref "C160") (pin "1") (pinfunction "1_1") (pintype "passive"))
      (node (ref "C161") (pin "2") (pinfunction "2_2") (pintype "passive"))
      (node (ref "C162") (pin "1") (pinfunction "1_1") (pintype "passive"))
      (node (ref "C163") (pin "1") (pinfunction "1_1") (pintype "passive"))
      (node (ref "C164") (pin "1") (pinfunction "1_1") (pintype "passive"))
      (node (ref "C165") (pin "1") (pinfunction "1_1") (pintype "passive"))
      (node (ref "C167") (pin "1") (pinfunction "1_1") (pintype "passive"))
      (node (ref "C168") (pin "2") (pinfunction "2_2") (pintype "passive"))
      (node (ref "C169") (pin "2") (pinfunction "2_2") (pintype "passive"))
      (node (ref "C170") (pin "2") (pinfunction "2_2") (pintype "passive"))
      (node (ref "C171") (pin "2") (pinfunction "2_2") (pintype "passive"))
      (node (ref "C172") (pin "2") (pinfunction "2_2") (pintype "passive"))
      (node (ref "C173") (pin "2") (pinfunction "2_2") (pintype "passive"))
      (node (ref "C174") (pin "2") (pinfunction "2_2") (pintype "passive"))
      (node (ref "C175") (pin "2") (pinfunction "2_2") (pintype "passive"))
      (node (ref "C176") (pin "2") (pinfunction "2_2") (pintype "passive"))
      (node (ref "C177") (pin "2") (pinfunction "2_2") (pintype "passive"))
      (node (ref "C178") (pin "2") (pinfunction "2_2") (pintype "passive"))
      (node (ref "C179") (pin "2") (pinfunction "2_2") (pintype "passive"))
      (node (ref "C180") (pin "2") (pinfunction "2_2") (pintype "passive"))
      (node (ref "C181") (pin "2") (pinfunction "2_2") (pintype "passive"))
      (node (ref "C182") (pin "2") (pinfunction "2_2") (pintype "passive"))
      (node (ref "C183") (pin "2") (pinfunction "2_2") (pintype "passive"))
      (node (ref "C184") (pin "2") (pinfunction "2_2") (pintype "passive"))
      (node (ref "C185") (pin "2") (pinfunction "2_2") (pintype "passive"))
      (node (ref "C186") (pin "2") (pinfunction "2_2") (pintype "passive"))
      (node (ref "C187") (pin "2") (pinfunction "2_2") (pintype "passive"))
      (node (ref "C188") (pin "2") (pinfunction "2_2") (pintype "passive"))
      (node (ref "C189") (pin "2") (pinfunction "2_2") (pintype "passive"))
      (node (ref "C190") (pin "2") (pinfunction "2_2") (pintype "passive"))
      (node (ref "C191") (pin "2") (pinfunction "2_2") (pintype "passive"))
      (node (ref "C192") (pin "2") (pinfunction "2_2") (pintype "passive"))
      (node (ref "C193") (pin "2") (pinfunction "2_2") (pintype "passive"))
      (node (ref "C194") (pin "2") (pinfunction "2_2") (pintype "passive"))
      (node (ref "C195") (pin "2") (pinfunction "2_2") (pintype "passive"))
      (node (ref "C196") (pin "2") (pinfunction "2_2") (pintype "passive"))
      (node (ref "C197") (pin "2") (pinfunction "2_2") (pintype "passive"))
      (node (ref "C198") (pin "2") (pinfunction "2_2") (pintype "passive"))
      (node (ref "C199") (pin "2") (pinfunction "2_2") (pintype "passive"))
      (node (ref "C200") (pin "2") (pinfunction "2_2") (pintype "passive"))
      (node (ref "C201") (pin "2") (pinfunction "2_2") (pintype "passive"))
      (node (ref "C26") (pin "1") (pinfunction "1_1") (pintype "passive"))
      (node (ref "C27") (pin "1") (pinfunction "1_1") (pintype "passive"))
      (node (ref "C28") (pin "1") (pinfunction "1_1") (pintype "passive"))
      (node (ref "C29") (pin "2") (pinfunction "2_2") (pintype "passive"))
      (node (ref "C30") (pin "1") (pinfunction "1_1") (pintype "passive"))
      (node (ref "C31") (pin "1") (pinfunction "1_1") (pintype "passive"))
      (node (ref "C32") (pin "1") (pinfunction "1_1") (pintype "passive"))
      (node (ref "C33") (pin "1") (pinfunction "1_1") (pintype "passive"))
      (node (ref "C35") (pin "1") (pinfunction "1_1") (pintype "passive"))
      (node (ref "C36") (pin "1") (pinfunction "1_1") (pintype "passive"))
      (node (ref "C37") (pin "1") (pinfunction "1_1") (pintype "passive"))
      (node (ref "C38") (pin "1") (pinfunction "1_1") (pintype "passive"))
      (node (ref "C39") (pin "1") (pinfunction "1_1") (pintype "passive"))
      (node (ref "C40") (pin "1") (pinfunction "1_1") (pintype "passive"))
      (node (ref "C41") (pin "2") (pinfunction "2_2") (pintype "passive"))
      (node (ref "C42") (pin "1") (pinfunction "1_1") (pintype "passive"))
      (node (ref "C43") (pin "1") (pinfunction "1_1") (pintype "passive"))
      (node (ref "C44") (pin "1") (pinfunction "1_1") (pintype "passive"))
      (node (ref "C45") (pin "1") (pinfunction "1_1") (pintype "passive"))
      (node (ref "C47") (pin "1") (pinfunction "1_1") (pintype "passive"))
      (node (ref "C48") (pin "1") (pinfunction "1_1") (pintype "passive"))
      (node (ref "C49") (pin "1") (pinfunction "1_1") (pintype "passive"))
      (node (ref "C50") (pin "1") (pinfunction "1_1") (pintype "passive"))
      (node (ref "C51") (pin "1") (pinfunction "1_1") (pintype "passive"))
      (node (ref "C52") (pin "1") (pinfunction "1_1") (pintype "passive"))
      (node (ref "C53") (pin "2") (pinfunction "2_2") (pintype "passive"))
      (node (ref "C54") (pin "1") (pinfunction "1_1") (pintype "passive"))
      (node (ref "C55") (pin "1") (pinfunction "1_1") (pintype "passive"))
      (node (ref "C56") (pin "1") (pinfunction "1_1") (pintype "passive"))
      (node (ref "C57") (pin "1") (pinfunction "1_1") (pintype "passive"))
      (node (ref "C59") (pin "1") (pinfunction "1_1") (pintype "passive"))
      (node (ref "C60") (pin "1") (pinfunction "1_1") (pintype "passive"))
      (node (ref "C61") (pin "1") (pinfunction "1_1") (pintype "passive"))
      (node (ref "C62") (pin "1") (pinfunction "1_1") (pintype "passive"))
      (node (ref "C63") (pin "1") (pinfunction "1_1") (pintype "passive"))
      (node (ref "C64") (pin "1") (pinfunction "1_1") (pintype "passive"))
      (node (ref "C65") (pin "2") (pinfunction "2_2") (pintype "passive"))
      (node (ref "C66") (pin "1") (pinfunction "1_1") (pintype "passive"))
      (node (ref "C67") (pin "1") (pinfunction "1_1") (pintype "passive"))
      (node (ref "C68") (pin "1") (pinfunction "1_1") (pintype "passive"))
      (node (ref "C69") (pin "1") (pinfunction "1_1") (pintype "passive"))
      (node (ref "C71") (pin "1") (pinfunction "1_1") (pintype "passive"))
      (node (ref "C72") (pin "1") (pinfunction "1_1") (pintype "passive"))
      (node (ref "C73") (pin "1") (pinfunction "1_1") (pintype "passive"))
      (node (ref "C74") (pin "1") (pinfunction "1_1") (pintype "passive"))
      (node (ref "C75") (pin "1") (pinfunction "1_1") (pintype "passive"))
      (node (ref "C76") (pin "1") (pinfunction "1_1") (pintype "passive"))
      (node (ref "C77") (pin "2") (pinfunction "2_2") (pintype "passive"))
      (node (ref "C78") (pin "1") (pinfunction "1_1") (pintype "passive"))
      (node (ref "C79") (pin "1") (pinfunction "1_1") (pintype "passive"))
      (node (ref "C80") (pin "1") (pinfunction "1_1") (pintype "passive"))
      (node (ref "C81") (pin "1") (pinfunction "1_1") (pintype "passive"))
      (node (ref "C83") (pin "1") (pinfunction "1_1") (pintype "passive"))
      (node (ref "C84") (pin "1") (pinfunction "1_1") (pintype "passive"))
      (node (ref "C85") (pin "1") (pinfunction "1_1") (pintype "passive"))
      (node (ref "C86") (pin "1") (pinfunction "1_1") (pintype "passive"))
      (node (ref "C87") (pin "1") (pinfunction "1_1") (pintype "passive"))
      (node (ref "C88") (pin "1") (pinfunction "1_1") (pintype "passive"))
      (node (ref "C89") (pin "2") (pinfunction "2_2") (pintype "passive"))
      (node (ref "C90") (pin "1") (pinfunction "1_1") (pintype "passive"))
      (node (ref "C91") (pin "1") (pinfunction "1_1") (pintype "passive"))
      (node (ref "C92") (pin "1") (pinfunction "1_1") (pintype "passive"))
      (node (ref "C93") (pin "1") (pinfunction "1_1") (pintype "passive"))
      (node (ref "C95") (pin "1") (pinfunction "1_1") (pintype "passive"))
      (node (ref "C96") (pin "1") (pinfunction "1_1") (pintype "passive"))
      (node (ref "C97") (pin "1") (pinfunction "1_1") (pintype "passive"))
      (node (ref "C98") (pin "1") (pinfunction "1_1") (pintype "passive"))
      (node (ref "C99") (pin "1") (pinfunction "1_1") (pintype "passive"))
      (node (ref "ISO1") (pin "15") (pinfunction "GND2_15") (pintype "bidirectional"))
      (node (ref "ISO1") (pin "9") (pinfunction "GND2_9") (pintype "bidirectional"))
      (node (ref "ISO11") (pin "15") (pinfunction "GND2_15") (pintype "bidirectional"))
      (node (ref "ISO11") (pin "9") (pinfunction "GND2_9") (pintype "bidirectional"))
      (node (ref "ISO2") (pin "15") (pinfunction "GND2_15") (pintype "bidirectional"))
      (node (ref "ISO2") (pin "9") (pinfunction "GND2_9") (pintype "bidirectional"))
      (node (ref "ISO3") (pin "15") (pinfunction "GND2_15") (pintype "bidirectional"))
      (node (ref "ISO3") (pin "9") (pinfunction "GND2_9") (pintype "bidirectional"))
      (node (ref "ISO4") (pin "15") (pinfunction "GND2_15") (pintype "bidirectional"))
      (node (ref "ISO4") (pin "9") (pinfunction "GND2_9") (pintype "bidirectional"))
      (node (ref "ISO5") (pin "15") (pinfunction "GND2_15") (pintype "bidirectional"))
      (node (ref "ISO5") (pin "9") (pinfunction "GND2_9") (pintype "bidirectional"))
      (node (ref "ISO6") (pin "15") (pinfunction "GND2_15") (pintype "bidirectional"))
      (node (ref "ISO6") (pin "9") (pinfunction "GND2_9") (pintype "bidirectional"))
      (node (ref "ISO7") (pin "15") (pinfunction "GND2_15") (pintype "bidirectional"))
      (node (ref "ISO7") (pin "9") (pinfunction "GND2_9") (pintype "bidirectional"))
      (node (ref "ISO8") (pin "15") (pinfunction "GND2_15") (pintype "bidirectional"))
      (node (ref "ISO8") (pin "9") (pinfunction "GND2_9") (pintype "bidirectional"))
      (node (ref "J1") (pin "A26") (pinfunction "A26_A26") (pintype "passive"))
      (node (ref "J1") (pin "A30") (pinfunction "A30_A30") (pintype "passive"))
      (node (ref "J1") (pin "A31") (pinfunction "A31_A31") (pintype "passive"))
      (node (ref "J1") (pin "A32") (pinfunction "A32_A32") (pintype "passive"))
      (node (ref "J1") (pin "A33") (pinfunction "A33_A33") (pintype "passive"))
      (node (ref "J1") (pin "A38") (pinfunction "A38_A38") (pintype "passive"))
      (node (ref "J1") (pin "A39") (pinfunction "A39_A39") (pintype "passive"))
      (node (ref "J1") (pin "A40") (pinfunction "A40_A40") (pintype "passive"))
      (node (ref "J1") (pin "B26") (pinfunction "B26_B26") (pintype "passive"))
      (node (ref "J1") (pin "B31") (pinfunction "B31_B31") (pintype "passive"))
      (node (ref "J1") (pin "B33") (pinfunction "B33_B33") (pintype "passive"))
      (node (ref "J1") (pin "B38") (pinfunction "B38_B38") (pintype "passive"))
      (node (ref "J1") (pin "B40") (pinfunction "B40_B40") (pintype "passive"))
      (node (ref "J1") (pin "C26") (pinfunction "C26_C26") (pintype "passive"))
      (node (ref "J1") (pin "C31") (pinfunction "C31_C31") (pintype "passive"))
      (node (ref "J1") (pin "C32") (pinfunction "C32_C32") (pintype "passive"))
      (node (ref "J1") (pin "C33") (pinfunction "C33_C33") (pintype "passive"))
      (node (ref "J1") (pin "C34") (pinfunction "C34_C34") (pintype "passive"))
      (node (ref "J1") (pin "C35") (pinfunction "C35_C35") (pintype "passive"))
      (node (ref "J1") (pin "C36") (pinfunction "C36_C36") (pintype "passive"))
      (node (ref "J1") (pin "C37") (pinfunction "C37_C37") (pintype "passive"))
      (node (ref "J1") (pin "C38") (pinfunction "C38_C38") (pintype "passive"))
      (node (ref "J1") (pin "C39") (pinfunction "C39_C39") (pintype "passive"))
      (node (ref "J1") (pin "C40") (pinfunction "C40_C40") (pintype "passive"))
      (node (ref "J1") (pin "C41") (pinfunction "C41_C41") (pintype "passive"))
      (node (ref "J1") (pin "C42") (pinfunction "C42_C42") (pintype "passive"))
      (node (ref "J1") (pin "C43") (pinfunction "C43_C43") (pintype "passive"))
      (node (ref "J1") (pin "C44") (pinfunction "C44_C44") (pintype "passive"))
      (node (ref "J1") (pin "D26") (pinfunction "D26_D26") (pintype "passive"))
      (node (ref "J1") (pin "D31") (pinfunction "D31_D31") (pintype "passive"))
      (node (ref "J1") (pin "D33") (pinfunction "D33_D33") (pintype "passive"))
      (node (ref "J1") (pin "D38") (pinfunction "D38_D38") (pintype "passive"))
      (node (ref "J1") (pin "D40") (pinfunction "D40_D40") (pintype "passive"))
      (node (ref "J1") (pin "E26") (pinfunction "E26_E26") (pintype "passive"))
      (node (ref "J1") (pin "E30") (pinfunction "E30_E30") (pintype "passive"))
      (node (ref "J1") (pin "E31") (pinfunction "E31_E31") (pintype "passive"))
      (node (ref "J1") (pin "E32") (pinfunction "E32_E32") (pintype "passive"))
      (node (ref "J1") (pin "E33") (pinfunction "E33_E33") (pintype "passive"))
      (node (ref "J1") (pin "E38") (pinfunction "E38_E38") (pintype "passive"))
      (node (ref "J1") (pin "E39") (pinfunction "E39_E39") (pintype "passive"))
      (node (ref "J1") (pin "E40") (pinfunction "E40_E40") (pintype "passive"))
      (node (ref "U10") (pin "15") (pinfunction "DGND_15") (pintype "passive"))
      (node (ref "U10") (pin "19") (pinfunction "AGND_19") (pintype "passive"))
      (node (ref "U11") (pin "5") (pinfunction "+IN_B_5") (pintype "input"))
      (node (ref "U12") (pin "15") (pinfunction "DGND_15") (pintype "passive"))
      (node (ref "U12") (pin "19") (pinfunction "AGND_19") (pintype "passive"))
      (node (ref "U13") (pin "5") (pinfunction "+IN_B_5") (pintype "input"))
      (node (ref "U14") (pin "15") (pinfunction "DGND_15") (pintype "passive"))
      (node (ref "U14") (pin "19") (pinfunction "AGND_19") (pintype "passive"))
      (node (ref "U15") (pin "5") (pinfunction "+IN_B_5") (pintype "input"))
      (node (ref "U16") (pin "15") (pinfunction "DGND_15") (pintype "passive"))
      (node (ref "U16") (pin "19") (pinfunction "AGND_19") (pintype "passive"))
      (node (ref "U17") (pin "5") (pinfunction "+IN_B_5") (pintype "input"))
      (node (ref "U18") (pin "15") (pinfunction "DGND_15") (pintype "passive"))
      (node (ref "U18") (pin "19") (pinfunction "AGND_19") (pintype "passive"))
      (node (ref "U19") (pin "5") (pinfunction "+IN_B_5") (pintype "input"))
      (node (ref "U20") (pin "15") (pinfunction "DGND_15") (pintype "passive"))
      (node (ref "U20") (pin "19") (pinfunction "AGND_19") (pintype "passive"))
      (node (ref "U21") (pin "5") (pinfunction "+IN_B_5") (pintype "input"))
      (node (ref "U22") (pin "15") (pinfunction "DGND_15") (pintype "passive"))
      (node (ref "U22") (pin "19") (pinfunction "AGND_19") (pintype "passive"))
      (node (ref "U23") (pin "5") (pinfunction "+IN_B_5") (pintype "input"))
      (node (ref "U24") (pin "15") (pinfunction "DGND_15") (pintype "passive"))
      (node (ref "U24") (pin "19") (pinfunction "AGND_19") (pintype "passive"))
      (node (ref "U25") (pin "5") (pinfunction "+IN_B_5") (pintype "input"))
      (node (ref "U26") (pin "15") (pinfunction "DGND_15") (pintype "passive"))
      (node (ref "U26") (pin "19") (pinfunction "AGND_19") (pintype "passive"))
      (node (ref "U27") (pin "5") (pinfunction "+IN_B_5") (pintype "input"))
      (node (ref "U28") (pin "3") (pinfunction "GND_3") (pintype "passive"))
      (node (ref "U29") (pin "1") (pinfunction "GND_1") (pintype "passive"))
      (node (ref "U4") (pin "15") (pinfunction "DGND_15") (pintype "passive"))
      (node (ref "U4") (pin "19") (pinfunction "AGND_19") (pintype "passive"))
      (node (ref "U5") (pin "5") (pinfunction "+IN_B_5") (pintype "input"))
      (node (ref "U6") (pin "15") (pinfunction "DGND_15") (pintype "passive"))
      (node (ref "U6") (pin "19") (pinfunction "AGND_19") (pintype "passive"))
      (node (ref "U7") (pin "5") (pinfunction "+IN_B_5") (pintype "input"))
      (node (ref "U8") (pin "15") (pinfunction "DGND_15") (pintype "passive"))
      (node (ref "U8") (pin "19") (pinfunction "AGND_19") (pintype "passive"))
      (node (ref "U9") (pin "5") (pinfunction "+IN_B_5") (pintype "input"))
      (node (ref "X1") (pin "11") (pinfunction "11_11") (pintype "passive"))
      (node (ref "X1") (pin "13") (pinfunction "13_13") (pintype "passive"))
      (node (ref "X1") (pin "15") (pinfunction "15_15") (pintype "passive"))
      (node (ref "X1") (pin "18") (pinfunction "18_18") (pintype "passive"))
      (node (ref "X1") (pin "19") (pinfunction "19_19") (pintype "passive"))
      (node (ref "X1") (pin "20") (pinfunction "20_20") (pintype "passive"))
      (node (ref "X1") (pin "21") (pinfunction "21_21") (pintype "passive"))
      (node (ref "X1") (pin "22") (pinfunction "22_22") (pintype "passive"))
      (node (ref "X1") (pin "23") (pinfunction "23_23") (pintype "passive"))
      (node (ref "X1") (pin "24") (pinfunction "24_24") (pintype "passive"))
      (node (ref "X1") (pin "25") (pinfunction "25_25") (pintype "passive"))
      (node (ref "X1") (pin "26") (pinfunction "26_26") (pintype "passive"))
      (node (ref "X1") (pin "27") (pinfunction "27_27") (pintype "passive"))
      (node (ref "X1") (pin "28") (pinfunction "28_28") (pintype "passive"))
      (node (ref "X1") (pin "29") (pinfunction "29_29") (pintype "passive"))
      (node (ref "X1") (pin "3") (pinfunction "3_3") (pintype "passive"))
      (node (ref "X1") (pin "30") (pinfunction "30_30") (pintype "passive"))
      (node (ref "X1") (pin "31") (pinfunction "31_31") (pintype "passive"))
      (node (ref "X1") (pin "32") (pinfunction "32_32") (pintype "passive"))
      (node (ref "X1") (pin "36") (pinfunction "36_36") (pintype "passive"))
      (node (ref "X1") (pin "38") (pinfunction "38_38") (pintype "passive"))
      (node (ref "X1") (pin "40") (pinfunction "40_40") (pintype "passive"))
      (node (ref "X1") (pin "42") (pinfunction "42_42") (pintype "passive"))
      (node (ref "X1") (pin "44") (pinfunction "44_44") (pintype "passive"))
      (node (ref "X1") (pin "46") (pinfunction "46_46") (pintype "passive"))
      (node (ref "X1") (pin "48") (pinfunction "48_48") (pintype "passive"))
      (node (ref "X1") (pin "5") (pinfunction "5_5") (pintype "passive"))
      (node (ref "X1") (pin "7") (pinfunction "7_7") (pintype "passive"))
      (node (ref "X1") (pin "9") (pinfunction "9_9") (pintype "passive"))
    )
    (net (code "148") (name "INV_1") (class "Default")
      (node (ref "C34") (pin "1") (pinfunction "1_1") (pintype "passive"))
      (node (ref "U30") (pin "6") (pinfunction "-INB_6") (pintype "input"))
      (node (ref "U4") (pin "1") (pinfunction "INV_1") (pintype "input"))
    )
    (net (code "149") (name "INV_2") (class "Default")
      (node (ref "C46") (pin "1") (pinfunction "1_1") (pintype "passive"))
      (node (ref "U31") (pin "6") (pinfunction "-INB_6") (pintype "input"))
      (node (ref "U6") (pin "1") (pinfunction "INV_1") (pintype "input"))
    )
    (net (code "150") (name "INV_3") (class "Default")
      (node (ref "C58") (pin "1") (pinfunction "1_1") (pintype "passive"))
      (node (ref "U32") (pin "6") (pinfunction "-INB_6") (pintype "input"))
      (node (ref "U8") (pin "1") (pinfunction "INV_1") (pintype "input"))
    )
    (net (code "151") (name "INV_4") (class "Default")
      (node (ref "C70") (pin "1") (pinfunction "1_1") (pintype "passive"))
      (node (ref "U10") (pin "1") (pinfunction "INV_1") (pintype "input"))
      (node (ref "U33") (pin "6") (pinfunction "-INB_6") (pintype "input"))
    )
    (net (code "152") (name "INV_5") (class "Default")
      (node (ref "C82") (pin "1") (pinfunction "1_1") (pintype "passive"))
      (node (ref "U12") (pin "1") (pinfunction "INV_1") (pintype "input"))
      (node (ref "U34") (pin "6") (pinfunction "-INB_6") (pintype "input"))
    )
    (net (code "153") (name "INV_6") (class "Default")
      (node (ref "C94") (pin "1") (pinfunction "1_1") (pintype "passive"))
      (node (ref "U14") (pin "1") (pinfunction "INV_1") (pintype "input"))
      (node (ref "U35") (pin "6") (pinfunction "-INB_6") (pintype "input"))
    )
    (net (code "154") (name "INV_7") (class "Default")
      (node (ref "C106") (pin "1") (pinfunction "1_1") (pintype "passive"))
      (node (ref "U16") (pin "1") (pinfunction "INV_1") (pintype "input"))
      (node (ref "U30") (pin "2") (pinfunction "-INA_2") (pintype "input"))
    )
    (net (code "155") (name "INV_8") (class "Default")
      (node (ref "C118") (pin "1") (pinfunction "1_1") (pintype "passive"))
      (node (ref "U18") (pin "1") (pinfunction "INV_1") (pintype "input"))
      (node (ref "U31") (pin "2") (pinfunction "-INA_2") (pintype "input"))
    )
    (net (code "156") (name "INV_9") (class "Default")
      (node (ref "C130") (pin "1") (pinfunction "1_1") (pintype "passive"))
      (node (ref "U20") (pin "1") (pinfunction "INV_1") (pintype "input"))
      (node (ref "U32") (pin "2") (pinfunction "-INA_2") (pintype "input"))
    )
    (net (code "157") (name "INV_10") (class "Default")
      (node (ref "C142") (pin "1") (pinfunction "1_1") (pintype "passive"))
      (node (ref "U22") (pin "1") (pinfunction "INV_1") (pintype "input"))
      (node (ref "U33") (pin "2") (pinfunction "-INA_2") (pintype "input"))
    )
    (net (code "158") (name "INV_11") (class "Default")
      (node (ref "C154") (pin "1") (pinfunction "1_1") (pintype "passive"))
      (node (ref "U24") (pin "1") (pinfunction "INV_1") (pintype "input"))
      (node (ref "U34") (pin "2") (pinfunction "-INA_2") (pintype "input"))
    )
    (net (code "159") (name "INV_12") (class "Default")
      (node (ref "C166") (pin "1") (pinfunction "1_1") (pintype "passive"))
      (node (ref "U26") (pin "1") (pinfunction "INV_1") (pintype "input"))
      (node (ref "U35") (pin "2") (pinfunction "-INA_2") (pintype "input"))
    )
    (net (code "160") (name "LDAC") (class "Default")
      (node (ref "ISO11") (pin "10") (pinfunction "B5_10") (pintype "bidirectional"))
      (node (ref "U10") (pin "8") (pinfunction "~{LDAC}_8") (pintype "input"))
      (node (ref "U12") (pin "8") (pinfunction "~{LDAC}_8") (pintype "input"))
      (node (ref "U14") (pin "8") (pinfunction "~{LDAC}_8") (pintype "input"))
      (node (ref "U16") (pin "8") (pinfunction "~{LDAC}_8") (pintype "input"))
      (node (ref "U18") (pin "8") (pinfunction "~{LDAC}_8") (pintype "input"))
      (node (ref "U20") (pin "8") (pinfunction "~{LDAC}_8") (pintype "input"))
      (node (ref "U22") (pin "8") (pinfunction "~{LDAC}_8") (pintype "input"))
      (node (ref "U24") (pin "8") (pinfunction "~{LDAC}_8") (pintype "input"))
      (node (ref "U26") (pin "8") (pinfunction "~{LDAC}_8") (pintype "input"))
      (node (ref "U4") (pin "8") (pinfunction "~{LDAC}_8") (pintype "input"))
      (node (ref "U6") (pin "8") (pinfunction "~{LDAC}_8") (pintype "input"))
      (node (ref "U8") (pin "8") (pinfunction "~{LDAC}_8") (pintype "input"))
    )
    (net (code "161") (name "Net-(U4-VREFNF)") (class "Default")
      (node (ref "U4") (pin "16") (pinfunction "VREFNF_16") (pintype "input"))
      (node (ref "U5") (pin "7") (pinfunction "OUT_B_7") (pintype "output"))
    )
    (net (code "162") (name "Net-(U4-VREFNS)") (class "Default")
      (node (ref "U4") (pin "17") (pinfunction "VREFNS_17") (pintype "input"))
      (node (ref "U5") (pin "6") (pinfunction "-IN_B_6") (pintype "input"))
    )
    (net (code "163") (name "Net-(U4-VREFPF)") (class "Default")
      (node (ref "U4") (pin "4") (pinfunction "VREFPF_4") (pintype "input"))
      (node (ref "U5") (pin "1") (pinfunction "OUT_A_1") (pintype "output"))
    )
    (net (code "164") (name "Net-(U4-VREFPS)") (class "Default")
      (node (ref "U4") (pin "3") (pinfunction "VREFPS_3") (pintype "input"))
      (node (ref "U5") (pin "2") (pinfunction "-IN_A_2") (pintype "input"))
    )
    (net (code "165") (name "Net-(U6-VREFNF)") (class "Default")
      (node (ref "U6") (pin "16") (pinfunction "VREFNF_16") (pintype "input"))
      (node (ref "U7") (pin "7") (pinfunction "OUT_B_7") (pintype "output"))
    )
    (net (code "166") (name "Net-(U6-VREFNS)") (class "Default")
      (node (ref "U6") (pin "17") (pinfunction "VREFNS_17") (pintype "input"))
      (node (ref "U7") (pin "6") (pinfunction "-IN_B_6") (pintype "input"))
    )
    (net (code "167") (name "Net-(U6-VREFPF)") (class "Default")
      (node (ref "U6") (pin "4") (pinfunction "VREFPF_4") (pintype "input"))
      (node (ref "U7") (pin "1") (pinfunction "OUT_A_1") (pintype "output"))
    )
    (net (code "168") (name "Net-(U6-VREFPS)") (class "Default")
      (node (ref "U6") (pin "3") (pinfunction "VREFPS_3") (pintype "input"))
      (node (ref "U7") (pin "2") (pinfunction "-IN_A_2") (pintype "input"))
    )
    (net (code "169") (name "Net-(U8-VREFNF)") (class "Default")
      (node (ref "U8") (pin "16") (pinfunction "VREFNF_16") (pintype "input"))
      (node (ref "U9") (pin "7") (pinfunction "OUT_B_7") (pintype "output"))
    )
    (net (code "170") (name "Net-(U8-VREFNS)") (class "Default")
      (node (ref "U8") (pin "17") (pinfunction "VREFNS_17") (pintype "input"))
      (node (ref "U9") (pin "6") (pinfunction "-IN_B_6") (pintype "input"))
    )
    (net (code "171") (name "Net-(U8-VREFPF)") (class "Default")
      (node (ref "U8") (pin "4") (pinfunction "VREFPF_4") (pintype "input"))
      (node (ref "U9") (pin "1") (pinfunction "OUT_A_1") (pintype "output"))
    )
    (net (code "172") (name "Net-(U8-VREFPS)") (class "Default")
      (node (ref "U8") (pin "3") (pinfunction "VREFPS_3") (pintype "input"))
      (node (ref "U9") (pin "2") (pinfunction "-IN_A_2") (pintype "input"))
    )
    (net (code "173") (name "Net-(U10-VREFNF)") (class "Default")
      (node (ref "U10") (pin "16") (pinfunction "VREFNF_16") (pintype "input"))
      (node (ref "U11") (pin "7") (pinfunction "OUT_B_7") (pintype "output"))
    )
    (net (code "174") (name "Net-(U10-VREFNS)") (class "Default")
      (node (ref "U10") (pin "17") (pinfunction "VREFNS_17") (pintype "input"))
      (node (ref "U11") (pin "6") (pinfunction "-IN_B_6") (pintype "input"))
    )
    (net (code "175") (name "Net-(U10-VREFPF)") (class "Default")
      (node (ref "U10") (pin "4") (pinfunction "VREFPF_4") (pintype "input"))
      (node (ref "U11") (pin "1") (pinfunction "OUT_A_1") (pintype "output"))
    )
    (net (code "176") (name "Net-(U10-VREFPS)") (class "Default")
      (node (ref "U10") (pin "3") (pinfunction "VREFPS_3") (pintype "input"))
      (node (ref "U11") (pin "2") (pinfunction "-IN_A_2") (pintype "input"))
    )
    (net (code "177") (name "Net-(U12-VREFNF)") (class "Default")
      (node (ref "U12") (pin "16") (pinfunction "VREFNF_16") (pintype "input"))
      (node (ref "U13") (pin "7") (pinfunction "OUT_B_7") (pintype "output"))
    )
    (net (code "178") (name "Net-(U12-VREFNS)") (class "Default")
      (node (ref "U12") (pin "17") (pinfunction "VREFNS_17") (pintype "input"))
      (node (ref "U13") (pin "6") (pinfunction "-IN_B_6") (pintype "input"))
    )
    (net (code "179") (name "Net-(U12-VREFPF)") (class "Default")
      (node (ref "U12") (pin "4") (pinfunction "VREFPF_4") (pintype "input"))
      (node (ref "U13") (pin "1") (pinfunction "OUT_A_1") (pintype "output"))
    )
    (net (code "180") (name "Net-(U12-VREFPS)") (class "Default")
      (node (ref "U12") (pin "3") (pinfunction "VREFPS_3") (pintype "input"))
      (node (ref "U13") (pin "2") (pinfunction "-IN_A_2") (pintype "input"))
    )
    (net (code "181") (name "Net-(U14-VREFNF)") (class "Default")
      (node (ref "U14") (pin "16") (pinfunction "VREFNF_16") (pintype "input"))
      (node (ref "U15") (pin "7") (pinfunction "OUT_B_7") (pintype "output"))
    )
    (net (code "182") (name "Net-(U14-VREFNS)") (class "Default")
      (node (ref "U14") (pin "17") (pinfunction "VREFNS_17") (pintype "input"))
      (node (ref "U15") (pin "6") (pinfunction "-IN_B_6") (pintype "input"))
    )
    (net (code "183") (name "Net-(U14-VREFPF)") (class "Default")
      (node (ref "U14") (pin "4") (pinfunction "VREFPF_4") (pintype "input"))
      (node (ref "U15") (pin "1") (pinfunction "OUT_A_1") (pintype "output"))
    )
    (net (code "184") (name "Net-(U14-VREFPS)") (class "Default")
      (node (ref "U14") (pin "3") (pinfunction "VREFPS_3") (pintype "input"))
      (node (ref "U15") (pin "2") (pinfunction "-IN_A_2") (pintype "input"))
    )
    (net (code "185") (name "Net-(U16-VREFNF)") (class "Default")
      (node (ref "U16") (pin "16") (pinfunction "VREFNF_16") (pintype "input"))
      (node (ref "U17") (pin "7") (pinfunction "OUT_B_7") (pintype "output"))
    )
    (net (code "186") (name "Net-(U16-VREFNS)") (class "Default")
      (node (ref "U16") (pin "17") (pinfunction "VREFNS_17") (pintype "input"))
      (node (ref "U17") (pin "6") (pinfunction "-IN_B_6") (pintype "input"))
    )
    (net (code "187") (name "Net-(U16-VREFPF)") (class "Default")
      (node (ref "U16") (pin "4") (pinfunction "VREFPF_4") (pintype "input"))
      (node (ref "U17") (pin "1") (pinfunction "OUT_A_1") (pintype "output"))
    )
    (net (code "188") (name "Net-(U16-VREFPS)") (class "Default")
      (node (ref "U16") (pin "3") (pinfunction "VREFPS_3") (pintype "input"))
      (node (ref "U17") (pin "2") (pinfunction "-IN_A_2") (pintype "input"))
    )
    (net (code "189") (name "Net-(U18-VREFNF)") (class "Default")
      (node (ref "U18") (pin "16") (pinfunction "VREFNF_16") (pintype "input"))
      (node (ref "U19") (pin "7") (pinfunction "OUT_B_7") (pintype "output"))
    )
    (net (code "190") (name "Net-(U18-VREFNS)") (class "Default")
      (node (ref "U18") (pin "17") (pinfunction "VREFNS_17") (pintype "input"))
      (node (ref "U19") (pin "6") (pinfunction "-IN_B_6") (pintype "input"))
    )
    (net (code "191") (name "Net-(U18-VREFPF)") (class "Default")
      (node (ref "U18") (pin "4") (pinfunction "VREFPF_4") (pintype "input"))
      (node (ref "U19") (pin "1") (pinfunction "OUT_A_1") (pintype "output"))
    )
    (net (code "192") (name "Net-(U18-VREFPS)") (class "Default")
      (node (ref "U18") (pin "3") (pinfunction "VREFPS_3") (pintype "input"))
      (node (ref "U19") (pin "2") (pinfunction "-IN_A_2") (pintype "input"))
    )
    (net (code "193") (name "Net-(U20-VREFNF)") (class "Default")
      (node (ref "U20") (pin "16") (pinfunction "VREFNF_16") (pintype "input"))
      (node (ref "U21") (pin "7") (pinfunction "OUT_B_7") (pintype "output"))
    )
    (net (code "194") (name "Net-(U20-VREFNS)") (class "Default")
      (node (ref "U20") (pin "17") (pinfunction "VREFNS_17") (pintype "input"))
      (node (ref "U21") (pin "6") (pinfunction "-IN_B_6") (pintype "input"))
    )
    (net (code "195") (name "Net-(U20-VREFPF)") (class "Default")
      (node (ref "U20") (pin "4") (pinfunction "VREFPF_4") (pintype "input"))
      (node (ref "U21") (pin "1") (pinfunction "OUT_A_1") (pintype "output"))
    )
    (net (code "196") (name "Net-(U20-VREFPS)") (class "Default")
      (node (ref "U20") (pin "3") (pinfunction "VREFPS_3") (pintype "input"))
      (node (ref "U21") (pin "2") (pinfunction "-IN_A_2") (pintype "input"))
    )
    (net (code "197") (name "Net-(U22-VREFNF)") (class "Default")
      (node (ref "U22") (pin "16") (pinfunction "VREFNF_16") (pintype "input"))
      (node (ref "U23") (pin "7") (pinfunction "OUT_B_7") (pintype "output"))
    )
    (net (code "198") (name "Net-(U22-VREFNS)") (class "Default")
      (node (ref "U22") (pin "17") (pinfunction "VREFNS_17") (pintype "input"))
      (node (ref "U23") (pin "6") (pinfunction "-IN_B_6") (pintype "input"))
    )
    (net (code "199") (name "Net-(U22-VREFPF)") (class "Default")
      (node (ref "U22") (pin "4") (pinfunction "VREFPF_4") (pintype "input"))
      (node (ref "U23") (pin "1") (pinfunction "OUT_A_1") (pintype "output"))
    )
    (net (code "200") (name "Net-(U22-VREFPS)") (class "Default")
      (node (ref "U22") (pin "3") (pinfunction "VREFPS_3") (pintype "input"))
      (node (ref "U23") (pin "2") (pinfunction "-IN_A_2") (pintype "input"))
    )
    (net (code "201") (name "Net-(U24-VREFNF)") (class "Default")
      (node (ref "U24") (pin "16") (pinfunction "VREFNF_16") (pintype "input"))
      (node (ref "U25") (pin "7") (pinfunction "OUT_B_7") (pintype "output"))
    )
    (net (code "202") (name "Net-(U24-VREFNS)") (class "Default")
      (node (ref "U24") (pin "17") (pinfunction "VREFNS_17") (pintype "input"))
      (node (ref "U25") (pin "6") (pinfunction "-IN_B_6") (pintype "input"))
    )
    (net (code "203") (name "Net-(U24-VREFPF)") (class "Default")
      (node (ref "U24") (pin "4") (pinfunction "VREFPF_4") (pintype "input"))
      (node (ref "U25") (pin "1") (pinfunction "OUT_A_1") (pintype "output"))
    )
    (net (code "204") (name "Net-(U24-VREFPS)") (class "Default")
      (node (ref "U24") (pin "3") (pinfunction "VREFPS_3") (pintype "input"))
      (node (ref "U25") (pin "2") (pinfunction "-IN_A_2") (pintype "input"))
    )
    (net (code "205") (name "Net-(U26-VREFNF)") (class "Default")
      (node (ref "U26") (pin "16") (pinfunction "VREFNF_16") (pintype "input"))
      (node (ref "U27") (pin "7") (pinfunction "OUT_B_7") (pintype "output"))
    )
    (net (code "206") (name "Net-(U26-VREFNS)") (class "Default")
      (node (ref "U26") (pin "17") (pinfunction "VREFNS_17") (pintype "input"))
      (node (ref "U27") (pin "6") (pinfunction "-IN_B_6") (pintype "input"))
    )
    (net (code "207") (name "Net-(U26-VREFPF)") (class "Default")
      (node (ref "U26") (pin "4") (pinfunction "VREFPF_4") (pintype "input"))
      (node (ref "U27") (pin "1") (pinfunction "OUT_A_1") (pintype "output"))
    )
    (net (code "208") (name "Net-(U26-VREFPS)") (class "Default")
      (node (ref "U26") (pin "3") (pinfunction "VREFPS_3") (pintype "input"))
      (node (ref "U27") (pin "2") (pinfunction "-IN_A_2") (pintype "input"))
    )
    (net (code "209") (name "OUT0") (class "Default")
      (node (ref "ISO9") (pin "3") (pinfunction "A1_3") (pintype "bidirectional"))
    )
    (net (code "210") (name "OUT1") (class "Default")
      (node (ref "ISO9") (pin "4") (pinfunction "A2_4") (pintype "bidirectional"))
    )
    (net (code "211") (name "OUT2") (class "Default")
      (node (ref "ISO9") (pin "5") (pinfunction "A3_5") (pintype "bidirectional"))
    )
    (net (code "212") (name "OUT3") (class "Default")
      (node (ref "ISO9") (pin "6") (pinfunction "A4_6") (pintype "bidirectional"))
    )
    (net (code "213") (name "OUT4") (class "Default")
      (node (ref "ISO9") (pin "7") (pinfunction "A5_7") (pintype "bidirectional"))
    )
    (net (code "214") (name "OUT5") (class "Default")
      (node (ref "ISO10") (pin "3") (pinfunction "A1_3") (pintype "bidirectional"))
    )
    (net (code "215") (name "OUT6") (class "Default")
      (node (ref "ISO10") (pin "4") (pinfunction "A2_4") (pintype "bidirectional"))
    )
    (net (code "216") (name "OUT7") (class "Default")
      (node (ref "ISO10") (pin "5") (pinfunction "A3_5") (pintype "bidirectional"))
    )
    (net (code "217") (name "OUTCLK-IN") (class "Default")
      (node (ref "ISO1") (pin "10") (pinfunction "B5_10") (pintype "bidirectional"))
    )
    (net (code "218") (name "OUTCLK-OUT") (class "Default")
      (node (ref "ISO10") (pin "6") (pinfunction "A4_6") (pintype "bidirectional"))
    )
    (net (code "219") (name "RFB_1") (class "Default")
      (node (ref "C34") (pin "2") (pinfunction "2_2") (pintype "passive"))
      (node (ref "R5") (pin "1") (pinfunction "1_1") (pintype "passive"))
      (node (ref "U30") (pin "7") (pinfunction "OUTB_7") (pintype "output"))
      (node (ref "U4") (pin "20") (pinfunction "RFB_20") (pintype "input"))
    )
    (net (code "220") (name "RFB_2") (class "Default")
      (node (ref "C46") (pin "2") (pinfunction "2_2") (pintype "passive"))
      (node (ref "R9") (pin "1") (pinfunction "1_1") (pintype "passive"))
      (node (ref "U31") (pin "7") (pinfunction "OUTB_7") (pintype "output"))
      (node (ref "U6") (pin "20") (pinfunction "RFB_20") (pintype "input"))
    )
    (net (code "221") (name "RFB_3") (class "Default")
      (node (ref "C58") (pin "2") (pinfunction "2_2") (pintype "passive"))
      (node (ref "R11") (pin "1") (pinfunction "1_1") (pintype "passive"))
      (node (ref "U32") (pin "7") (pinfunction "OUTB_7") (pintype "output"))
      (node (ref "U8") (pin "20") (pinfunction "RFB_20") (pintype "input"))
    )
    (net (code "222") (name "RFB_4") (class "Default")
      (node (ref "C70") (pin "2") (pinfunction "2_2") (pintype "passive"))
      (node (ref "R13") (pin "1") (pinfunction "1_1") (pintype "passive"))
      (node (ref "U10") (pin "20") (pinfunction "RFB_20") (pintype "input"))
      (node (ref "U33") (pin "7") (pinfunction "OUTB_7") (pintype "output"))
    )
    (net (code "223") (name "RFB_5") (class "Default")
      (node (ref "C82") (pin "2") (pinfunction "2_2") (pintype "passive"))
      (node (ref "R15") (pin "1") (pinfunction "1_1") (pintype "passive"))
      (node (ref "U12") (pin "20") (pinfunction "RFB_20") (pintype "input"))
      (node (ref "U34") (pin "7") (pinfunction "OUTB_7") (pintype "output"))
    )
    (net (code "224") (name "RFB_6") (class "Default")
      (node (ref "C94") (pin "2") (pinfunction "2_2") (pintype "passive"))
      (node (ref "R17") (pin "1") (pinfunction "1_1") (pintype "passive"))
      (node (ref "U14") (pin "20") (pinfunction "RFB_20") (pintype "input"))
      (node (ref "U35") (pin "7") (pinfunction "OUTB_7") (pintype "output"))
    )
    (net (code "225") (name "RFB_7") (class "Default")
      (node (ref "C106") (pin "2") (pinfunction "2_2") (pintype "passive"))
      (node (ref "R4") (pin "1") (pinfunction "1_1") (pintype "passive"))
      (node (ref "U16") (pin "20") (pinfunction "RFB_20") (pintype "input"))
      (node (ref "U30") (pin "1") (pinfunction "OUTA_1") (pintype "output"))
    )
    (net (code "226") (name "RFB_8") (class "Default")
      (node (ref "C118") (pin "2") (pinfunction "2_2") (pintype "passive"))
      (node (ref "R8") (pin "1") (pinfunction "1_1") (pintype "passive"))
      (node (ref "U18") (pin "20") (pinfunction "RFB_20") (pintype "input"))
      (node (ref "U31") (pin "1") (pinfunction "OUTA_1") (pintype "output"))
    )
    (net (code "227") (name "RFB_9") (class "Default")
      (node (ref "C130") (pin "2") (pinfunction "2_2") (pintype "passive"))
      (node (ref "R10") (pin "1") (pinfunction "1_1") (pintype "passive"))
      (node (ref "U20") (pin "20") (pinfunction "RFB_20") (pintype "input"))
      (node (ref "U32") (pin "1") (pinfunction "OUTA_1") (pintype "output"))
    )
    (net (code "228") (name "RFB_10") (class "Default")
      (node (ref "C142") (pin "2") (pinfunction "2_2") (pintype "passive"))
      (node (ref "R12") (pin "1") (pinfunction "1_1") (pintype "passive"))
      (node (ref "U22") (pin "20") (pinfunction "RFB_20") (pintype "input"))
      (node (ref "U33") (pin "1") (pinfunction "OUTA_1") (pintype "output"))
    )
    (net (code "229") (name "RFB_11") (class "Default")
      (node (ref "C154") (pin "2") (pinfunction "2_2") (pintype "passive"))
      (node (ref "R14") (pin "1") (pinfunction "1_1") (pintype "passive"))
      (node (ref "U24") (pin "20") (pinfunction "RFB_20") (pintype "input"))
      (node (ref "U34") (pin "1") (pinfunction "OUTA_1") (pintype "output"))
    )
    (net (code "230") (name "RFB_12") (class "Default")
      (node (ref "C166") (pin "2") (pinfunction "2_2") (pintype "passive"))
      (node (ref "R16") (pin "1") (pinfunction "1_1") (pintype "passive"))
      (node (ref "U26") (pin "20") (pinfunction "RFB_20") (pintype "input"))
      (node (ref "U35") (pin "1") (pinfunction "OUTA_1") (pintype "output"))
    )
    (net (code "231") (name "SCLK_1") (class "Default")
      (node (ref "ISO8") (pin "12") (pinfunction "B3_12") (pintype "bidirectional"))
      (node (ref "U4") (pin "13") (pinfunction "SCLK_13") (pintype "input"))
    )
    (net (code "232") (name "SCLK_2") (class "Default")
      (node (ref "ISO7") (pin "14") (pinfunction "B1_14") (pintype "bidirectional"))
      (node (ref "U6") (pin "13") (pinfunction "SCLK_13") (pintype "input"))
    )
    (net (code "233") (name "SCLK_3") (class "Default")
      (node (ref "ISO7") (pin "11") (pinfunction "B4_11") (pintype "bidirectional"))
      (node (ref "U8") (pin "13") (pinfunction "SCLK_13") (pintype "input"))
    )
    (net (code "234") (name "SCLK_4") (class "Default")
      (node (ref "ISO6") (pin "13") (pinfunction "B2_13") (pintype "bidirectional"))
      (node (ref "U10") (pin "13") (pinfunction "SCLK_13") (pintype "input"))
    )
    (net (code "235") (name "SCLK_5") (class "Default")
      (node (ref "ISO6") (pin "10") (pinfunction "B5_10") (pintype "bidirectional"))
      (node (ref "U12") (pin "13") (pinfunction "SCLK_13") (pintype "input"))
    )
    (net (code "236") (name "SCLK_6") (class "Default")
      (node (ref "ISO5") (pin "12") (pinfunction "B3_12") (pintype "bidirectional"))
      (node (ref "U14") (pin "13") (pinfunction "SCLK_13") (pintype "input"))
    )
    (net (code "237") (name "SCLK_7") (class "Default")
      (node (ref "ISO4") (pin "11") (pinfunction "B4_11") (pintype "bidirectional"))
      (node (ref "U16") (pin "13") (pinfunction "SCLK_13") (pintype "input"))
    )
    (net (code "238") (name "SCLK_8") (class "Default")
      (node (ref "ISO4") (pin "14") (pinfunction "B1_14") (pintype "bidirectional"))
      (node (ref "U18") (pin "13") (pinfunction "SCLK_13") (pintype "input"))
    )
    (net (code "239") (name "SCLK_9") (class "Default")
      (node (ref "ISO3") (pin "13") (pinfunction "B2_13") (pintype "bidirectional"))
      (node (ref "U20") (pin "13") (pinfunction "SCLK_13") (pintype "input"))
    )
    (net (code "240") (name "SCLK_10") (class "Default")
      (node (ref "ISO3") (pin "10") (pinfunction "B5_10") (pintype "bidirectional"))
      (node (ref "U22") (pin "13") (pinfunction "SCLK_13") (pintype "input"))
    )
    (net (code "241") (name "SCLK_11") (class "Default")
      (node (ref "ISO2") (pin "12") (pinfunction "B3_12") (pintype "bidirectional"))
      (node (ref "U24") (pin "13") (pinfunction "SCLK_13") (pintype "input"))
    )
    (net (code "242") (name "SCLK_12") (class "Default")
      (node (ref "ISO1") (pin "14") (pinfunction "B1_14") (pintype "bidirectional"))
      (node (ref "U26") (pin "13") (pinfunction "SCLK_13") (pintype "input"))
    )
    (net (code "243") (name "SDIN_1") (class "Default")
      (node (ref "ISO8") (pin "13") (pinfunction "B2_13") (pintype "bidirectional"))
      (node (ref "U4") (pin "12") (pinfunction "SDIN_12") (pintype "input"))
    )
    (net (code "244") (name "SDIN_2") (class "Default")
      (node (ref "ISO8") (pin "10") (pinfunction "B5_10") (pintype "bidirectional"))
      (node (ref "U6") (pin "12") (pinfunction "SDIN_12") (pintype "input"))
    )
    (net (code "245") (name "SDIN_3") (class "Default")
      (node (ref "ISO7") (pin "12") (pinfunction "B3_12") (pintype "bidirectional"))
      (node (ref "U8") (pin "12") (pinfunction "SDIN_12") (pintype "input"))
    )
    (net (code "246") (name "SDIN_4") (class "Default")
      (node (ref "ISO6") (pin "14") (pinfunction "B1_14") (pintype "bidirectional"))
      (node (ref "U10") (pin "12") (pinfunction "SDIN_12") (pintype "input"))
    )
    (net (code "247") (name "SDIN_5") (class "Default")
      (node (ref "ISO6") (pin "11") (pinfunction "B4_11") (pintype "bidirectional"))
      (node (ref "U12") (pin "12") (pinfunction "SDIN_12") (pintype "input"))
    )
    (net (code "248") (name "SDIN_6") (class "Default")
      (node (ref "ISO5") (pin "13") (pinfunction "B2_13") (pintype "bidirectional"))
      (node (ref "U14") (pin "12") (pinfunction "SDIN_12") (pintype "input"))
    )
    (net (code "249") (name "SDIN_7") (class "Default")
      (node (ref "ISO4") (pin "12") (pinfunction "B3_12") (pintype "bidirectional"))
      (node (ref "U16") (pin "12") (pinfunction "SDIN_12") (pintype "input"))
    )
    (net (code "250") (name "SDIN_8") (class "Default")
      (node (ref "ISO5") (pin "10") (pinfunction "B5_10") (pintype "bidirectional"))
      (node (ref "U18") (pin "12") (pinfunction "SDIN_12") (pintype "input"))
    )
    (net (code "251") (name "SDIN_9") (class "Default")
      (node (ref "ISO3") (pin "14") (pinfunction "B1_14") (pintype "bidirectional"))
      (node (ref "U20") (pin "12") (pinfunction "SDIN_12") (pintype "input"))
    )
    (net (code "252") (name "SDIN_10") (class "Default")
      (node (ref "ISO3") (pin "11") (pinfunction "B4_11") (pintype "bidirectional"))
      (node (ref "U22") (pin "12") (pinfunction "SDIN_12") (pintype "input"))
    )
    (net (code "253") (name "SDIN_11") (class "Default")
      (node (ref "ISO2") (pin "13") (pinfunction "B2_13") (pintype "bidirectional"))
      (node (ref "U24") (pin "12") (pinfunction "SDIN_12") (pintype "input"))
    )
    (net (code "254") (name "SDIN_12") (class "Default")
      (node (ref "ISO2") (pin "10") (pinfunction "B5_10") (pintype "bidirectional"))
      (node (ref "U26") (pin "12") (pinfunction "SDIN_12") (pintype "input"))
    )
    (net (code "255") (name "SDO_1") (class "Default")
      (node (ref "U4") (pin "11") (pinfunction "SDO_11") (pintype "output"))
    )
    (net (code "256") (name "SDO_2") (class "Default")
      (node (ref "U6") (pin "11") (pinfunction "SDO_11") (pintype "output"))
    )
    (net (code "257") (name "SDO_3") (class "Default")
      (node (ref "U8") (pin "11") (pinfunction "SDO_11") (pintype "output"))
    )
    (net (code "258") (name "SDO_4") (class "Default")
      (node (ref "U10") (pin "11") (pinfunction "SDO_11") (pintype "output"))
    )
    (net (code "259") (name "SDO_5") (class "Default")
      (node (ref "U12") (pin "11") (pinfunction "SDO_11") (pintype "output"))
    )
    (net (code "260") (name "SDO_6") (class "Default")
      (node (ref "U14") (pin "11") (pinfunction "SDO_11") (pintype "output"))
    )
    (net (code "261") (name "SDO_7") (class "Default")
      (node (ref "U16") (pin "11") (pinfunction "SDO_11") (pintype "output"))
    )
    (net (code "262") (name "SDO_8") (class "Default")
      (node (ref "U18") (pin "11") (pinfunction "SDO_11") (pintype "output"))
    )
    (net (code "263") (name "SDO_9") (class "Default")
      (node (ref "U20") (pin "11") (pinfunction "SDO_11") (pintype "output"))
    )
    (net (code "264") (name "SDO_10") (class "Default")
      (node (ref "U22") (pin "11") (pinfunction "SDO_11") (pintype "output"))
    )
    (net (code "265") (name "SDO_11") (class "Default")
      (node (ref "U24") (pin "11") (pinfunction "SDO_11") (pintype "output"))
    )
    (net (code "266") (name "SDO_12") (class "Default")
      (node (ref "U26") (pin "11") (pinfunction "SDO_11") (pintype "output"))
    )
    (net (code "267") (name "SYNCLK") (class "Default")
      (node (ref "J1") (pin "A24") (pinfunction "A24_A24") (pintype "passive"))
    )
    (net (code "268") (name "SYNC_1") (class "Default")
      (node (ref "ISO8") (pin "11") (pinfunction "B4_11") (pintype "bidirectional"))
      (node (ref "U4") (pin "14") (pinfunction "~{SYNC}_14") (pintype "input"))
    )
    (net (code "269") (name "SYNC_2") (class "Default")
      (node (ref "ISO7") (pin "13") (pinfunction "B2_13") (pintype "bidirectional"))
      (node (ref "U6") (pin "14") (pinfunction "~{SYNC}_14") (pintype "input"))
    )
    (net (code "270") (name "SYNC_3") (class "Default")
      (node (ref "ISO7") (pin "10") (pinfunction "B5_10") (pintype "bidirectional"))
      (node (ref "U8") (pin "14") (pinfunction "~{SYNC}_14") (pintype "input"))
    )
    (net (code "271") (name "SYNC_4") (class "Default")
      (node (ref "ISO6") (pin "12") (pinfunction "B3_12") (pintype "bidirectional"))
      (node (ref "U10") (pin "14") (pinfunction "~{SYNC}_14") (pintype "input"))
    )
    (net (code "272") (name "SYNC_5") (class "Default")
      (node (ref "ISO5") (pin "14") (pinfunction "B1_14") (pintype "bidirectional"))
      (node (ref "U12") (pin "14") (pinfunction "~{SYNC}_14") (pintype "input"))
    )
    (net (code "273") (name "SYNC_6") (class "Default")
      (node (ref "ISO5") (pin "11") (pinfunction "B4_11") (pintype "bidirectional"))
      (node (ref "U14") (pin "14") (pinfunction "~{SYNC}_14") (pintype "input"))
    )
    (net (code "274") (name "SYNC_7") (class "Default")
      (node (ref "ISO4") (pin "10") (pinfunction "B5_10") (pintype "bidirectional"))
      (node (ref "U16") (pin "14") (pinfunction "~{SYNC}_14") (pintype "input"))
    )
    (net (code "275") (name "SYNC_8") (class "Default")
      (node (ref "ISO4") (pin "13") (pinfunction "B2_13") (pintype "bidirectional"))
      (node (ref "U18") (pin "14") (pinfunction "~{SYNC}_14") (pintype "input"))
    )
    (net (code "276") (name "SYNC_9") (class "Default")
      (node (ref "ISO3") (pin "12") (pinfunction "B3_12") (pintype "bidirectional"))
      (node (ref "U20") (pin "14") (pinfunction "~{SYNC}_14") (pintype "input"))
    )
    (net (code "277") (name "SYNC_10") (class "Default")
      (node (ref "ISO2") (pin "14") (pinfunction "B1_14") (pintype "bidirectional"))
      (node (ref "U22") (pin "14") (pinfunction "~{SYNC}_14") (pintype "input"))
    )
    (net (code "278") (name "SYNC_11") (class "Default")
      (node (ref "ISO2") (pin "11") (pinfunction "B4_11") (pintype "bidirectional"))
      (node (ref "U24") (pin "14") (pinfunction "~{SYNC}_14") (pintype "input"))
    )
    (net (code "279") (name "SYNC_12") (class "Default")
      (node (ref "ISO1") (pin "13") (pinfunction "B2_13") (pintype "bidirectional"))
      (node (ref "U26") (pin "14") (pinfunction "~{SYNC}_14") (pintype "input"))
    )
    (net (code "280") (name "SYSCLK") (class "Default")
      (node (ref "J1") (pin "B23") (pinfunction "B23_B23") (pintype "passive"))
    )
    (net (code "281") (name "VOUT_1") (class "Default")
      (node (ref "R5") (pin "2") (pinfunction "2_2") (pintype "passive"))
      (node (ref "X1") (pin "8") (pinfunction "8_8") (pintype "passive"))
    )
    (net (code "282") (name "VOUT_2") (class "Default")
      (node (ref "R9") (pin "2") (pinfunction "2_2") (pintype "passive"))
      (node (ref "X1") (pin "41") (pinfunction "41_41") (pintype "passive"))
    )
    (net (code "283") (name "VOUT_3") (class "Default")
      (node (ref "R11") (pin "2") (pinfunction "2_2") (pintype "passive"))
      (node (ref "X1") (pin "6") (pinfunction "6_6") (pintype "passive"))
    )
    (net (code "284") (name "VOUT_4") (class "Default")
      (node (ref "R13") (pin "2") (pinfunction "2_2") (pintype "passive"))
      (node (ref "X1") (pin "39") (pinfunction "39_39") (pintype "passive"))
    )
    (net (code "285") (name "VOUT_5") (class "Default")
      (node (ref "R15") (pin "2") (pinfunction "2_2") (pintype "passive"))
      (node (ref "X1") (pin "37") (pinfunction "37_37") (pintype "passive"))
    )
    (net (code "286") (name "VOUT_6") (class "Default")
      (node (ref "R17") (pin "2") (pinfunction "2_2") (pintype "passive"))
      (node (ref "X1") (pin "4") (pinfunction "4_4") (pintype "passive"))
    )
    (net (code "287") (name "VOUT_7") (class "Default")
      (node (ref "R4") (pin "2") (pinfunction "2_2") (pintype "passive"))
      (node (ref "X1") (pin "14") (pinfunction "14_14") (pintype "passive"))
    )
    (net (code "288") (name "VOUT_8") (class "Default")
      (node (ref "R8") (pin "2") (pinfunction "2_2") (pintype "passive"))
      (node (ref "X1") (pin "47") (pinfunction "47_47") (pintype "passive"))
    )
    (net (code "289") (name "VOUT_9") (class "Default")
      (node (ref "R10") (pin "2") (pinfunction "2_2") (pintype "passive"))
      (node (ref "X1") (pin "45") (pinfunction "45_45") (pintype "passive"))
    )
    (net (code "290") (name "VOUT_10") (class "Default")
      (node (ref "R12") (pin "2") (pinfunction "2_2") (pintype "passive"))
      (node (ref "X1") (pin "12") (pinfunction "12_12") (pintype "passive"))
    )
    (net (code "291") (name "VOUT_11") (class "Default")
      (node (ref "R14") (pin "2") (pinfunction "2_2") (pintype "passive"))
      (node (ref "X1") (pin "43") (pinfunction "43_43") (pintype "passive"))
    )
    (net (code "292") (name "VOUT_12") (class "Default")
      (node (ref "R16") (pin "2") (pinfunction "2_2") (pintype "passive"))
      (node (ref "X1") (pin "10") (pinfunction "10_10") (pintype "passive"))
    )
    (net (code "293") (name "VREF") (class "Default")
      (node (ref "C23") (pin "1") (pinfunction "1_1") (pintype "passive"))
      (node (ref "C24") (pin "1") (pinfunction "1_1") (pintype "passive"))
      (node (ref "C25") (pin "1") (pinfunction "1_1") (pintype "passive"))
      (node (ref "R6") (pin "1") (pinfunction "1_1") (pintype "passive"))
      (node (ref "R7") (pin "2") (pinfunction "2_2") (pintype "passive"))
      (node (ref "U1") (pin "12") (pinfunction "VREF_12") (pintype "bidirectional"))
      (node (ref "U2") (pin "35") (pinfunction "VREF_35") (pintype "bidirectional"))
      (node (ref "U3") (pin "35") (pinfunction "VREF_35") (pintype "bidirectional"))
      (node (ref "U40") (pin "41") (pinfunction "VREF_41") (pintype "bidirectional"))
    )
    (net (code "294") (name "unconnected-(ISO9-GND1-Pad2)") (class "Default")
      (node (ref "ISO9") (pin "2") (pinfunction "GND1_2") (pintype "bidirectional"))
    )
    (net (code "295") (name "unconnected-(ISO9-GND1-Pad8)") (class "Default")
      (node (ref "ISO9") (pin "8") (pinfunction "GND1_8") (pintype "bidirectional"))
    )
    (net (code "296") (name "unconnected-(ISO9-VDD1-Pad1)") (class "Default")
      (node (ref "ISO9") (pin "1") (pinfunction "VDD1_1") (pintype "bidirectional"))
    )
    (net (code "297") (name "unconnected-(ISO10-A5-Pad7)") (class "Default")
      (node (ref "ISO10") (pin "7") (pinfunction "A5_7") (pintype "bidirectional"))
    )
    (net (code "298") (name "unconnected-(ISO10-B5-Pad10)") (class "Default")
      (node (ref "ISO10") (pin "10") (pinfunction "B5_10") (pintype "bidirectional"))
    )
    (net (code "299") (name "unconnected-(ISO10-GND1-Pad2)") (class "Default")
      (node (ref "ISO10") (pin "2") (pinfunction "GND1_2") (pintype "bidirectional"))
    )
    (net (code "300") (name "unconnected-(ISO10-GND1-Pad8)") (class "Default")
      (node (ref "ISO10") (pin "8") (pinfunction "GND1_8") (pintype "bidirectional"))
    )
    (net (code "301") (name "unconnected-(ISO10-VDD1-Pad1)") (class "Default")
      (node (ref "ISO10") (pin "1") (pinfunction "VDD1_1") (pintype "bidirectional"))
    )
    (net (code "302") (name "unconnected-(J1-PadB30)") (class "Default")
      (node (ref "J1") (pin "B30") (pinfunction "B30_B30") (pintype "passive"))
    )
    (net (code "303") (name "unconnected-(J1-PadB32)") (class "Default")
      (node (ref "J1") (pin "B32") (pinfunction "B32_B32") (pintype "passive"))
    )
    (net (code "304") (name "unconnected-(J1-PadB39)") (class "Default")
      (node (ref "J1") (pin "B39") (pinfunction "B39_B39") (pintype "passive"))
    )
    (net (code "305") (name "unconnected-(J1-PadC30)") (class "Default")
      (node (ref "J1") (pin "C30") (pinfunction "C30_C30") (pintype "passive"))
    )
    (net (code "306") (name "unconnected-(J1-PadD30)") (class "Default")
      (node (ref "J1") (pin "D30") (pinfunction "D30_D30") (pintype "passive"))
    )
    (net (code "307") (name "unconnected-(J1-PadD32)") (class "Default")
      (node (ref "J1") (pin "D32") (pinfunction "D32_D32") (pintype "passive"))
    )
    (net (code "308") (name "unconnected-(J1-PadD39)") (class "Default")
      (node (ref "J1") (pin "D39") (pinfunction "D39_D39") (pintype "passive"))
    )
    (net (code "309") (name "unconnected-(U1-2Y-Pad3)") (class "Default")
      (node (ref "U1") (pin "3") (pinfunction "2Y_3") (pintype "bidirectional"))
    )
    (net (code "310") (name "unconnected-(X1-PadG1)") (class "Default")
      (node (ref "X1") (pin "G1") (pinfunction "G1_G1") (pintype "passive"))
    )
    (net (code "311") (name "unconnected-(X1-PadG2)") (class "Default")
      (node (ref "X1") (pin "G2") (pinfunction "G2_G2") (pintype "passive"))
    )
  )
)
